# PCB_ICBExt-R1_0-J23.net
KiCad netlist of a schematic drawn in EAGLE
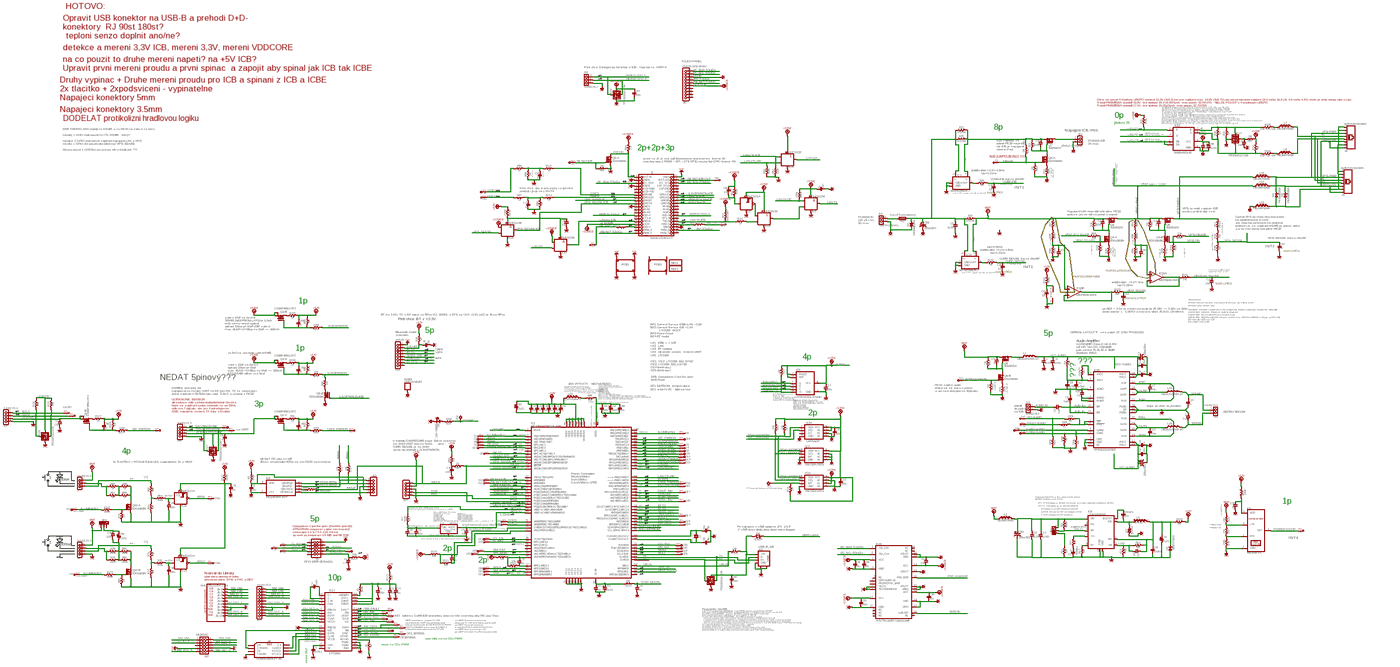
[diagram p0: schematic, sheet 1, overview]
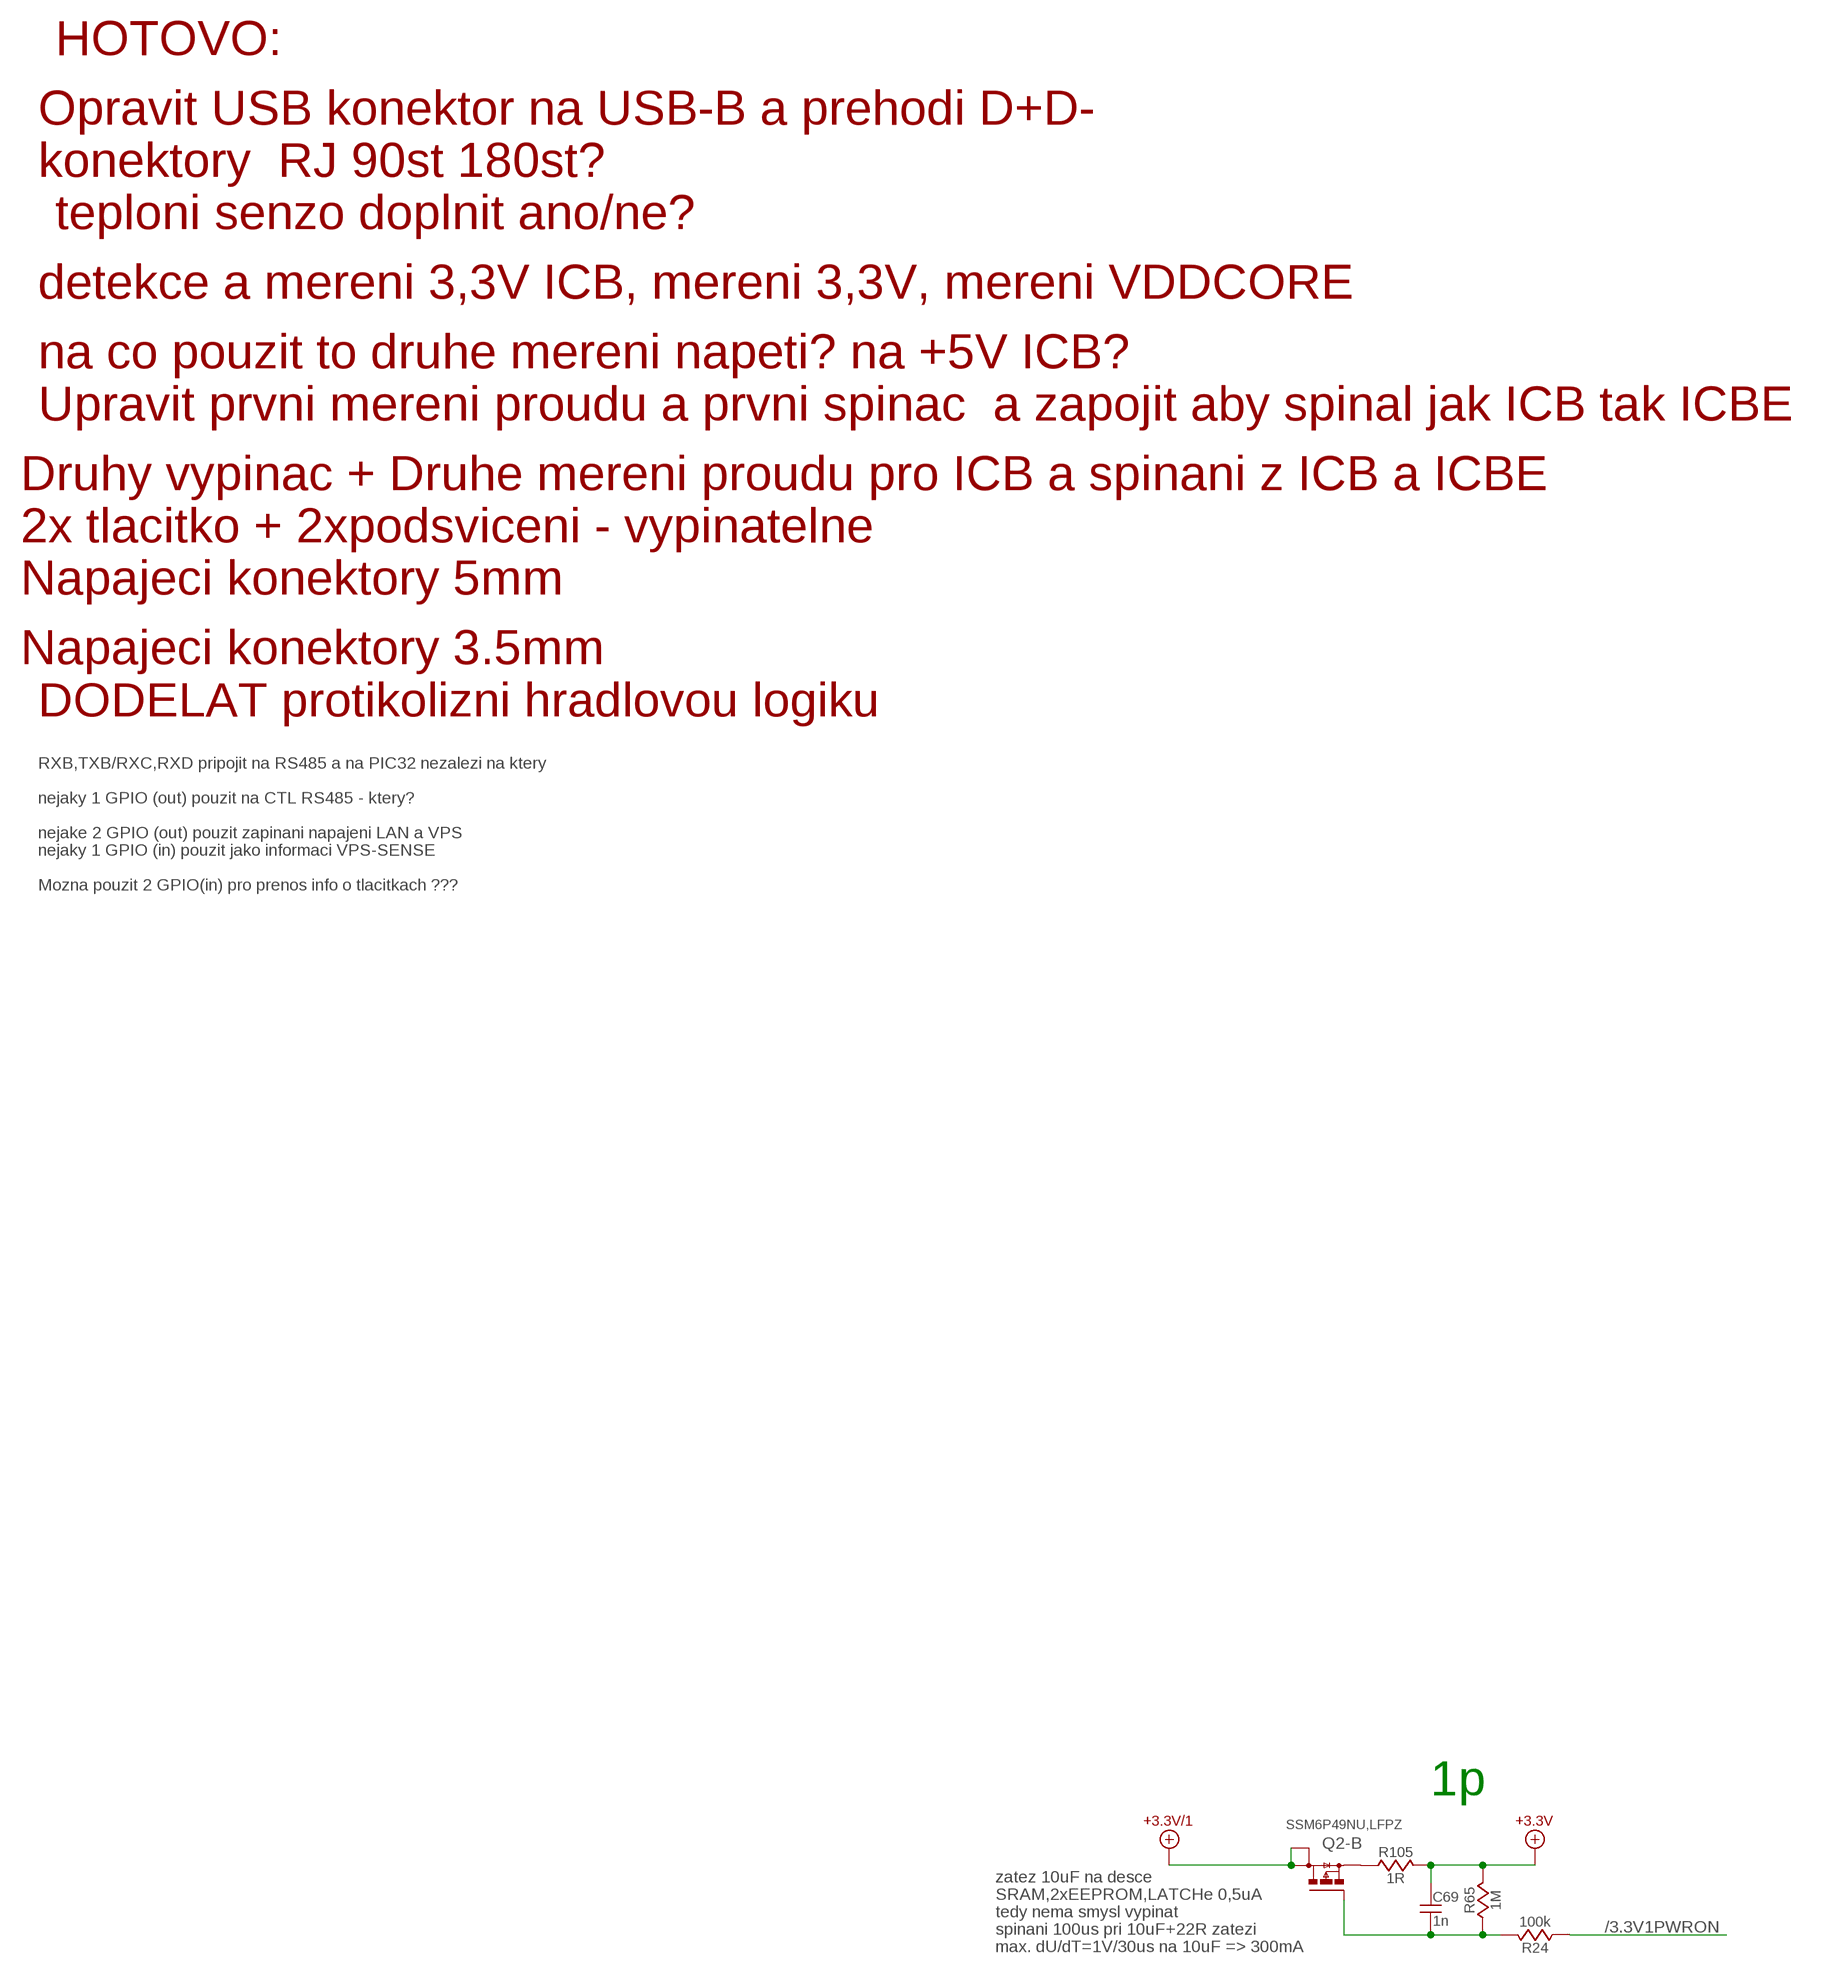
[diagram p1: schematic, sheet 1, part 1 of 6]
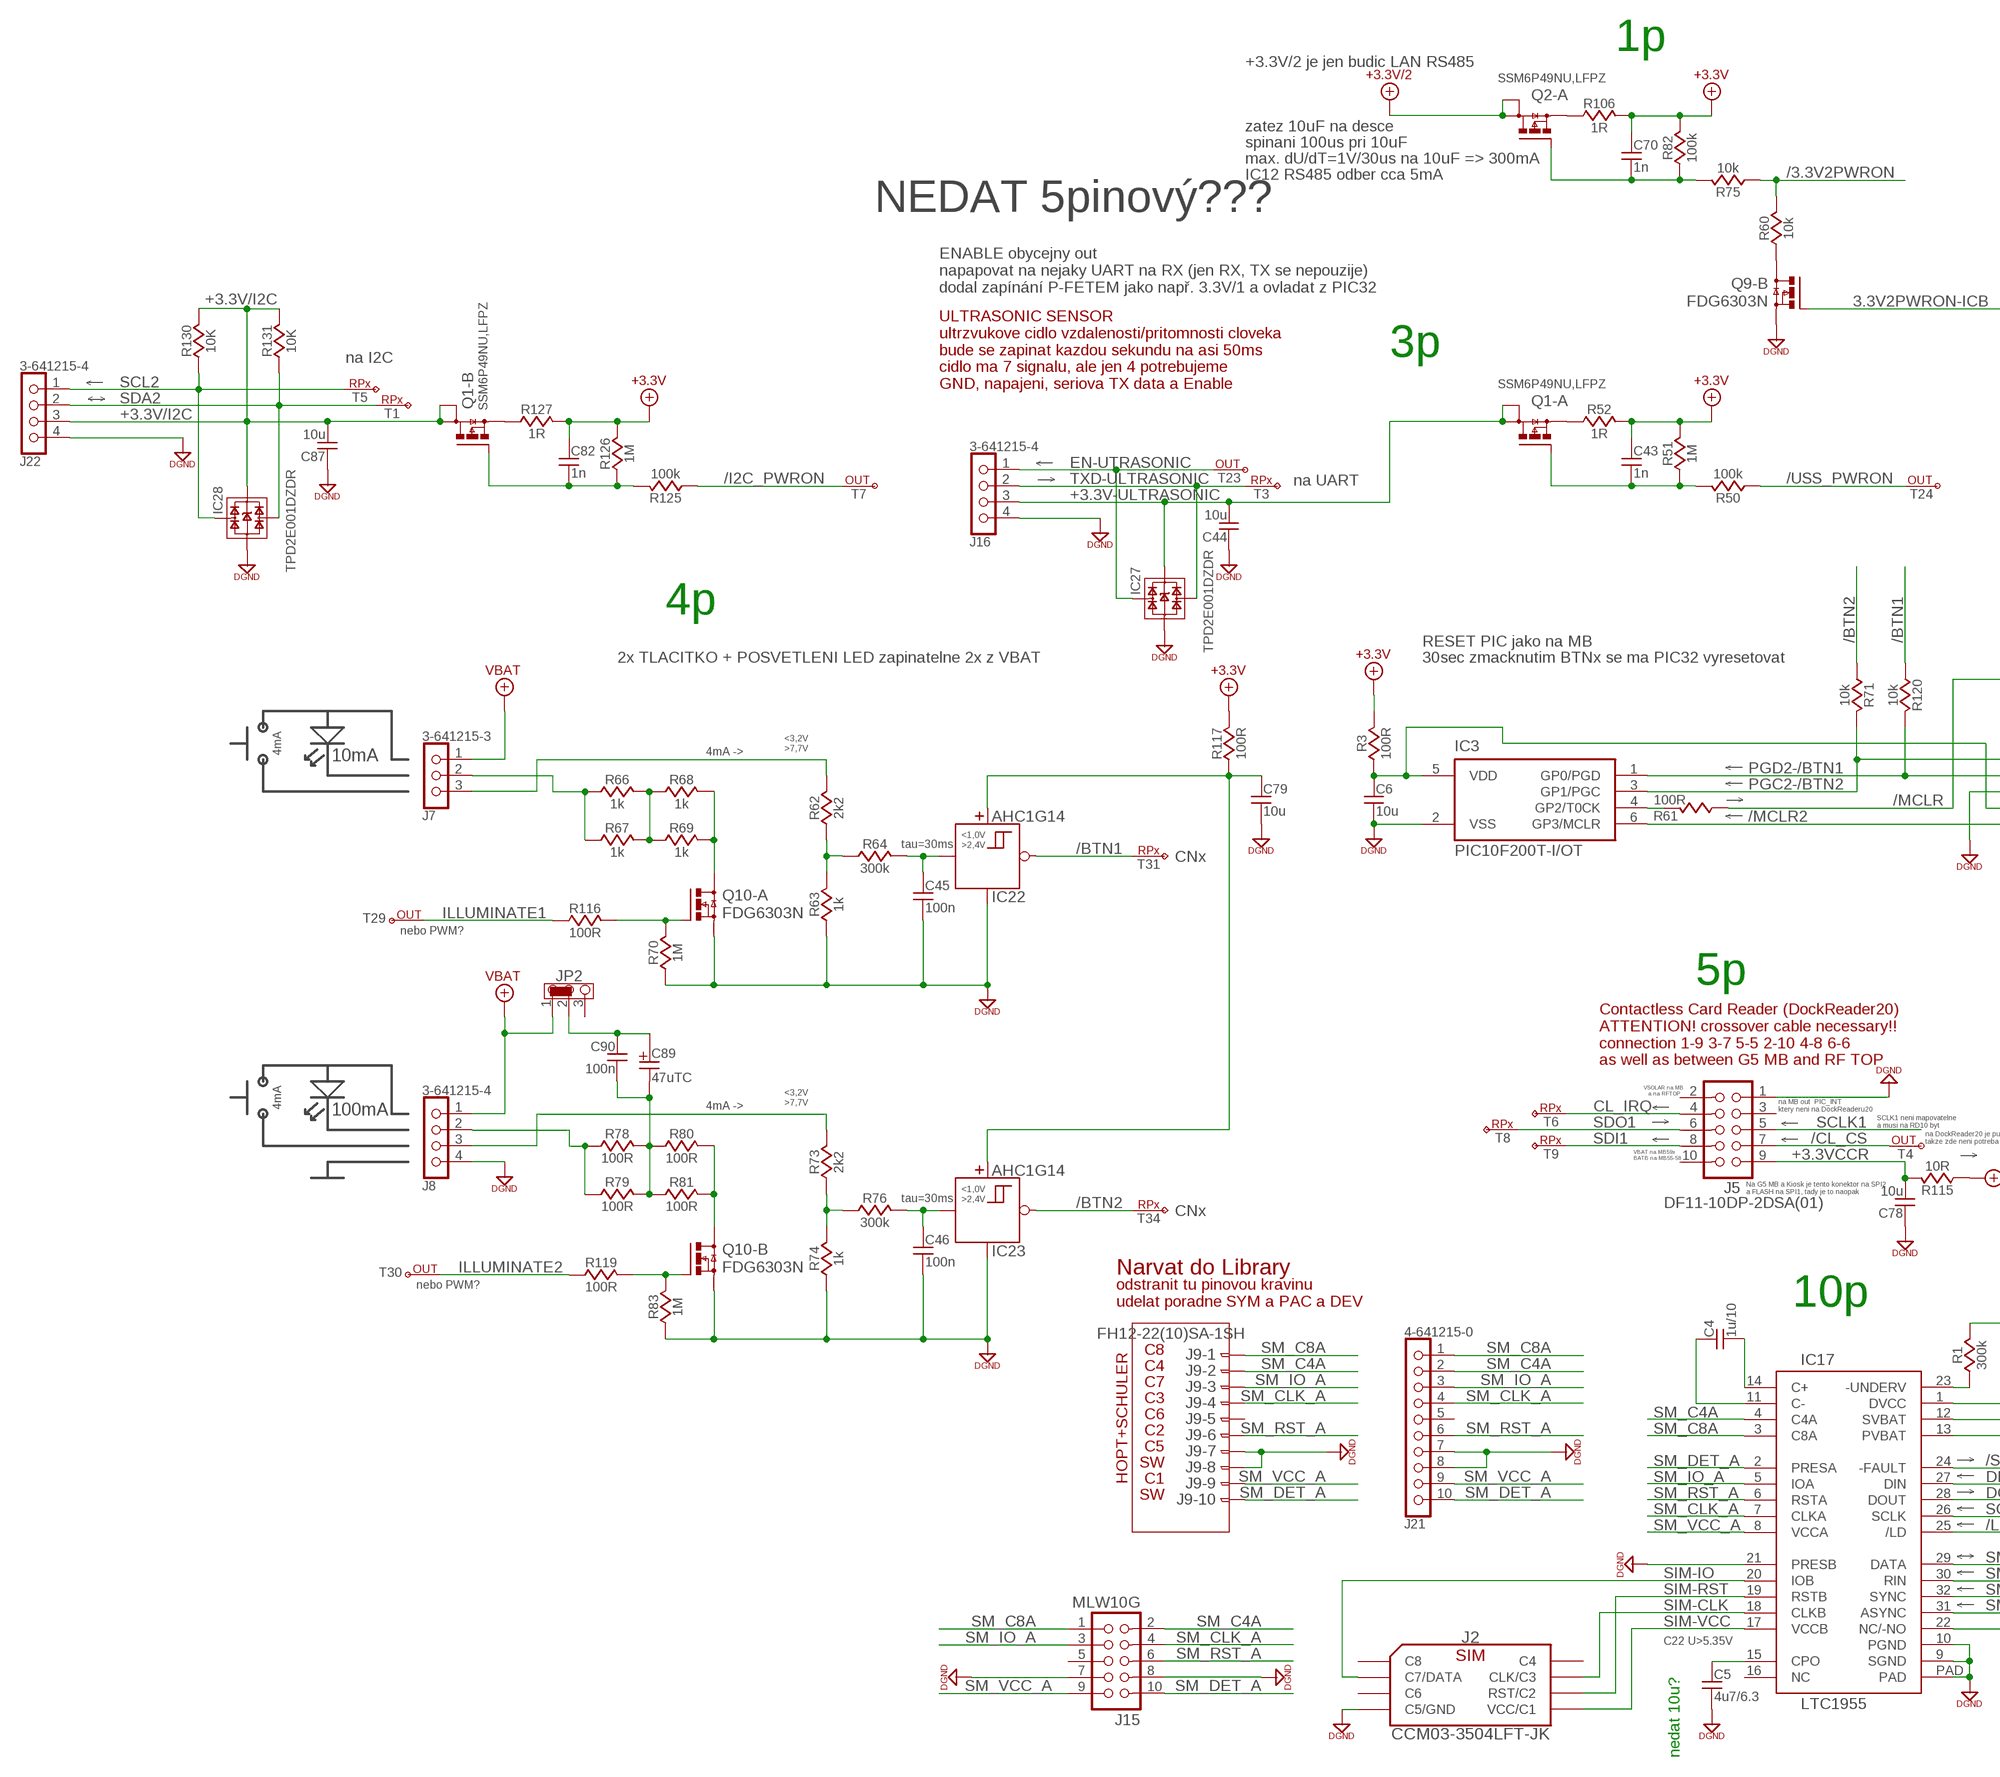
[diagram p2: schematic, sheet 1, part 2 of 6]
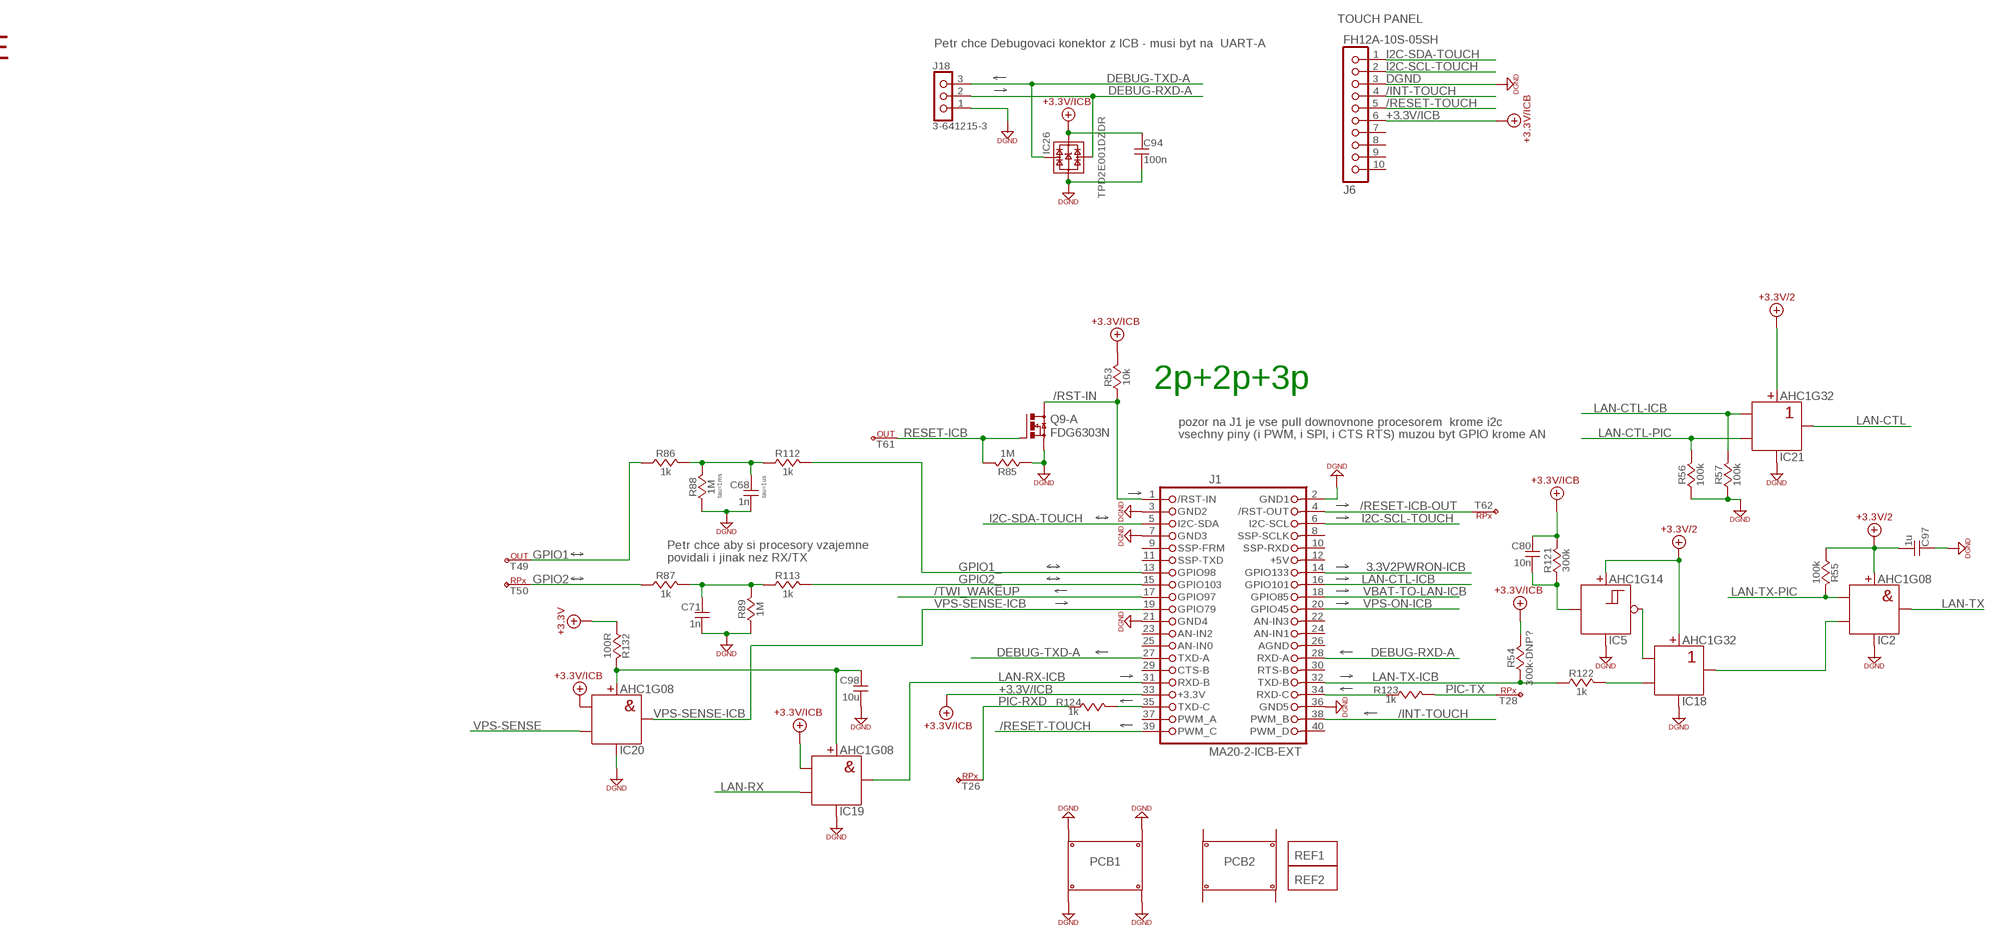
[diagram p3: schematic, sheet 1, part 3 of 6]
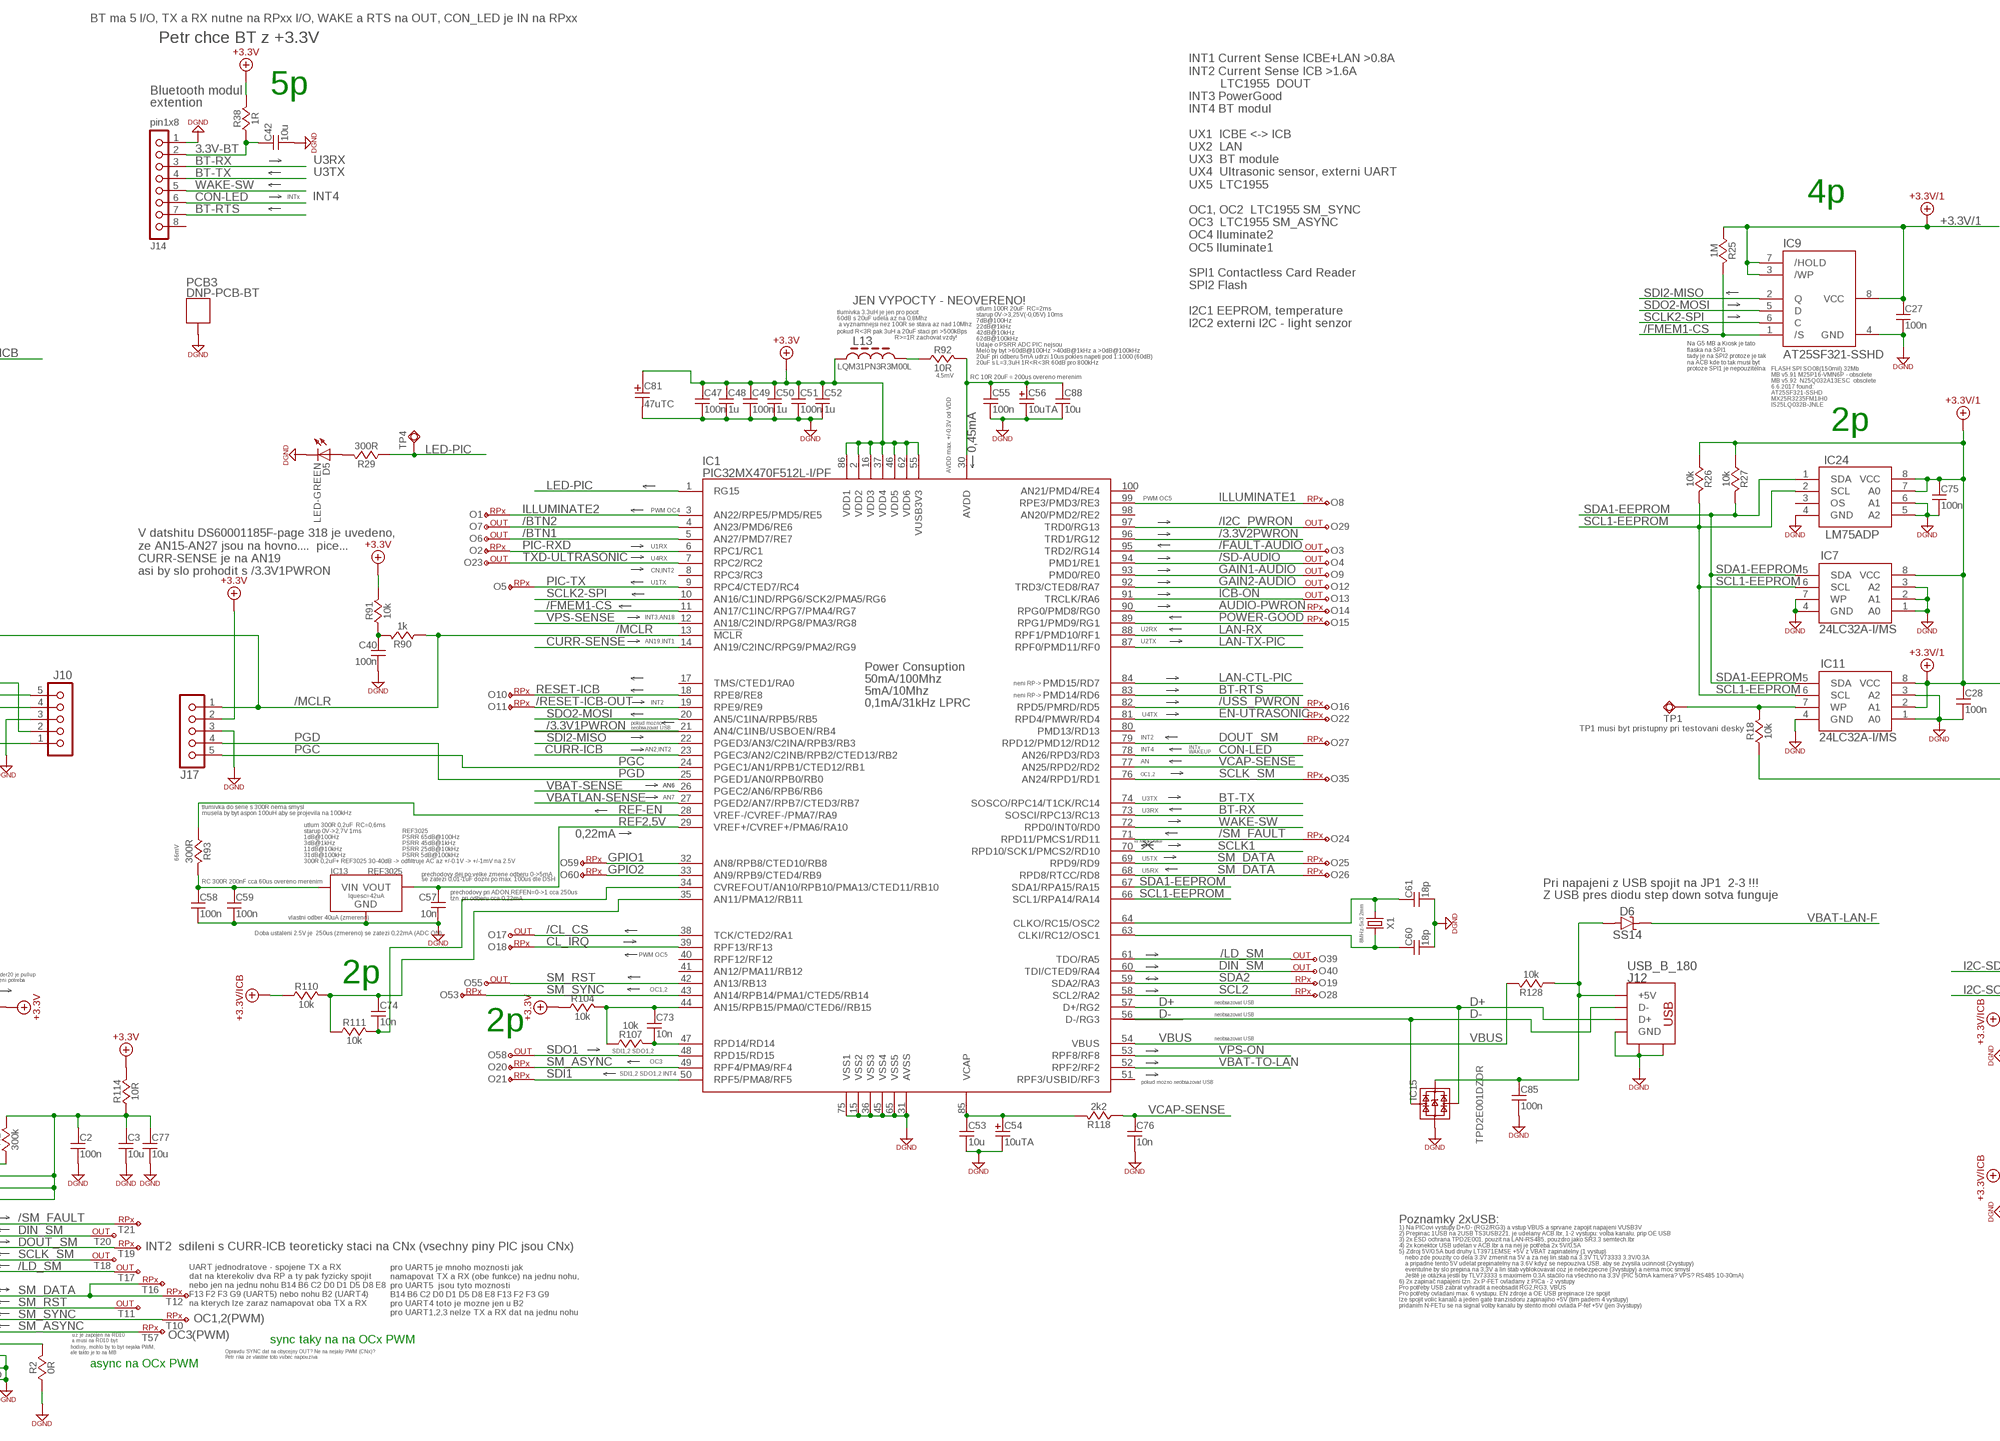
[diagram p4: schematic, sheet 1, part 4 of 6]
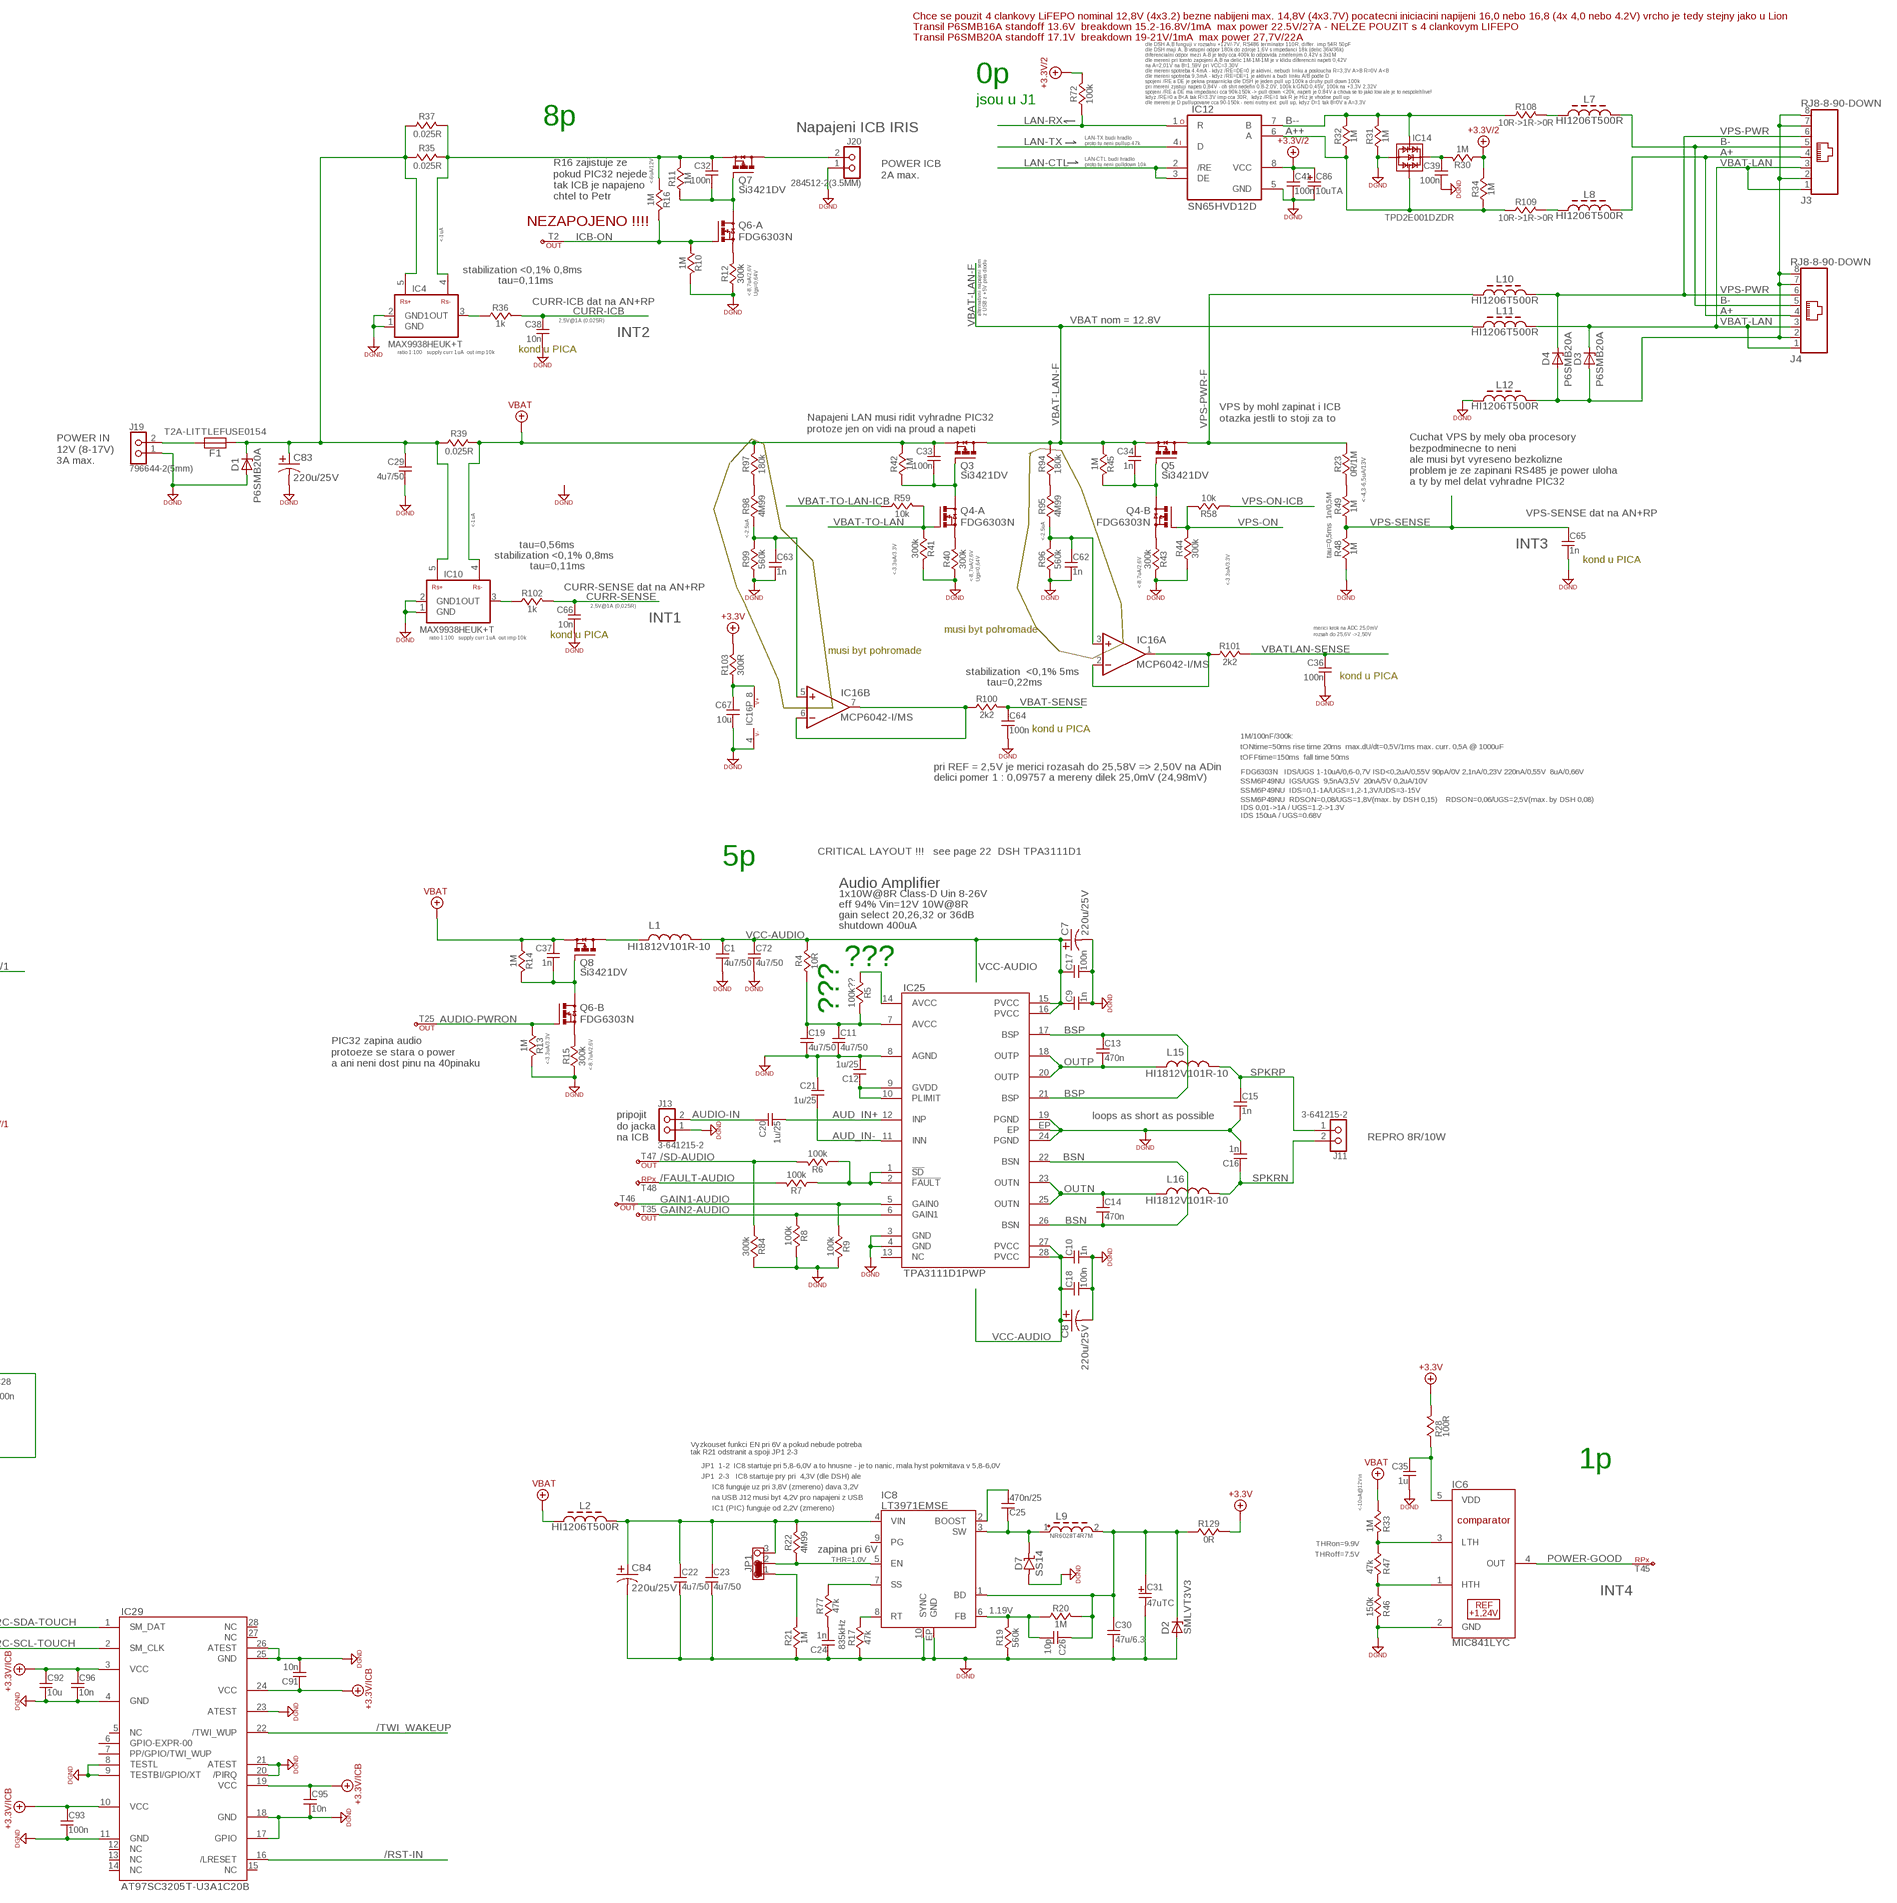
[diagram p5: schematic, sheet 1, part 5 of 6]

(export (version "E")
  (design (tool "Eeschema 10.0.6"))
  (components
    (comp (ref "C1")
      (value "4u7/50")
      (footprint "eagle-import:1206")
      (libsource (lib "eagle-import") (part "C-1206"))
    )
    (comp (ref "C2")
      (value "100n")
      (footprint "eagle-import:0603")
      (libsource (lib "eagle-import") (part "C-0603"))
    )
    (comp (ref "C3")
      (value "10u")
      (footprint "eagle-import:0603")
      (libsource (lib "eagle-import") (part "C-0603"))
    )
    (comp (ref "C4")
      (value "1u/10")
      (footprint "eagle-import:0603")
      (libsource (lib "eagle-import") (part "C-0603"))
    )
    (comp (ref "C5")
      (value "4u7/6.3")
      (footprint "eagle-import:0603")
      (libsource (lib "eagle-import") (part "C-0603"))
    )
    (comp (ref "C6")
      (value "10u")
      (footprint "eagle-import:0603")
      (libsource (lib "eagle-import") (part "C-0603"))
    )
    (comp (ref "C7")
      (value "220u/25V")
      (footprint "eagle-import:CAP_8MM_DIA_SMT")
      (libsource (lib "eagle-import") (part "CAP-ELEC-SMD-8MM"))
    )
    (comp (ref "C8")
      (value "220u/25V")
      (footprint "eagle-import:CAP_8MM_DIA_SMT")
      (libsource (lib "eagle-import") (part "CAP-ELEC-SMD-8MM"))
    )
    (comp (ref "C9")
      (value "1n")
      (footprint "eagle-import:0603")
      (libsource (lib "eagle-import") (part "C-0603"))
    )
    (comp (ref "C10")
      (value "1n")
      (footprint "eagle-import:0603")
      (libsource (lib "eagle-import") (part "C-0603"))
    )
    (comp (ref "C11")
      (value "4u7/50")
      (footprint "eagle-import:1206")
      (libsource (lib "eagle-import") (part "C-1206"))
    )
    (comp (ref "C12")
      (value "1u/25")
      (footprint "eagle-import:0603")
      (libsource (lib "eagle-import") (part "C-0603"))
    )
    (comp (ref "C13")
      (value "470n")
      (footprint "eagle-import:0603")
      (libsource (lib "eagle-import") (part "C-0603"))
    )
    (comp (ref "C14")
      (value "470n")
      (footprint "eagle-import:0603")
      (libsource (lib "eagle-import") (part "C-0603"))
    )
    (comp (ref "C15")
      (value "1n")
      (footprint "eagle-import:0603")
      (libsource (lib "eagle-import") (part "C-0603"))
    )
    (comp (ref "C16")
      (value "1n")
      (footprint "eagle-import:0603")
      (libsource (lib "eagle-import") (part "C-0603"))
    )
    (comp (ref "C17")
      (value "100n")
      (footprint "eagle-import:0603")
      (libsource (lib "eagle-import") (part "C-0603"))
    )
    (comp (ref "C18")
      (value "100n")
      (footprint "eagle-import:0603")
      (libsource (lib "eagle-import") (part "C-0603"))
    )
    (comp (ref "C19")
      (value "4u7/50")
      (footprint "eagle-import:1206")
      (libsource (lib "eagle-import") (part "C-1206"))
    )
    (comp (ref "C20")
      (value "1u/25")
      (footprint "eagle-import:0603")
      (libsource (lib "eagle-import") (part "C-0603"))
    )
    (comp (ref "C21")
      (value "1u/25")
      (footprint "eagle-import:0603")
      (libsource (lib "eagle-import") (part "C-0603"))
    )
    (comp (ref "C22")
      (value "4u7/50")
      (footprint "eagle-import:1206")
      (libsource (lib "eagle-import") (part "C-1206"))
    )
    (comp (ref "C23")
      (value "4u7/50")
      (footprint "eagle-import:1206")
      (libsource (lib "eagle-import") (part "C-1206"))
    )
    (comp (ref "C24")
      (value "1n")
      (footprint "eagle-import:0603")
      (libsource (lib "eagle-import") (part "C-0603"))
    )
    (comp (ref "C25")
      (value "470n/25")
      (footprint "eagle-import:0603")
      (libsource (lib "eagle-import") (part "C-0603"))
    )
    (comp (ref "C26")
      (value "10p")
      (footprint "eagle-import:0603")
      (libsource (lib "eagle-import") (part "C-0603"))
    )
    (comp (ref "C27")
      (value "100n")
      (footprint "eagle-import:0603")
      (libsource (lib "eagle-import") (part "C-0603"))
    )
    (comp (ref "C28")
      (value "100n")
      (footprint "eagle-import:0603")
      (libsource (lib "eagle-import") (part "C-0603"))
    )
    (comp (ref "C29")
      (value "4u7/50")
      (footprint "eagle-import:1206")
      (libsource (lib "eagle-import") (part "C-1206"))
    )
    (comp (ref "C30")
      (value "47u/6.3")
      (footprint "eagle-import:1206")
      (libsource (lib "eagle-import") (part "C-1206"))
    )
    (comp (ref "C31")
      (value "47uTC")
      (footprint "eagle-import:CT-C")
      (libsource (lib "eagle-import") (part "CT-C"))
    )
    (comp (ref "C32")
      (value "100n")
      (footprint "eagle-import:0603")
      (libsource (lib "eagle-import") (part "C-0603"))
    )
    (comp (ref "C33")
      (value "100n")
      (footprint "eagle-import:0603")
      (libsource (lib "eagle-import") (part "C-0603"))
    )
    (comp (ref "C34")
      (value "1n")
      (footprint "eagle-import:0603")
      (libsource (lib "eagle-import") (part "C-0603"))
    )
    (comp (ref "C35")
      (value "1u")
      (footprint "eagle-import:0603")
      (libsource (lib "eagle-import") (part "C-0603"))
    )
    (comp (ref "C36")
      (value "100n")
      (footprint "eagle-import:0603")
      (libsource (lib "eagle-import") (part "C-0603"))
    )
    (comp (ref "C37")
      (value "1n")
      (footprint "eagle-import:0603")
      (libsource (lib "eagle-import") (part "C-0603"))
    )
    (comp (ref "C38")
      (value "10n")
      (footprint "eagle-import:0603")
      (libsource (lib "eagle-import") (part "C-0603"))
    )
    (comp (ref "C39")
      (value "100n")
      (footprint "eagle-import:0603")
      (libsource (lib "eagle-import") (part "C-0603"))
    )
    (comp (ref "C40")
      (value "100n")
      (footprint "eagle-import:0603")
      (libsource (lib "eagle-import") (part "C-0603"))
    )
    (comp (ref "C41")
      (value "100n")
      (footprint "eagle-import:0603")
      (libsource (lib "eagle-import") (part "C-0603"))
    )
    (comp (ref "C42")
      (value "10u")
      (footprint "eagle-import:0603")
      (libsource (lib "eagle-import") (part "C-0603"))
    )
    (comp (ref "C43")
      (value "1n")
      (footprint "eagle-import:0603")
      (libsource (lib "eagle-import") (part "C-0603"))
    )
    (comp (ref "C44")
      (value "10u")
      (footprint "eagle-import:0603")
      (libsource (lib "eagle-import") (part "C-0603"))
    )
    (comp (ref "C45")
      (value "100n")
      (footprint "eagle-import:0603")
      (libsource (lib "eagle-import") (part "C-0603"))
    )
    (comp (ref "C46")
      (value "100n")
      (footprint "eagle-import:0603")
      (libsource (lib "eagle-import") (part "C-0603"))
    )
    (comp (ref "C47")
      (value "100n")
      (footprint "eagle-import:0603")
      (libsource (lib "eagle-import") (part "C-0603"))
    )
    (comp (ref "C48")
      (value "1u")
      (footprint "eagle-import:0603")
      (libsource (lib "eagle-import") (part "C-0603"))
    )
    (comp (ref "C49")
      (value "100n")
      (footprint "eagle-import:0603")
      (libsource (lib "eagle-import") (part "C-0603"))
    )
    (comp (ref "C50")
      (value "1u")
      (footprint "eagle-import:0603")
      (libsource (lib "eagle-import") (part "C-0603"))
    )
    (comp (ref "C51")
      (value "100n")
      (footprint "eagle-import:0603")
      (libsource (lib "eagle-import") (part "C-0603"))
    )
    (comp (ref "C52")
      (value "1u")
      (footprint "eagle-import:0603")
      (libsource (lib "eagle-import") (part "C-0603"))
    )
    (comp (ref "C53")
      (value "10u")
      (footprint "eagle-import:0603")
      (libsource (lib "eagle-import") (part "C-0603"))
    )
    (comp (ref "C54")
      (value "10uTA")
      (footprint "eagle-import:1206-POL-C")
      (libsource (lib "eagle-import") (part "CT-1206"))
    )
    (comp (ref "C55")
      (value "100n")
      (footprint "eagle-import:0603")
      (libsource (lib "eagle-import") (part "C-0603"))
    )
    (comp (ref "C56")
      (value "10uTA")
      (footprint "eagle-import:1206-POL-C")
      (libsource (lib "eagle-import") (part "CT-1206"))
    )
    (comp (ref "C57")
      (value "10n")
      (footprint "eagle-import:0603")
      (libsource (lib "eagle-import") (part "C-0603"))
    )
    (comp (ref "C58")
      (value "100n")
      (footprint "eagle-import:0603")
      (libsource (lib "eagle-import") (part "C-0603"))
    )
    (comp (ref "C59")
      (value "100n")
      (footprint "eagle-import:0603")
      (libsource (lib "eagle-import") (part "C-0603"))
    )
    (comp (ref "C60")
      (value "18p")
      (footprint "eagle-import:0603")
      (libsource (lib "eagle-import") (part "C-0603"))
    )
    (comp (ref "C61")
      (value "18p")
      (footprint "eagle-import:0603")
      (libsource (lib "eagle-import") (part "C-0603"))
    )
    (comp (ref "C62")
      (value "1n")
      (footprint "eagle-import:0603")
      (libsource (lib "eagle-import") (part "C-0603"))
    )
    (comp (ref "C63")
      (value "1n")
      (footprint "eagle-import:0603")
      (libsource (lib "eagle-import") (part "C-0603"))
    )
    (comp (ref "C64")
      (value "100n")
      (footprint "eagle-import:0603")
      (libsource (lib "eagle-import") (part "C-0603"))
    )
    (comp (ref "C65")
      (value "1n")
      (footprint "eagle-import:0603")
      (libsource (lib "eagle-import") (part "C-0603"))
    )
    (comp (ref "C66")
      (value "10n")
      (footprint "eagle-import:0603")
      (libsource (lib "eagle-import") (part "C-0603"))
    )
    (comp (ref "C67")
      (value "10u")
      (footprint "eagle-import:0603")
      (libsource (lib "eagle-import") (part "C-0603"))
    )
    (comp (ref "C68")
      (value "1n")
      (footprint "eagle-import:0603")
      (libsource (lib "eagle-import") (part "C-0603"))
    )
    (comp (ref "C69")
      (value "1n")
      (footprint "eagle-import:0603")
      (libsource (lib "eagle-import") (part "C-0603"))
    )
    (comp (ref "C70")
      (value "1n")
      (footprint "eagle-import:0603")
      (libsource (lib "eagle-import") (part "C-0603"))
    )
    (comp (ref "C71")
      (value "1n")
      (footprint "eagle-import:0603")
      (libsource (lib "eagle-import") (part "C-0603"))
    )
    (comp (ref "C72")
      (value "4u7/50")
      (footprint "eagle-import:1206")
      (libsource (lib "eagle-import") (part "C-1206"))
    )
    (comp (ref "C73")
      (value "10n")
      (footprint "eagle-import:0603")
      (libsource (lib "eagle-import") (part "C-0603"))
    )
    (comp (ref "C74")
      (value "10n")
      (footprint "eagle-import:0603")
      (libsource (lib "eagle-import") (part "C-0603"))
    )
    (comp (ref "C75")
      (value "100n")
      (footprint "eagle-import:0603")
      (libsource (lib "eagle-import") (part "C-0603"))
    )
    (comp (ref "C76")
      (value "10n")
      (footprint "eagle-import:0603")
      (libsource (lib "eagle-import") (part "C-0603"))
    )
    (comp (ref "C77")
      (value "10u")
      (footprint "eagle-import:0603")
      (libsource (lib "eagle-import") (part "C-0603"))
    )
    (comp (ref "C78")
      (value "10u")
      (footprint "eagle-import:0603")
      (libsource (lib "eagle-import") (part "C-0603"))
    )
    (comp (ref "C79")
      (value "10u")
      (footprint "eagle-import:0603")
      (libsource (lib "eagle-import") (part "C-0603"))
    )
    (comp (ref "C80")
      (value "10n")
      (footprint "eagle-import:0603")
      (libsource (lib "eagle-import") (part "C-0603"))
    )
    (comp (ref "C81")
      (value "47uTC")
      (footprint "eagle-import:CT-C")
      (libsource (lib "eagle-import") (part "CT-C"))
    )
    (comp (ref "C82")
      (value "1n")
      (footprint "eagle-import:0603")
      (libsource (lib "eagle-import") (part "C-0603"))
    )
    (comp (ref "C83")
      (value "220u/25V")
      (footprint "eagle-import:CAP_8MM_DIA_SMT")
      (libsource (lib "eagle-import") (part "CAP-ELEC-SMD-8MM"))
    )
    (comp (ref "C84")
      (value "220u/25V")
      (footprint "eagle-import:CAP_8MM_DIA_SMT")
      (libsource (lib "eagle-import") (part "CAP-ELEC-SMD-8MM"))
    )
    (comp (ref "C85")
      (value "100n")
      (footprint "eagle-import:0603")
      (libsource (lib "eagle-import") (part "C-0603"))
    )
    (comp (ref "C86")
      (value "10uTA")
      (footprint "eagle-import:1206-POL-C")
      (libsource (lib "eagle-import") (part "CT-1206"))
    )
    (comp (ref "C87")
      (value "10u")
      (footprint "eagle-import:0603")
      (libsource (lib "eagle-import") (part "C-0603"))
    )
    (comp (ref "C88")
      (value "10u")
      (footprint "eagle-import:0603")
      (libsource (lib "eagle-import") (part "C-0603"))
    )
    (comp (ref "C89")
      (value "47uTC")
      (footprint "eagle-import:CT-C")
      (libsource (lib "eagle-import") (part "CT-C"))
    )
    (comp (ref "C90")
      (value "100n")
      (footprint "eagle-import:0603")
      (libsource (lib "eagle-import") (part "C-0603"))
    )
    (comp (ref "C91")
      (value "10n")
      (footprint "eagle-import:0603")
      (libsource (lib "eagle-import") (part "C-0603"))
    )
    (comp (ref "C92")
      (value "10u")
      (footprint "eagle-import:0603")
      (libsource (lib "eagle-import") (part "C-0603"))
    )
    (comp (ref "C93")
      (value "100n")
      (footprint "eagle-import:0603")
      (libsource (lib "eagle-import") (part "C-0603"))
    )
    (comp (ref "C94")
      (value "100n")
      (footprint "eagle-import:0603")
      (libsource (lib "eagle-import") (part "C-0603"))
    )
    (comp (ref "C95")
      (value "10n")
      (footprint "eagle-import:0603")
      (libsource (lib "eagle-import") (part "C-0603"))
    )
    (comp (ref "C96")
      (value "10n")
      (footprint "eagle-import:0603")
      (libsource (lib "eagle-import") (part "C-0603"))
    )
    (comp (ref "C97")
      (value "1u")
      (footprint "eagle-import:0603")
      (libsource (lib "eagle-import") (part "C-0603"))
    )
    (comp (ref "C98")
      (value "10u")
      (footprint "eagle-import:0603")
      (libsource (lib "eagle-import") (part "C-0603"))
    )
    (comp (ref "D1")
      (value "P6SMB20A")
      (footprint "eagle-import:SMB")
      (libsource (lib "eagle-import") (part "P6SMB"))
    )
    (comp (ref "D2")
      (value "SMLVT3V3")
      (footprint "eagle-import:SMA")
      (libsource (lib "eagle-import") (part "SMLVT3V3"))
    )
    (comp (ref "D3")
      (value "P6SMB20A")
      (footprint "eagle-import:SMB")
      (libsource (lib "eagle-import") (part "P6SMB"))
    )
    (comp (ref "D4")
      (value "P6SMB20A")
      (footprint "eagle-import:SMB")
      (libsource (lib "eagle-import") (part "P6SMB"))
    )
    (comp (ref "D5")
      (value "LED-GREEN")
      (footprint "eagle-import:0805-POL-D")
      (libsource (lib "eagle-import") (part "LED-0805"))
    )
    (comp (ref "D6")
      (value "SS14")
      (footprint "eagle-import:SMA")
      (libsource (lib "eagle-import") (part "DS-SMA"))
    )
    (comp (ref "D7")
      (value "SS14")
      (footprint "eagle-import:SMA")
      (libsource (lib "eagle-import") (part "DS-SMA"))
    )
    (comp (ref "F1")
      (value "T2A-LITTLEFUSE0154")
      (footprint "eagle-import:LITTLEFUSE0154")
      (libsource (lib "eagle-import") (part "POJISTKA-LITTLEFUSE0154"))
    )
    (comp (ref "IC1")
      (value "PIC32MX470F512L-I/PF")
      (footprint "eagle-import:TQFP100_14X14_0,5MM")
      (libsource (lib "eagle-import") (part "PIC32MX470F512L-I/PF"))
    )
    (comp (ref "IC2")
      (value "AHC1G08")
      (footprint "eagle-import:SC70-5,SOT353,TSSOP5")
      (libsource (lib "eagle-import") (part "AHC1G08"))
    )
    (comp (ref "IC3")
      (value "PIC10F200T-I/OT")
      (footprint "eagle-import:SOT23-6")
      (libsource (lib "eagle-import") (part "PIC10F200T-I/OT"))
    )
    (comp (ref "IC4")
      (value "MAX9938HEUK+T")
      (footprint "eagle-import:SOT23-5")
      (libsource (lib "eagle-import") (part "TSM9938HEUK+T"))
    )
    (comp (ref "IC5")
      (value "AHC1G14")
      (footprint "eagle-import:SC70-5,SOT353,TSSOP5")
      (libsource (lib "eagle-import") (part "AHC1G14"))
    )
    (comp (ref "IC6")
      (value "MIC841LYC")
      (footprint "eagle-import:SC-70-5")
      (libsource (lib "eagle-import") (part "MIC841LYC"))
    )
    (comp (ref "IC7")
      (value "24LC32A-I/MS")
      (footprint "eagle-import:MSOP-08")
      (libsource (lib "eagle-import") (part "24-I/MS"))
    )
    (comp (ref "IC8")
      (value "LT3971EMSE")
      (footprint "eagle-import:MSOP10EXP")
      (libsource (lib "eagle-import") (part "LT3971EMSE"))
    )
    (comp (ref "IC9")
      (value "AT25SF321-SSHD")
      (footprint "eagle-import:SO-08")
      (libsource (lib "eagle-import") (part "M25P16-VMN6P"))
    )
    (comp (ref "IC10")
      (value "MAX9938HEUK+T")
      (footprint "eagle-import:SOT23-5")
      (libsource (lib "eagle-import") (part "TSM9938HEUK+T"))
    )
    (comp (ref "IC11")
      (value "24LC32A-I/MS")
      (footprint "eagle-import:MSOP-08")
      (libsource (lib "eagle-import") (part "24-I/MS"))
    )
    (comp (ref "IC12")
      (value "SN65HVD12D")
      (footprint "eagle-import:SO08")
      (libsource (lib "eagle-import") (part "SN65HVD3082ED"))
    )
    (comp (ref "IC13")
      (value "REF3025")
      (footprint "eagle-import:SOT23")
      (libsource (lib "eagle-import") (part "REF3025"))
    )
    (comp (ref "IC14")
      (value "TPD2E001DZDR")
      (footprint "eagle-import:SOT-143")
      (libsource (lib "eagle-import") (part "SR05.TCT"))
    )
    (comp (ref "IC15")
      (value "TPD2E001DZDR")
      (footprint "eagle-import:SOT-143")
      (libsource (lib "eagle-import") (part "SR05.TCT"))
    )
    (comp (ref "IC16")
      (value "MCP6042-I/MS")
      (footprint "eagle-import:MSOP-08")
      (libsource (lib "eagle-import") (part "MCP6042-I/MS"))
    )
    (comp (ref "IC17")
      (value "LTC1955")
      (footprint "eagle-import:QFN32")
      (libsource (lib "eagle-import") (part "LTC1955"))
    )
    (comp (ref "IC18")
      (value "AHC1G32")
      (footprint "eagle-import:SC70-5,SOT353,TSSOP5")
      (libsource (lib "eagle-import") (part "AHC1G32"))
    )
    (comp (ref "IC19")
      (value "AHC1G08")
      (footprint "eagle-import:SC70-5,SOT353,TSSOP5")
      (libsource (lib "eagle-import") (part "AHC1G08"))
    )
    (comp (ref "IC20")
      (value "AHC1G08")
      (footprint "eagle-import:SC70-5,SOT353,TSSOP5")
      (libsource (lib "eagle-import") (part "AHC1G08"))
    )
    (comp (ref "IC21")
      (value "AHC1G32")
      (footprint "eagle-import:SC70-5,SOT353,TSSOP5")
      (libsource (lib "eagle-import") (part "AHC1G32"))
    )
    (comp (ref "IC22")
      (value "AHC1G14")
      (footprint "eagle-import:SC70-5,SOT353,TSSOP5")
      (libsource (lib "eagle-import") (part "AHC1G14"))
    )
    (comp (ref "IC23")
      (value "AHC1G14")
      (footprint "eagle-import:SC70-5,SOT353,TSSOP5")
      (libsource (lib "eagle-import") (part "AHC1G14"))
    )
    (comp (ref "IC24")
      (value "LM75ADP")
      (footprint "eagle-import:TSSOP08-3")
      (libsource (lib "eagle-import") (part "LM75ADP"))
    )
    (comp (ref "IC25")
      (value "TPA3111D1PWP")
      (footprint "eagle-import:TSSOP28_EP")
      (fields (field (name "MANUFACTURER") "TI"))
      (libsource (lib "eagle-import") (part "IC_TI_TPA3111D1PWP"))
    )
    (comp (ref "IC26")
      (value "TPD2E001DZDR")
      (footprint "eagle-import:SOT-143")
      (libsource (lib "eagle-import") (part "SR05.TCT"))
    )
    (comp (ref "IC27")
      (value "TPD2E001DZDR")
      (footprint "eagle-import:SOT-143")
      (libsource (lib "eagle-import") (part "SR05.TCT"))
    )
    (comp (ref "IC28")
      (value "TPD2E001DZDR")
      (footprint "eagle-import:SOT-143")
      (libsource (lib "eagle-import") (part "SR05.TCT"))
    )
    (comp (ref "IC29")
      (value "AT97SC3205T-U3A1C20B")
      (footprint "eagle-import:TSSOP28")
      (fields (field (name "MANUFACTURER") "Microchip"))
      (libsource (lib "eagle-import") (part "AT97SC3205T-U3A1C20B"))
    )
    (comp (ref "J1")
      (value "MA20-2-ICB-EXT")
      (footprint "eagle-import:MA20-2")
      (libsource (lib "eagle-import") (part "MA20-2-ICB-EXT"))
    )
    (comp (ref "J2")
      (value "CCM03-3504LFT-JK")
      (footprint "eagle-import:CCM03-3504LFT-JK")
      (libsource (lib "eagle-import") (part "CCM03-3504LFT-JK"))
    )
    (comp (ref "J3")
      (value "RJ8-8-90-DOWN")
      (footprint "eagle-import:RJ8-8-90-DOWN")
      (libsource (lib "eagle-import") (part "RJ8-8-90-DOWN"))
    )
    (comp (ref "J4")
      (value "RJ8-8-90-DOWN")
      (footprint "eagle-import:RJ8-8-90-DOWN")
      (libsource (lib "eagle-import") (part "RJ8-8-90-DOWN"))
    )
    (comp (ref "J5")
      (value "DF11-10DP-2DSA(01)")
      (footprint "eagle-import:DF11-10DP-2DSA")
      (libsource (lib "eagle-import") (part "DF11-10DP-2DSA(01)"))
    )
    (comp (ref "J6")
      (value "FH12A-10S-05SH")
      (footprint "eagle-import:FH12A-10S-05SH")
      (libsource (lib "eagle-import") (part "FH12A-10S-05SH"))
    )
    (comp (ref "J7")
      (value "3-641215-3")
      (footprint "eagle-import:3-641215-3")
      (libsource (lib "eagle-import") (part "3-641215-3"))
    )
    (comp (ref "J8")
      (value "3-641215-4")
      (footprint "eagle-import:3-641215-4")
      (libsource (lib "eagle-import") (part "3-641215-4"))
    )
    (comp (ref "J9")
      (value "FH12-22(10)SA-1SH")
      (footprint "eagle-import:CON-FPC-1.0MM-10POS")
      (libsource (lib "eagle-import") (part "FH12-10S-0.5S1.00MM"))
    )
    (comp (ref "J10")
      (value "DNP-open-hole")
      (footprint "eagle-import:MA05-1")
      (libsource (lib "eagle-import") (part "MA05-1"))
    )
    (comp (ref "J11")
      (value "3-641215-2")
      (footprint "eagle-import:3-641215-2")
      (libsource (lib "eagle-import") (part "3-641215-2"))
    )
    (comp (ref "J12")
      (value "USB_B_180")
      (footprint "eagle-import:USB_B_90")
      (libsource (lib "eagle-import") (part "USB_B_90"))
    )
    (comp (ref "J13")
      (value "3-641215-2")
      (footprint "eagle-import:3-641215-2")
      (libsource (lib "eagle-import") (part "3-641215-2"))
    )
    (comp (ref "J14")
      (value "pin1x8")
      (footprint "eagle-import:MA08-1-MALE")
      (libsource (lib "eagle-import") (part "MA08-1-M"))
    )
    (comp (ref "J15")
      (value "MLW10G")
      (footprint "eagle-import:MLW10G-5X2")
      (libsource (lib "eagle-import") (part "MLW10G"))
    )
    (comp (ref "J16")
      (value "3-641215-4")
      (footprint "eagle-import:3-641215-4")
      (libsource (lib "eagle-import") (part "3-641215-4"))
    )
    (comp (ref "J17")
      (value "DNP-open-hole")
      (footprint "eagle-import:MA05-1")
      (libsource (lib "eagle-import") (part "MA05-1"))
    )
    (comp (ref "J18")
      (value "3-641215-3")
      (footprint "eagle-import:3-641215-3")
      (libsource (lib "eagle-import") (part "3-641215-3"))
    )
    (comp (ref "J19")
      (value "796644-2(5mm)")
      (footprint "eagle-import:796644-2-5MM")
      (libsource (lib "eagle-import") (part "796644-2"))
    )
    (comp (ref "J20")
      (value "284512-2(3.5MM)")
      (footprint "eagle-import:284512-2-3,5MM")
      (libsource (lib "eagle-import") (part "284512-2"))
    )
    (comp (ref "J21")
      (value "4-641215-0")
      (footprint "eagle-import:4-641215-0")
      (libsource (lib "eagle-import") (part "4-641215-0"))
    )
    (comp (ref "J22")
      (value "3-641215-4")
      (footprint "eagle-import:3-641215-4")
      (libsource (lib "eagle-import") (part "3-641215-4"))
    )
    (comp (ref "JP1")
      (value "JP3CLOSE12")
      (footprint "eagle-import:JP3CLOSE12")
      (libsource (lib "eagle-import") (part "JP3CLOSE12"))
    )
    (comp (ref "JP2")
      (value "JP3CLOSE12")
      (footprint "eagle-import:JP3CLOSE12")
      (libsource (lib "eagle-import") (part "JP3CLOSE12"))
    )
    (comp (ref "L1")
      (value "HI1812V101R-10")
      (footprint "eagle-import:L1812")
      (fields (field (name "MANUFACTURER") "Laird") (field (name "MFR_PN") "HI1812V101R-10"))
      (libsource (lib "eagle-import") (part "L1812"))
    )
    (comp (ref "L2")
      (value "HI1206T500R")
      (footprint "eagle-import:1206")
      (libsource (lib "eagle-import") (part "L-1206"))
    )
    (comp (ref "L7")
      (value "HI1206T500R")
      (footprint "eagle-import:1206")
      (libsource (lib "eagle-import") (part "L-1206"))
    )
    (comp (ref "L8")
      (value "HI1206T500R")
      (footprint "eagle-import:1206")
      (libsource (lib "eagle-import") (part "L-1206"))
    )
    (comp (ref "L9")
      (value "NR6028T4R7M")
      (footprint "eagle-import:NR6028")
      (libsource (lib "eagle-import") (part "NR6028"))
    )
    (comp (ref "L10")
      (value "HI1206T500R")
      (footprint "eagle-import:1206")
      (libsource (lib "eagle-import") (part "L-1206"))
    )
    (comp (ref "L11")
      (value "HI1206T500R")
      (footprint "eagle-import:1206")
      (libsource (lib "eagle-import") (part "L-1206"))
    )
    (comp (ref "L12")
      (value "HI1206T500R")
      (footprint "eagle-import:1206")
      (libsource (lib "eagle-import") (part "L-1206"))
    )
    (comp (ref "L13")
      (value "LQM31PN3R3M00L")
      (footprint "eagle-import:1206")
      (libsource (lib "eagle-import") (part "L-1206"))
    )
    (comp (ref "L15")
      (value "HI1812V101R-10")
      (footprint "eagle-import:L1812")
      (fields (field (name "MANUFACTURER") "Laird") (field (name "MFR_PN") "HI1812V101R-10"))
      (libsource (lib "eagle-import") (part "L1812"))
    )
    (comp (ref "L16")
      (value "HI1812V101R-10")
      (footprint "eagle-import:L1812")
      (fields (field (name "MANUFACTURER") "Laird") (field (name "MFR_PN") "HI1812V101R-10"))
      (libsource (lib "eagle-import") (part "L1812"))
    )
    (comp (ref "O1")
      (value "PIC-RPX")
      (footprint "eagle-import:TEMP-PAD")
      (libsource (lib "eagle-import") (part "PIC-RPX"))
    )
    (comp (ref "O2")
      (value "PIC-RPX")
      (footprint "eagle-import:TEMP-PAD")
      (libsource (lib "eagle-import") (part "PIC-RPX"))
    )
    (comp (ref "O3")
      (value "PIC-OUT")
      (footprint "eagle-import:TEMP-PAD")
      (libsource (lib "eagle-import") (part "PIC-OUT"))
    )
    (comp (ref "O4")
      (value "PIC-OUT")
      (footprint "eagle-import:TEMP-PAD")
      (libsource (lib "eagle-import") (part "PIC-OUT"))
    )
    (comp (ref "O5")
      (value "PIC-RPX")
      (footprint "eagle-import:TEMP-PAD")
      (libsource (lib "eagle-import") (part "PIC-RPX"))
    )
    (comp (ref "O6")
      (value "PIC-OUT")
      (footprint "eagle-import:TEMP-PAD")
      (libsource (lib "eagle-import") (part "PIC-OUT"))
    )
    (comp (ref "O7")
      (value "PIC-OUT")
      (footprint "eagle-import:TEMP-PAD")
      (libsource (lib "eagle-import") (part "PIC-OUT"))
    )
    (comp (ref "O8")
      (value "PIC-RPX")
      (footprint "eagle-import:TEMP-PAD")
      (libsource (lib "eagle-import") (part "PIC-RPX"))
    )
    (comp (ref "O9")
      (value "PIC-OUT")
      (footprint "eagle-import:TEMP-PAD")
      (libsource (lib "eagle-import") (part "PIC-OUT"))
    )
    (comp (ref "O10")
      (value "PIC-RPX")
      (footprint "eagle-import:TEMP-PAD")
      (libsource (lib "eagle-import") (part "PIC-RPX"))
    )
    (comp (ref "O11")
      (value "PIC-RPX")
      (footprint "eagle-import:TEMP-PAD")
      (libsource (lib "eagle-import") (part "PIC-RPX"))
    )
    (comp (ref "O12")
      (value "PIC-OUT")
      (footprint "eagle-import:TEMP-PAD")
      (libsource (lib "eagle-import") (part "PIC-OUT"))
    )
    (comp (ref "O13")
      (value "PIC-OUT")
      (footprint "eagle-import:TEMP-PAD")
      (libsource (lib "eagle-import") (part "PIC-OUT"))
    )
    (comp (ref "O14")
      (value "PIC-RPX")
      (footprint "eagle-import:TEMP-PAD")
      (libsource (lib "eagle-import") (part "PIC-RPX"))
    )
    (comp (ref "O15")
      (value "PIC-RPX")
      (footprint "eagle-import:TEMP-PAD")
      (libsource (lib "eagle-import") (part "PIC-RPX"))
    )
    (comp (ref "O16")
      (value "PIC-RPX")
      (footprint "eagle-import:TEMP-PAD")
      (libsource (lib "eagle-import") (part "PIC-RPX"))
    )
    (comp (ref "O17")
      (value "PIC-OUT")
      (footprint "eagle-import:TEMP-PAD")
      (libsource (lib "eagle-import") (part "PIC-OUT"))
    )
    (comp (ref "O18")
      (value "PIC-RPX")
      (footprint "eagle-import:TEMP-PAD")
      (libsource (lib "eagle-import") (part "PIC-RPX"))
    )
    (comp (ref "O19")
      (value "PIC-RPX")
      (footprint "eagle-import:TEMP-PAD")
      (libsource (lib "eagle-import") (part "PIC-RPX"))
    )
    (comp (ref "O20")
      (value "PIC-RPX")
      (footprint "eagle-import:TEMP-PAD")
      (libsource (lib "eagle-import") (part "PIC-RPX"))
    )
    (comp (ref "O21")
      (value "PIC-RPX")
      (footprint "eagle-import:TEMP-PAD")
      (libsource (lib "eagle-import") (part "PIC-RPX"))
    )
    (comp (ref "O22")
      (value "PIC-RPX")
      (footprint "eagle-import:TEMP-PAD")
      (libsource (lib "eagle-import") (part "PIC-RPX"))
    )
    (comp (ref "O23")
      (value "PIC-OUT")
      (footprint "eagle-import:TEMP-PAD")
      (libsource (lib "eagle-import") (part "PIC-OUT"))
    )
    (comp (ref "O24")
      (value "PIC-RPX")
      (footprint "eagle-import:TEMP-PAD")
      (libsource (lib "eagle-import") (part "PIC-RPX"))
    )
    (comp (ref "O25")
      (value "PIC-RPX")
      (footprint "eagle-import:TEMP-PAD")
      (libsource (lib "eagle-import") (part "PIC-RPX"))
    )
    (comp (ref "O26")
      (value "PIC-RPX")
      (footprint "eagle-import:TEMP-PAD")
      (libsource (lib "eagle-import") (part "PIC-RPX"))
    )
    (comp (ref "O27")
      (value "PIC-RPX")
      (footprint "eagle-import:TEMP-PAD")
      (libsource (lib "eagle-import") (part "PIC-RPX"))
    )
    (comp (ref "O28")
      (value "PIC-RPX")
      (footprint "eagle-import:TEMP-PAD")
      (libsource (lib "eagle-import") (part "PIC-RPX"))
    )
    (comp (ref "O29")
      (value "PIC-OUT")
      (footprint "eagle-import:TEMP-PAD")
      (libsource (lib "eagle-import") (part "PIC-OUT"))
    )
    (comp (ref "O35")
      (value "PIC-RPX")
      (footprint "eagle-import:TEMP-PAD")
      (libsource (lib "eagle-import") (part "PIC-RPX"))
    )
    (comp (ref "O39")
      (value "PIC-OUT")
      (footprint "eagle-import:TEMP-PAD")
      (libsource (lib "eagle-import") (part "PIC-OUT"))
    )
    (comp (ref "O40")
      (value "PIC-OUT")
      (footprint "eagle-import:TEMP-PAD")
      (libsource (lib "eagle-import") (part "PIC-OUT"))
    )
    (comp (ref "O53")
      (value "PIC-RPX")
      (footprint "eagle-import:TEMP-PAD")
      (libsource (lib "eagle-import") (part "PIC-RPX"))
    )
    (comp (ref "O55")
      (value "PIC-OUT")
      (footprint "eagle-import:TEMP-PAD")
      (libsource (lib "eagle-import") (part "PIC-OUT"))
    )
    (comp (ref "O58")
      (value "PIC-OUT")
      (footprint "eagle-import:TEMP-PAD")
      (libsource (lib "eagle-import") (part "PIC-OUT"))
    )
    (comp (ref "O59")
      (value "PIC-RPX")
      (footprint "eagle-import:TEMP-PAD")
      (libsource (lib "eagle-import") (part "PIC-RPX"))
    )
    (comp (ref "O60")
      (value "PIC-RPX")
      (footprint "eagle-import:TEMP-PAD")
      (libsource (lib "eagle-import") (part "PIC-RPX"))
    )
    (comp (ref "PCB1")
      (value "PCB-ICBE")
      (footprint "eagle-import:PCB-ICBE")
      (libsource (lib "eagle-import") (part "PCB-ICBE"))
    )
    (comp (ref "PCB2")
      (value "NDP-PCB-ICB")
      (footprint "eagle-import:PCB-ICB")
      (libsource (lib "eagle-import") (part "PCB-ICB"))
    )
    (comp (ref "PCB3")
      (value "DNP-PCB-BT")
      (footprint "eagle-import:BT_MODULE_BRD")
      (libsource (lib "eagle-import") (part "BT_PCBBRD"))
    )
    (comp (ref "Q1")
      (value "SSM6P49NU,LFPZ")
      (footprint "eagle-import:MICRO_FET")
      (libsource (lib "eagle-import") (part "SSM6P49PZNU,LF"))
    )
    (comp (ref "Q2")
      (value "SSM6P49NU,LFPZ")
      (footprint "eagle-import:MICRO_FET")
      (libsource (lib "eagle-import") (part "SSM6P49PZNU,LF"))
    )
    (comp (ref "Q3")
      (value "Si3421DV")
      (footprint "eagle-import:SSOT-6")
      (libsource (lib "eagle-import") (part "FDC658AP"))
    )
    (comp (ref "Q4")
      (value "FDG6303N")
      (footprint "eagle-import:SC70-6")
      (libsource (lib "eagle-import") (part "FDG6303N"))
    )
    (comp (ref "Q5")
      (value "Si3421DV")
      (footprint "eagle-import:SSOT-6")
      (libsource (lib "eagle-import") (part "FDC658AP"))
    )
    (comp (ref "Q6")
      (value "FDG6303N")
      (footprint "eagle-import:SC70-6")
      (libsource (lib "eagle-import") (part "FDG6303N"))
    )
    (comp (ref "Q7")
      (value "Si3421DV")
      (footprint "eagle-import:SSOT-6")
      (libsource (lib "eagle-import") (part "FDC658AP"))
    )
    (comp (ref "Q8")
      (value "Si3421DV")
      (footprint "eagle-import:SSOT-6")
      (libsource (lib "eagle-import") (part "FDC658AP"))
    )
    (comp (ref "Q9")
      (value "FDG6303N")
      (footprint "eagle-import:SC70-6")
      (libsource (lib "eagle-import") (part "FDG6303N"))
    )
    (comp (ref "Q10")
      (value "FDG6303N")
      (footprint "eagle-import:SC70-6")
      (libsource (lib "eagle-import") (part "FDG6303N"))
    )
    (comp (ref "R1")
      (value "300k")
      (footprint "eagle-import:0603")
      (libsource (lib "eagle-import") (part "R-0603"))
    )
    (comp (ref "R2")
      (value "0R")
      (footprint "eagle-import:0603")
      (libsource (lib "eagle-import") (part "R-0603"))
    )
    (comp (ref "R3")
      (value "100R")
      (footprint "eagle-import:0603")
      (libsource (lib "eagle-import") (part "R-0603"))
    )
    (comp (ref "R4")
      (value "10R")
      (footprint "eagle-import:0603")
      (libsource (lib "eagle-import") (part "R-0603"))
    )
    (comp (ref "R5")
      (value "100k??")
      (footprint "eagle-import:0603")
      (libsource (lib "eagle-import") (part "R-0603"))
    )
    (comp (ref "R6")
      (value "100k")
      (footprint "eagle-import:0603")
      (libsource (lib "eagle-import") (part "R-0603"))
    )
    (comp (ref "R7")
      (value "100k")
      (footprint "eagle-import:0603")
      (libsource (lib "eagle-import") (part "R-0603"))
    )
    (comp (ref "R8")
      (value "100k")
      (footprint "eagle-import:0603")
      (libsource (lib "eagle-import") (part "R-0603"))
    )
    (comp (ref "R9")
      (value "100k")
      (footprint "eagle-import:0603")
      (libsource (lib "eagle-import") (part "R-0603"))
    )
    (comp (ref "R10")
      (value "1M")
      (footprint "eagle-import:0603")
      (libsource (lib "eagle-import") (part "R-0603"))
    )
    (comp (ref "R11")
      (value "1M")
      (footprint "eagle-import:0603")
      (libsource (lib "eagle-import") (part "R-0603"))
    )
    (comp (ref "R12")
      (value "300k")
      (footprint "eagle-import:0603")
      (libsource (lib "eagle-import") (part "R-0603"))
    )
    (comp (ref "R13")
      (value "1M")
      (footprint "eagle-import:0603")
      (libsource (lib "eagle-import") (part "R-0603"))
    )
    (comp (ref "R14")
      (value "1M")
      (footprint "eagle-import:0603")
      (libsource (lib "eagle-import") (part "R-0603"))
    )
    (comp (ref "R15")
      (value "300k")
      (footprint "eagle-import:0603")
      (libsource (lib "eagle-import") (part "R-0603"))
    )
    (comp (ref "R16")
      (value "1M")
      (footprint "eagle-import:0603")
      (libsource (lib "eagle-import") (part "R-0603"))
    )
    (comp (ref "R17")
      (value "47k")
      (footprint "eagle-import:0603")
      (libsource (lib "eagle-import") (part "R-0603"))
    )
    (comp (ref "R18")
      (value "10k")
      (footprint "eagle-import:0603")
      (libsource (lib "eagle-import") (part "R-0603"))
    )
    (comp (ref "R19")
      (value "560k")
      (footprint "eagle-import:0603")
      (libsource (lib "eagle-import") (part "R-0603"))
    )
    (comp (ref "R20")
      (value "1M")
      (footprint "eagle-import:0603")
      (libsource (lib "eagle-import") (part "R-0603"))
    )
    (comp (ref "R21")
      (value "1M")
      (footprint "eagle-import:0603")
      (libsource (lib "eagle-import") (part "R-0603"))
    )
    (comp (ref "R22")
      (value "4M99")
      (footprint "eagle-import:0603")
      (libsource (lib "eagle-import") (part "R-0603"))
    )
    (comp (ref "R23")
      (value "0R/1M")
      (footprint "eagle-import:0603")
      (libsource (lib "eagle-import") (part "R-0603"))
    )
    (comp (ref "R24")
      (value "100k")
      (footprint "eagle-import:0603")
      (libsource (lib "eagle-import") (part "R-0603"))
    )
    (comp (ref "R25")
      (value "1M")
      (footprint "eagle-import:0603")
      (libsource (lib "eagle-import") (part "R-0603"))
    )
    (comp (ref "R26")
      (value "10k")
      (footprint "eagle-import:0603")
      (libsource (lib "eagle-import") (part "R-0603"))
    )
    (comp (ref "R27")
      (value "10k")
      (footprint "eagle-import:0603")
      (libsource (lib "eagle-import") (part "R-0603"))
    )
    (comp (ref "R28")
      (value "100R")
      (footprint "eagle-import:0603")
      (libsource (lib "eagle-import") (part "R-0603"))
    )
    (comp (ref "R29")
      (value "300R")
      (footprint "eagle-import:0603")
      (libsource (lib "eagle-import") (part "R-0603"))
    )
    (comp (ref "R30")
      (value "1M")
      (footprint "eagle-import:0603")
      (libsource (lib "eagle-import") (part "R-0603"))
    )
    (comp (ref "R31")
      (value "1M")
      (footprint "eagle-import:0603")
      (libsource (lib "eagle-import") (part "R-0603"))
    )
    (comp (ref "R32")
      (value "1M")
      (footprint "eagle-import:0603")
      (libsource (lib "eagle-import") (part "R-0603"))
    )
    (comp (ref "R33")
      (value "1M")
      (footprint "eagle-import:0603")
      (libsource (lib "eagle-import") (part "R-0603"))
    )
    (comp (ref "R34")
      (value "1M")
      (footprint "eagle-import:0603")
      (libsource (lib "eagle-import") (part "R-0603"))
    )
    (comp (ref "R35")
      (value "0.025R")
      (footprint "eagle-import:0805")
      (libsource (lib "eagle-import") (part "R-0805"))
    )
    (comp (ref "R36")
      (value "1k")
      (footprint "eagle-import:0603")
      (libsource (lib "eagle-import") (part "R-0603"))
    )
    (comp (ref "R37")
      (value "0.025R")
      (footprint "eagle-import:0805")
      (libsource (lib "eagle-import") (part "R-0805"))
    )
    (comp (ref "R38")
      (value "1R")
      (footprint "eagle-import:0805")
      (libsource (lib "eagle-import") (part "R-0805"))
    )
    (comp (ref "R39")
      (value "0.025R")
      (footprint "eagle-import:0805")
      (libsource (lib "eagle-import") (part "R-0805"))
    )
    (comp (ref "R40")
      (value "300k")
      (footprint "eagle-import:0603")
      (libsource (lib "eagle-import") (part "R-0603"))
    )
    (comp (ref "R41")
      (value "300k")
      (footprint "eagle-import:0603")
      (libsource (lib "eagle-import") (part "R-0603"))
    )
    (comp (ref "R42")
      (value "1M")
      (footprint "eagle-import:0603")
      (libsource (lib "eagle-import") (part "R-0603"))
    )
    (comp (ref "R43")
      (value "300k")
      (footprint "eagle-import:0603")
      (libsource (lib "eagle-import") (part "R-0603"))
    )
    (comp (ref "R44")
      (value "300k")
      (footprint "eagle-import:0603")
      (libsource (lib "eagle-import") (part "R-0603"))
    )
    (comp (ref "R45")
      (value "1M")
      (footprint "eagle-import:0603")
      (libsource (lib "eagle-import") (part "R-0603"))
    )
    (comp (ref "R46")
      (value "150k")
      (footprint "eagle-import:0603")
      (libsource (lib "eagle-import") (part "R-0603"))
    )
    (comp (ref "R47")
      (value "47k")
      (footprint "eagle-import:0603")
      (libsource (lib "eagle-import") (part "R-0603"))
    )
    (comp (ref "R48")
      (value "1M")
      (footprint "eagle-import:0603")
      (libsource (lib "eagle-import") (part "R-0603"))
    )
    (comp (ref "R49")
      (value "1M")
      (footprint "eagle-import:0603")
      (libsource (lib "eagle-import") (part "R-0603"))
    )
    (comp (ref "R50")
      (value "100k")
      (footprint "eagle-import:0603")
      (libsource (lib "eagle-import") (part "R-0603"))
    )
    (comp (ref "R51")
      (value "1M")
      (footprint "eagle-import:0603")
      (libsource (lib "eagle-import") (part "R-0603"))
    )
    (comp (ref "R52")
      (value "1R")
      (footprint "eagle-import:0805")
      (libsource (lib "eagle-import") (part "R-0805"))
    )
    (comp (ref "R53")
      (value "10k")
      (footprint "eagle-import:0603")
      (libsource (lib "eagle-import") (part "R-0603"))
    )
    (comp (ref "R54")
      (value "300k-DNP?")
      (footprint "eagle-import:0603")
      (libsource (lib "eagle-import") (part "R-0603"))
    )
    (comp (ref "R55")
      (value "100k")
      (footprint "eagle-import:0603")
      (libsource (lib "eagle-import") (part "R-0603"))
    )
    (comp (ref "R56")
      (value "100k")
      (footprint "eagle-import:0603")
      (libsource (lib "eagle-import") (part "R-0603"))
    )
    (comp (ref "R57")
      (value "100k")
      (footprint "eagle-import:0603")
      (libsource (lib "eagle-import") (part "R-0603"))
    )
    (comp (ref "R58")
      (value "10k")
      (footprint "eagle-import:0603")
      (libsource (lib "eagle-import") (part "R-0603"))
    )
    (comp (ref "R59")
      (value "10k")
      (footprint "eagle-import:0603")
      (libsource (lib "eagle-import") (part "R-0603"))
    )
    (comp (ref "R60")
      (value "10k")
      (footprint "eagle-import:0603")
      (libsource (lib "eagle-import") (part "R-0603"))
    )
    (comp (ref "R61")
      (value "100R")
      (footprint "eagle-import:0603")
      (libsource (lib "eagle-import") (part "R-0603"))
    )
    (comp (ref "R62")
      (value "2k2")
      (footprint "eagle-import:0603")
      (libsource (lib "eagle-import") (part "R-0603"))
    )
    (comp (ref "R63")
      (value "1k")
      (footprint "eagle-import:0603")
      (libsource (lib "eagle-import") (part "R-0603"))
    )
    (comp (ref "R64")
      (value "300k")
      (footprint "eagle-import:0603")
      (libsource (lib "eagle-import") (part "R-0603"))
    )
    (comp (ref "R65")
      (value "1M")
      (footprint "eagle-import:0603")
      (libsource (lib "eagle-import") (part "R-0603"))
    )
    (comp (ref "R66")
      (value "1k")
      (footprint "eagle-import:0603")
      (libsource (lib "eagle-import") (part "R-0603"))
    )
    (comp (ref "R67")
      (value "1k")
      (footprint "eagle-import:0603")
      (libsource (lib "eagle-import") (part "R-0603"))
    )
    (comp (ref "R68")
      (value "1k")
      (footprint "eagle-import:0603")
      (libsource (lib "eagle-import") (part "R-0603"))
    )
    (comp (ref "R69")
      (value "1k")
      (footprint "eagle-import:0603")
      (libsource (lib "eagle-import") (part "R-0603"))
    )
    (comp (ref "R70")
      (value "1M")
      (footprint "eagle-import:0603")
      (libsource (lib "eagle-import") (part "R-0603"))
    )
    (comp (ref "R71")
      (value "10k")
      (footprint "eagle-import:0603")
      (libsource (lib "eagle-import") (part "R-0603"))
    )
    (comp (ref "R72")
      (value "100k")
      (footprint "eagle-import:0603")
      (libsource (lib "eagle-import") (part "R-0603"))
    )
    (comp (ref "R73")
      (value "2k2")
      (footprint "eagle-import:0603")
      (libsource (lib "eagle-import") (part "R-0603"))
    )
    (comp (ref "R74")
      (value "1k")
      (footprint "eagle-import:0603")
      (libsource (lib "eagle-import") (part "R-0603"))
    )
    (comp (ref "R75")
      (value "10k")
      (footprint "eagle-import:0603")
      (libsource (lib "eagle-import") (part "R-0603"))
    )
    (comp (ref "R76")
      (value "300k")
      (footprint "eagle-import:0603")
      (libsource (lib "eagle-import") (part "R-0603"))
    )
    (comp (ref "R77")
      (value "47k")
      (footprint "eagle-import:0603")
      (libsource (lib "eagle-import") (part "R-0603"))
    )
    (comp (ref "R78")
      (value "100R")
      (footprint "eagle-import:0603")
      (libsource (lib "eagle-import") (part "R-0603"))
    )
    (comp (ref "R79")
      (value "100R")
      (footprint "eagle-import:0603")
      (libsource (lib "eagle-import") (part "R-0603"))
    )
    (comp (ref "R80")
      (value "100R")
      (footprint "eagle-import:0603")
      (libsource (lib "eagle-import") (part "R-0603"))
    )
    (comp (ref "R81")
      (value "100R")
      (footprint "eagle-import:0603")
      (libsource (lib "eagle-import") (part "R-0603"))
    )
    (comp (ref "R82")
      (value "100k")
      (footprint "eagle-import:0603")
      (libsource (lib "eagle-import") (part "R-0603"))
    )
    (comp (ref "R83")
      (value "1M")
      (footprint "eagle-import:0603")
      (libsource (lib "eagle-import") (part "R-0603"))
    )
    (comp (ref "R84")
      (value "300k")
      (footprint "eagle-import:0603")
      (libsource (lib "eagle-import") (part "R-0603"))
    )
    (comp (ref "R85")
      (value "1M")
      (footprint "eagle-import:0603")
      (libsource (lib "eagle-import") (part "R-0603"))
    )
    (comp (ref "R86")
      (value "1k")
      (footprint "eagle-import:0603")
      (libsource (lib "eagle-import") (part "R-0603"))
    )
    (comp (ref "R87")
      (value "1k")
      (footprint "eagle-import:0603")
      (libsource (lib "eagle-import") (part "R-0603"))
    )
    (comp (ref "R88")
      (value "1M")
      (footprint "eagle-import:0603")
      (libsource (lib "eagle-import") (part "R-0603"))
    )
    (comp (ref "R89")
      (value "1M")
      (footprint "eagle-import:0603")
      (libsource (lib "eagle-import") (part "R-0603"))
    )
    (comp (ref "R90")
      (value "1k")
      (footprint "eagle-import:0603")
      (libsource (lib "eagle-import") (part "R-0603"))
    )
    (comp (ref "R91")
      (value "10k")
      (footprint "eagle-import:0603")
      (libsource (lib "eagle-import") (part "R-0603"))
    )
    (comp (ref "R92")
      (value "10R")
      (footprint "eagle-import:0603")
      (libsource (lib "eagle-import") (part "R-0603"))
    )
    (comp (ref "R93")
      (value "300R")
      (footprint "eagle-import:0603")
      (libsource (lib "eagle-import") (part "R-0603"))
    )
    (comp (ref "R94")
      (value "180k")
      (footprint "eagle-import:0603")
      (libsource (lib "eagle-import") (part "R-0603"))
    )
    (comp (ref "R95")
      (value "4M99")
      (footprint "eagle-import:0603")
      (libsource (lib "eagle-import") (part "R-0603"))
    )
    (comp (ref "R96")
      (value "560k")
      (footprint "eagle-import:0603")
      (libsource (lib "eagle-import") (part "R-0603"))
    )
    (comp (ref "R97")
      (value "180k")
      (footprint "eagle-import:0603")
      (libsource (lib "eagle-import") (part "R-0603"))
    )
    (comp (ref "R98")
      (value "4M99")
      (footprint "eagle-import:0603")
      (libsource (lib "eagle-import") (part "R-0603"))
    )
    (comp (ref "R99")
      (value "560k")
      (footprint "eagle-import:0603")
      (libsource (lib "eagle-import") (part "R-0603"))
    )
    (comp (ref "R100")
      (value "2k2")
      (footprint "eagle-import:0603")
      (libsource (lib "eagle-import") (part "R-0603"))
    )
    (comp (ref "R101")
      (value "2k2")
      (footprint "eagle-import:0603")
      (libsource (lib "eagle-import") (part "R-0603"))
    )
    (comp (ref "R102")
      (value "1k")
      (footprint "eagle-import:0603")
      (libsource (lib "eagle-import") (part "R-0603"))
    )
    (comp (ref "R103")
      (value "300R")
      (footprint "eagle-import:0603")
      (libsource (lib "eagle-import") (part "R-0603"))
    )
    (comp (ref "R104")
      (value "10k")
      (footprint "eagle-import:0603")
      (libsource (lib "eagle-import") (part "R-0603"))
    )
    (comp (ref "R105")
      (value "1R")
      (footprint "eagle-import:0805")
      (libsource (lib "eagle-import") (part "R-0805"))
    )
    (comp (ref "R106")
      (value "1R")
      (footprint "eagle-import:0805")
      (libsource (lib "eagle-import") (part "R-0805"))
    )
    (comp (ref "R107")
      (value "10k")
      (footprint "eagle-import:0603")
      (libsource (lib "eagle-import") (part "R-0603"))
    )
    (comp (ref "R108")
      (value "10R->1R->0R")
      (footprint "eagle-import:0603")
      (libsource (lib "eagle-import") (part "R-0603"))
    )
    (comp (ref "R109")
      (value "10R->1R->0R")
      (footprint "eagle-import:0603")
      (libsource (lib "eagle-import") (part "R-0603"))
    )
    (comp (ref "R110")
      (value "10k")
      (footprint "eagle-import:0603")
      (libsource (lib "eagle-import") (part "R-0603"))
    )
    (comp (ref "R111")
      (value "10k")
      (footprint "eagle-import:0603")
      (libsource (lib "eagle-import") (part "R-0603"))
    )
    (comp (ref "R112")
      (value "1k")
      (footprint "eagle-import:0603")
      (libsource (lib "eagle-import") (part "R-0603"))
    )
    (comp (ref "R113")
      (value "1k")
      (footprint "eagle-import:0603")
      (libsource (lib "eagle-import") (part "R-0603"))
    )
    (comp (ref "R114")
      (value "10R")
      (footprint "eagle-import:0603")
      (libsource (lib "eagle-import") (part "R-0603"))
    )
    (comp (ref "R115")
      (value "10R")
      (footprint "eagle-import:0603")
      (libsource (lib "eagle-import") (part "R-0603"))
    )
    (comp (ref "R116")
      (value "100R")
      (footprint "eagle-import:0603")
      (libsource (lib "eagle-import") (part "R-0603"))
    )
    (comp (ref "R117")
      (value "100R")
      (footprint "eagle-import:0603")
      (libsource (lib "eagle-import") (part "R-0603"))
    )
    (comp (ref "R118")
      (value "2k2")
      (footprint "eagle-import:0603")
      (libsource (lib "eagle-import") (part "R-0603"))
    )
    (comp (ref "R119")
      (value "100R")
      (footprint "eagle-import:0603")
      (libsource (lib "eagle-import") (part "R-0603"))
    )
    (comp (ref "R120")
      (value "10k")
      (footprint "eagle-import:0603")
      (libsource (lib "eagle-import") (part "R-0603"))
    )
    (comp (ref "R121")
      (value "300k")
      (footprint "eagle-import:0603")
      (libsource (lib "eagle-import") (part "R-0603"))
    )
    (comp (ref "R122")
      (value "1k")
      (footprint "eagle-import:0603")
      (libsource (lib "eagle-import") (part "R-0603"))
    )
    (comp (ref "R123")
      (value "1k")
      (footprint "eagle-import:0603")
      (libsource (lib "eagle-import") (part "R-0603"))
    )
    (comp (ref "R124")
      (value "1k")
      (footprint "eagle-import:0603")
      (libsource (lib "eagle-import") (part "R-0603"))
    )
    (comp (ref "R125")
      (value "100k")
      (footprint "eagle-import:0603")
      (libsource (lib "eagle-import") (part "R-0603"))
    )
    (comp (ref "R126")
      (value "1M")
      (footprint "eagle-import:0603")
      (libsource (lib "eagle-import") (part "R-0603"))
    )
    (comp (ref "R127")
      (value "1R")
      (footprint "eagle-import:0805")
      (libsource (lib "eagle-import") (part "R-0805"))
    )
    (comp (ref "R128")
      (value "10k")
      (footprint "eagle-import:0603")
      (libsource (lib "eagle-import") (part "R-0603"))
    )
    (comp (ref "R129")
      (value "0R")
      (footprint "eagle-import:0603")
      (libsource (lib "eagle-import") (part "R-0603"))
    )
    (comp (ref "R130")
      (value "10K")
      (footprint "eagle-import:0603")
      (libsource (lib "eagle-import") (part "R-0603"))
    )
    (comp (ref "R131")
      (value "10K")
      (footprint "eagle-import:0603")
      (libsource (lib "eagle-import") (part "R-0603"))
    )
    (comp (ref "R132")
      (value "100R")
      (footprint "eagle-import:0603")
      (libsource (lib "eagle-import") (part "R-0603"))
    )
    (comp (ref "REF1")
      (value "REF")
      (footprint "eagle-import:REF")
      (libsource (lib "eagle-import") (part "REF"))
    )
    (comp (ref "REF2")
      (value "REF")
      (footprint "eagle-import:REF")
      (libsource (lib "eagle-import") (part "REF"))
    )
    (comp (ref "T1")
      (value "PIC-RPX")
      (footprint "eagle-import:TEMP-PAD")
      (libsource (lib "eagle-import") (part "PIC-RPX"))
    )
    (comp (ref "T2")
      (value "PIC-OUT")
      (footprint "eagle-import:TEMP-PAD")
      (libsource (lib "eagle-import") (part "PIC-OUT"))
    )
    (comp (ref "T3")
      (value "PIC-RPX")
      (footprint "eagle-import:TEMP-PAD")
      (libsource (lib "eagle-import") (part "PIC-RPX"))
    )
    (comp (ref "T4")
      (value "PIC-OUT")
      (footprint "eagle-import:TEMP-PAD")
      (libsource (lib "eagle-import") (part "PIC-OUT"))
    )
    (comp (ref "T5")
      (value "PIC-RPX")
      (footprint "eagle-import:TEMP-PAD")
      (libsource (lib "eagle-import") (part "PIC-RPX"))
    )
    (comp (ref "T6")
      (value "PIC-RPX")
      (footprint "eagle-import:TEMP-PAD")
      (libsource (lib "eagle-import") (part "PIC-RPX"))
    )
    (comp (ref "T7")
      (value "PIC-OUT")
      (footprint "eagle-import:TEMP-PAD")
      (libsource (lib "eagle-import") (part "PIC-OUT"))
    )
    (comp (ref "T8")
      (value "PIC-RPX")
      (footprint "eagle-import:TEMP-PAD")
      (libsource (lib "eagle-import") (part "PIC-RPX"))
    )
    (comp (ref "T9")
      (value "PIC-RPX")
      (footprint "eagle-import:TEMP-PAD")
      (libsource (lib "eagle-import") (part "PIC-RPX"))
    )
    (comp (ref "T10")
      (value "PIC-RPX")
      (footprint "eagle-import:TEMP-PAD")
      (libsource (lib "eagle-import") (part "PIC-RPX"))
    )
    (comp (ref "T11")
      (value "PIC-OUT")
      (footprint "eagle-import:TEMP-PAD")
      (libsource (lib "eagle-import") (part "PIC-OUT"))
    )
    (comp (ref "T12")
      (value "PIC-RPX")
      (footprint "eagle-import:TEMP-PAD")
      (libsource (lib "eagle-import") (part "PIC-RPX"))
    )
    (comp (ref "T16")
      (value "PIC-RPX")
      (footprint "eagle-import:TEMP-PAD")
      (libsource (lib "eagle-import") (part "PIC-RPX"))
    )
    (comp (ref "T17")
      (value "PIC-OUT")
      (footprint "eagle-import:TEMP-PAD")
      (libsource (lib "eagle-import") (part "PIC-OUT"))
    )
    (comp (ref "T18")
      (value "PIC-OUT")
      (footprint "eagle-import:TEMP-PAD")
      (libsource (lib "eagle-import") (part "PIC-OUT"))
    )
    (comp (ref "T19")
      (value "PIC-RPX")
      (footprint "eagle-import:TEMP-PAD")
      (libsource (lib "eagle-import") (part "PIC-RPX"))
    )
    (comp (ref "T20")
      (value "PIC-OUT")
      (footprint "eagle-import:TEMP-PAD")
      (libsource (lib "eagle-import") (part "PIC-OUT"))
    )
    (comp (ref "T21")
      (value "PIC-RPX")
      (footprint "eagle-import:TEMP-PAD")
      (libsource (lib "eagle-import") (part "PIC-RPX"))
    )
    (comp (ref "T23")
      (value "PIC-OUT")
      (footprint "eagle-import:TEMP-PAD")
      (libsource (lib "eagle-import") (part "PIC-OUT"))
    )
    (comp (ref "T24")
      (value "PIC-OUT")
      (footprint "eagle-import:TEMP-PAD")
      (libsource (lib "eagle-import") (part "PIC-OUT"))
    )
    (comp (ref "T25")
      (value "PIC-OUT")
      (footprint "eagle-import:TEMP-PAD")
      (libsource (lib "eagle-import") (part "PIC-OUT"))
    )
    (comp (ref "T26")
      (value "PIC-RPX")
      (footprint "eagle-import:TEMP-PAD")
      (libsource (lib "eagle-import") (part "PIC-RPX"))
    )
    (comp (ref "T28")
      (value "PIC-RPX")
      (footprint "eagle-import:TEMP-PAD")
      (libsource (lib "eagle-import") (part "PIC-RPX"))
    )
    (comp (ref "T29")
      (value "PIC-OUT")
      (footprint "eagle-import:TEMP-PAD")
      (libsource (lib "eagle-import") (part "PIC-OUT"))
    )
    (comp (ref "T30")
      (value "PIC-OUT")
      (footprint "eagle-import:TEMP-PAD")
      (libsource (lib "eagle-import") (part "PIC-OUT"))
    )
    (comp (ref "T31")
      (value "PIC-RPX")
      (footprint "eagle-import:TEMP-PAD")
      (libsource (lib "eagle-import") (part "PIC-RPX"))
    )
    (comp (ref "T34")
      (value "PIC-RPX")
      (footprint "eagle-import:TEMP-PAD")
      (libsource (lib "eagle-import") (part "PIC-RPX"))
    )
    (comp (ref "T35")
      (value "PIC-OUT")
      (footprint "eagle-import:TEMP-PAD")
      (libsource (lib "eagle-import") (part "PIC-OUT"))
    )
    (comp (ref "T45")
      (value "PIC-RPX")
      (footprint "eagle-import:TEMP-PAD")
      (libsource (lib "eagle-import") (part "PIC-RPX"))
    )
    (comp (ref "T46")
      (value "PIC-OUT")
      (footprint "eagle-import:TEMP-PAD")
      (libsource (lib "eagle-import") (part "PIC-OUT"))
    )
    (comp (ref "T47")
      (value "PIC-OUT")
      (footprint "eagle-import:TEMP-PAD")
      (libsource (lib "eagle-import") (part "PIC-OUT"))
    )
    (comp (ref "T48")
      (value "PIC-RPX")
      (footprint "eagle-import:TEMP-PAD")
      (libsource (lib "eagle-import") (part "PIC-RPX"))
    )
    (comp (ref "T49")
      (value "PIC-OUT")
      (footprint "eagle-import:TEMP-PAD")
      (libsource (lib "eagle-import") (part "PIC-OUT"))
    )
    (comp (ref "T50")
      (value "PIC-RPX")
      (footprint "eagle-import:TEMP-PAD")
      (libsource (lib "eagle-import") (part "PIC-RPX"))
    )
    (comp (ref "T57")
      (value "PIC-RPX")
      (footprint "eagle-import:TEMP-PAD")
      (libsource (lib "eagle-import") (part "PIC-RPX"))
    )
    (comp (ref "T61")
      (value "PIC-OUT")
      (footprint "eagle-import:TEMP-PAD")
      (libsource (lib "eagle-import") (part "PIC-OUT"))
    )
    (comp (ref "T62")
      (value "PIC-RPX")
      (footprint "eagle-import:TEMP-PAD")
      (libsource (lib "eagle-import") (part "PIC-RPX"))
    )
    (comp (ref "TP1")
      (value "DNP-TestPoint")
      (footprint "eagle-import:SMD_ROUND_1MM")
      (libsource (lib "eagle-import") (part "ROUND_SMD1MM"))
    )
    (comp (ref "TP4")
      (value "DNP-TestPoint")
      (footprint "eagle-import:TH_ROUND_14MM08MM")
      (libsource (lib "eagle-import") (part "ROUND_SMDTH1.4MM"))
    )
    (comp (ref "X1")
      (value "8MHz-5x3.2mm")
      (footprint "eagle-import:7B")
      (libsource (lib "eagle-import") (part "XTAL-7B"))
    )
  )
  (nets
    (net (code "1") (name "+3.3V") (class "Default")
      (node (ref "C43") (pin "1") (pinfunction "1_1") (pintype "passive"))
      (node (ref "C47") (pin "1") (pinfunction "1_1") (pintype "passive"))
      (node (ref "C48") (pin "1") (pinfunction "1_1") (pintype "passive"))
      (node (ref "C49") (pin "1") (pinfunction "1_1") (pintype "passive"))
      (node (ref "C50") (pin "1") (pinfunction "1_1") (pintype "passive"))
      (node (ref "C51") (pin "1") (pinfunction "1_1") (pintype "passive"))
      (node (ref "C52") (pin "1") (pinfunction "1_1") (pintype "passive"))
      (node (ref "C69") (pin "1") (pinfunction "1_1") (pintype "passive"))
      (node (ref "C70") (pin "1") (pinfunction "1_1") (pintype "passive"))
      (node (ref "C81") (pin "+") (pinfunction "+_+") (pintype "passive"))
      (node (ref "C82") (pin "1") (pinfunction "1_1") (pintype "passive"))
      (node (ref "IC1") (pin "16") (pinfunction "VDD3_16") (pintype "input"))
      (node (ref "IC1") (pin "2") (pinfunction "VDD2_2") (pintype "input"))
      (node (ref "IC1") (pin "37") (pinfunction "VDD4_37") (pintype "input"))
      (node (ref "IC1") (pin "46") (pinfunction "VDD5_46") (pintype "input"))
      (node (ref "IC1") (pin "55") (pinfunction "VUSB3V3_55") (pintype "input"))
      (node (ref "IC1") (pin "62") (pinfunction "VDD6_62") (pintype "input"))
      (node (ref "IC1") (pin "86") (pinfunction "VDD1_86") (pintype "input"))
      (node (ref "J17") (pin "2") (pinfunction "2_2") (pintype "passive"))
      (node (ref "L13") (pin "1") (pinfunction "1_1") (pintype "passive"))
      (node (ref "R103") (pin "2") (pinfunction "2_2") (pintype "passive"))
      (node (ref "R104") (pin "1") (pinfunction "1_1") (pintype "passive"))
      (node (ref "R105") (pin "2") (pinfunction "2_2") (pintype "passive"))
      (node (ref "R106") (pin "2") (pinfunction "2_2") (pintype "passive"))
      (node (ref "R114") (pin "1") (pinfunction "1_1") (pintype "passive"))
      (node (ref "R115") (pin "2") (pinfunction "2_2") (pintype "passive"))
      (node (ref "R117") (pin "2") (pinfunction "2_2") (pintype "passive"))
      (node (ref "R126") (pin "1") (pinfunction "1_1") (pintype "passive"))
      (node (ref "R127") (pin "2") (pinfunction "2_2") (pintype "passive"))
      (node (ref "R129") (pin "1") (pinfunction "1_1") (pintype "passive"))
      (node (ref "R132") (pin "1") (pinfunction "1_1") (pintype "passive"))
      (node (ref "R28") (pin "2") (pinfunction "2_2") (pintype "passive"))
      (node (ref "R3") (pin "1") (pinfunction "1_1") (pintype "passive"))
      (node (ref "R38") (pin "2") (pinfunction "2_2") (pintype "passive"))
      (node (ref "R51") (pin "1") (pinfunction "1_1") (pintype "passive"))
      (node (ref "R52") (pin "2") (pinfunction "2_2") (pintype "passive"))
      (node (ref "R65") (pin "1") (pinfunction "1_1") (pintype "passive"))
      (node (ref "R82") (pin "1") (pinfunction "1_1") (pintype "passive"))
      (node (ref "R91") (pin "2") (pinfunction "2_2") (pintype "passive"))
    )
    (net (code "2") (name "+3.3V{slash}1") (class "Default")
      (node (ref "C27") (pin "1") (pinfunction "1_1") (pintype "passive"))
      (node (ref "C28") (pin "1") (pinfunction "1_1") (pintype "passive"))
      (node (ref "C75") (pin "1") (pinfunction "1_1") (pintype "passive"))
      (node (ref "IC11") (pin "2") (pinfunction "A1_2") (pintype "input"))
      (node (ref "IC11") (pin "8") (pinfunction "VCC_8") (pintype "input"))
      (node (ref "IC24") (pin "7") (pinfunction "A0_7") (pintype "input"))
      (node (ref "IC24") (pin "8") (pinfunction "VCC_8") (pintype "input"))
      (node (ref "IC7") (pin "8") (pinfunction "VCC_8") (pintype "input"))
      (node (ref "IC9") (pin "3") (pinfunction "/WP_3") (pintype "input"))
      (node (ref "IC9") (pin "7") (pinfunction "/HOLD_7") (pintype "input"))
      (node (ref "IC9") (pin "8") (pinfunction "VCC_8") (pintype "input"))
      (node (ref "Q2") (pin "3") (pinfunction "D_3") (pintype "passive"))
      (node (ref "Q2") (pin "P2") (pinfunction "D1_P2") (pintype "passive"))
      (node (ref "R18") (pin "1") (pinfunction "1_1") (pintype "passive"))
      (node (ref "R25") (pin "2") (pinfunction "2_2") (pintype "passive"))
      (node (ref "R26") (pin "1") (pinfunction "1_1") (pintype "passive"))
      (node (ref "R27") (pin "1") (pinfunction "1_1") (pintype "passive"))
    )
    (net (code "3") (name "+3.3V{slash}2") (class "Default")
      (node (ref "C41") (pin "1") (pinfunction "1_1") (pintype "passive"))
      (node (ref "C86") (pin "+") (pinfunction "+_+") (pintype "passive"))
      (node (ref "C97") (pin "2") (pinfunction "2_2") (pintype "passive"))
      (node (ref "IC12") (pin "8") (pinfunction "VCC_8") (pintype "input"))
      (node (ref "IC18") (pin "5") (pinfunction "VCC_5") (pintype "input"))
      (node (ref "IC2") (pin "5") (pinfunction "VCC_5") (pintype "input"))
      (node (ref "IC21") (pin "5") (pinfunction "VCC_5") (pintype "input"))
      (node (ref "IC5") (pin "5") (pinfunction "VCC_5") (pintype "input"))
      (node (ref "Q2") (pin "6") (pinfunction "D_6") (pintype "passive"))
      (node (ref "Q2") (pin "P1") (pinfunction "D1_P1") (pintype "passive"))
      (node (ref "R30") (pin "2") (pinfunction "2_2") (pintype "passive"))
      (node (ref "R34") (pin "1") (pinfunction "1_1") (pintype "passive"))
      (node (ref "R55") (pin "1") (pinfunction "1_1") (pintype "passive"))
      (node (ref "R72") (pin "1") (pinfunction "1_1") (pintype "passive"))
    )
    (net (code "4") (name "+3.3V{slash}ICB") (class "Default")
      (node (ref "C80") (pin "1") (pinfunction "1_1") (pintype "passive"))
      (node (ref "C91") (pin "1") (pinfunction "1_1") (pintype "passive"))
      (node (ref "C92") (pin "1") (pinfunction "1_1") (pintype "passive"))
      (node (ref "C93") (pin "1") (pinfunction "1_1") (pintype "passive"))
      (node (ref "C94") (pin "1") (pinfunction "1_1") (pintype "passive"))
      (node (ref "C95") (pin "1") (pinfunction "1_1") (pintype "passive"))
      (node (ref "C96") (pin "1") (pinfunction "1_1") (pintype "passive"))
      (node (ref "IC19") (pin "1") (pinfunction "A_1") (pintype "input"))
      (node (ref "IC20") (pin "1") (pinfunction "A_1") (pintype "input"))
      (node (ref "IC26") (pin "4") (pinfunction "4_4") (pintype "input"))
      (node (ref "IC29") (pin "10") (pinfunction "VCC_10") (pintype "input"))
      (node (ref "IC29") (pin "19") (pinfunction "VCC_19") (pintype "input"))
      (node (ref "IC29") (pin "24") (pinfunction "VCC_24") (pintype "input"))
      (node (ref "IC29") (pin "3") (pinfunction "VCC_3") (pintype "input"))
      (node (ref "J1") (pin "33") (pinfunction "+3.3V_33") (pintype "passive"))
      (node (ref "J6") (pin "6") (pinfunction "6_6") (pintype "passive"))
      (node (ref "R110") (pin "1") (pinfunction "1_1") (pintype "passive"))
      (node (ref "R121") (pin "2") (pinfunction "2_2") (pintype "passive"))
      (node (ref "R53") (pin "2") (pinfunction "2_2") (pintype "passive"))
      (node (ref "R54") (pin "2") (pinfunction "2_2") (pintype "passive"))
    )
    (net (code "5") (name "/+3.3V-ULTRASONIC") (class "Default")
      (node (ref "C44") (pin "2") (pinfunction "2_2") (pintype "passive"))
      (node (ref "IC27") (pin "4") (pinfunction "4_4") (pintype "input"))
      (node (ref "J16") (pin "3") (pinfunction "3_3") (pintype "passive"))
      (node (ref "Q1") (pin "6") (pinfunction "D_6") (pintype "passive"))
      (node (ref "Q1") (pin "P1") (pinfunction "D1_P1") (pintype "passive"))
    )
    (net (code "6") (name "/+3.3VCCR") (class "Default")
      (node (ref "C78") (pin "2") (pinfunction "2_2") (pintype "passive"))
      (node (ref "J5") (pin "9") (pinfunction "9_9") (pintype "passive"))
      (node (ref "R115") (pin "1") (pinfunction "1_1") (pintype "passive"))
    )
    (net (code "7") (name "/+3.3V{slash}I2C") (class "Default")
      (node (ref "C87") (pin "2") (pinfunction "2_2") (pintype "passive"))
      (node (ref "IC28") (pin "4") (pinfunction "4_4") (pintype "input"))
      (node (ref "J22") (pin "3") (pinfunction "3_3") (pintype "passive"))
      (node (ref "Q1") (pin "3") (pinfunction "D_3") (pintype "passive"))
      (node (ref "Q1") (pin "P2") (pinfunction "D1_P2") (pintype "passive"))
      (node (ref "R130") (pin "1") (pinfunction "1_1") (pintype "passive"))
      (node (ref "R131") (pin "1") (pinfunction "1_1") (pintype "passive"))
    )
    (net (code "8") (name "/3.3V-BT") (class "Default")
      (node (ref "C42") (pin "1") (pinfunction "1_1") (pintype "passive"))
      (node (ref "J14") (pin "2") (pinfunction "2_2") (pintype "passive"))
      (node (ref "R38") (pin "1") (pinfunction "1_1") (pintype "passive"))
    )
    (net (code "9") (name "/3.3V2PWRON-ICB") (class "Default")
      (node (ref "J1") (pin "14") (pinfunction "GPIO133_14") (pintype "passive"))
      (node (ref "Q9") (pin "5") (pinfunction "G_5") (pintype "passive"))
    )
    (net (code "10") (name "/A+") (class "Default")
      (node (ref "J3") (pin "4") (pinfunction "4_4") (pintype "passive"))
      (node (ref "J4") (pin "4") (pinfunction "4_4") (pintype "passive"))
      (node (ref "L8") (pin "2") (pinfunction "2_2") (pintype "passive"))
    )
    (net (code "11") (name "/A++") (class "Default")
      (node (ref "IC12") (pin "6") (pinfunction "A_6") (pintype "bidirectional"))
      (node (ref "IC14") (pin "3") (pinfunction "3_3") (pintype "passive"))
      (node (ref "R109") (pin "2") (pinfunction "2_2") (pintype "passive"))
      (node (ref "R32") (pin "2") (pinfunction "2_2") (pintype "passive"))
      (node (ref "R34") (pin "2") (pinfunction "2_2") (pintype "passive"))
    )
    (net (code "12") (name "/AUDIO-IN") (class "Default")
      (node (ref "C20") (pin "1") (pinfunction "1_1") (pintype "passive"))
      (node (ref "J13") (pin "2") (pinfunction "2_2") (pintype "passive"))
    )
    (net (code "13") (name "/AUDIO-PWRON") (class "Default")
      (node (ref "IC1") (pin "90") (pinfunction "RPG0/PMD8/RG0_90") (pintype "bidirectional"))
      (node (ref "O14") (pin "P$1") (pinfunction "TP_P$1") (pintype "passive"))
      (node (ref "Q6") (pin "5") (pinfunction "G_5") (pintype "passive"))
      (node (ref "R13") (pin "1") (pinfunction "1_1") (pintype "passive"))
      (node (ref "T25") (pin "P$1") (pinfunction "TP_P$1") (pintype "passive"))
    )
    (net (code "14") (name "/AUD_IN+") (class "Default")
      (node (ref "C20") (pin "2") (pinfunction "2_2") (pintype "passive"))
      (node (ref "IC25") (pin "12") (pinfunction "INP_12") (pintype "input"))
    )
    (net (code "15") (name "/AUD_IN-") (class "Default")
      (node (ref "C21") (pin "2") (pinfunction "2_2") (pintype "passive"))
      (node (ref "IC25") (pin "11") (pinfunction "INN_11") (pintype "input"))
    )
    (net (code "16") (name "/B-") (class "Default")
      (node (ref "J3") (pin "5") (pinfunction "5_5") (pintype "passive"))
      (node (ref "J4") (pin "5") (pinfunction "5_5") (pintype "passive"))
      (node (ref "L7") (pin "2") (pinfunction "2_2") (pintype "passive"))
    )
    (net (code "17") (name "/B--") (class "Default")
      (node (ref "IC12") (pin "7") (pinfunction "B_7") (pintype "bidirectional"))
      (node (ref "IC14") (pin "2") (pinfunction "2_2") (pintype "passive"))
      (node (ref "R108") (pin "2") (pinfunction "2_2") (pintype "passive"))
      (node (ref "R31") (pin "1") (pinfunction "1_1") (pintype "passive"))
      (node (ref "R32") (pin "1") (pinfunction "1_1") (pintype "passive"))
    )
    (net (code "18") (name "/BSN") (class "Default")
      (node (ref "C14") (pin "2") (pinfunction "2_2") (pintype "passive"))
      (node (ref "IC25") (pin "22") (pinfunction "BSN_22") (pintype "input"))
      (node (ref "IC25") (pin "26") (pinfunction "BSN_26") (pintype "input"))
    )
    (net (code "19") (name "/BSP") (class "Default")
      (node (ref "C13") (pin "1") (pinfunction "1_1") (pintype "passive"))
      (node (ref "IC25") (pin "17") (pinfunction "BSP_17") (pintype "input"))
      (node (ref "IC25") (pin "21") (pinfunction "BSP_21") (pintype "input"))
    )
    (net (code "20") (name "/BT-RTS") (class "Default")
      (node (ref "IC1") (pin "83") (pinfunction "PMD14/RD6_83") (pintype "bidirectional"))
      (node (ref "J14") (pin "7") (pinfunction "7_7") (pintype "passive"))
    )
    (net (code "21") (name "/BT-RX") (class "Default")
      (node (ref "IC1") (pin "73") (pinfunction "SOSCI/RPC13/RC13_73") (pintype "bidirectional"))
      (node (ref "J14") (pin "3") (pinfunction "3_3") (pintype "passive"))
    )
    (net (code "22") (name "/BT-TX") (class "Default")
      (node (ref "IC1") (pin "74") (pinfunction "SOSCO/RPC14/T1CK/RC14_74") (pintype "bidirectional"))
      (node (ref "J14") (pin "4") (pinfunction "4_4") (pintype "passive"))
    )
    (net (code "23") (name "/CL_IRQ") (class "Default")
      (node (ref "IC1") (pin "39") (pinfunction "RPF13/RF13_39") (pintype "bidirectional"))
      (node (ref "J5") (pin "4") (pinfunction "4_4") (pintype "passive"))
      (node (ref "O18") (pin "P$1") (pinfunction "TP_P$1") (pintype "passive"))
      (node (ref "T6") (pin "P$1") (pinfunction "TP_P$1") (pintype "passive"))
    )
    (net (code "24") (name "/CON-LED") (class "Default")
      (node (ref "IC1") (pin "78") (pinfunction "AN26/RPD3/RD3_78") (pintype "bidirectional"))
      (node (ref "J14") (pin "6") (pinfunction "6_6") (pintype "passive"))
    )
    (net (code "25") (name "/CURR-ICB") (class "Default")
      (node (ref "C38") (pin "1") (pinfunction "1_1") (pintype "passive"))
      (node (ref "IC1") (pin "23") (pinfunction "PGEC3/AN2/C2INB/RPB2/CTED13/RB2_23") (pintype "bidirectional"))
      (node (ref "R36") (pin "2") (pinfunction "2_2") (pintype "passive"))
    )
    (net (code "26") (name "/CURR-SENSE") (class "Default")
      (node (ref "C66") (pin "1") (pinfunction "1_1") (pintype "passive"))
      (node (ref "IC1") (pin "14") (pinfunction "AN19/C2INC/RPG9/PMA2/RG9_14") (pintype "bidirectional"))
      (node (ref "R102") (pin "2") (pinfunction "2_2") (pintype "passive"))
    )
    (net (code "27") (name "/D+") (class "Default")
      (node (ref "IC1") (pin "57") (pinfunction "D+/RG2_57") (pintype "bidirectional"))
      (node (ref "IC15") (pin "3") (pinfunction "3_3") (pintype "passive"))
      (node (ref "J12") (pin "3_D+") (pinfunction "D+_3_D+") (pintype "bidirectional"))
    )
    (net (code "28") (name "/D-") (class "Default")
      (node (ref "IC1") (pin "56") (pinfunction "D-/RG3_56") (pintype "bidirectional"))
      (node (ref "IC15") (pin "2") (pinfunction "2_2") (pintype "passive"))
      (node (ref "J12") (pin "2_D-") (pinfunction "D-_2_D-") (pintype "bidirectional"))
    )
    (net (code "29") (name "/DEBUG-RXD-A") (class "Default")
      (node (ref "IC26") (pin "3") (pinfunction "3_3") (pintype "passive"))
      (node (ref "J1") (pin "28") (pinfunction "RXD-A_28") (pintype "passive"))
      (node (ref "J18") (pin "2") (pinfunction "2_2") (pintype "passive"))
    )
    (net (code "30") (name "/DEBUG-TXD-A") (class "Default")
      (node (ref "IC26") (pin "2") (pinfunction "2_2") (pintype "passive"))
      (node (ref "J1") (pin "27") (pinfunction "TXD-A_27") (pintype "passive"))
      (node (ref "J18") (pin "3") (pinfunction "3_3") (pintype "passive"))
    )
    (net (code "31") (name "/DIN_SM") (class "Default")
      (node (ref "IC1") (pin "60") (pinfunction "TDI/CTED9/RA4_60") (pintype "bidirectional"))
      (node (ref "IC17") (pin "27") (pinfunction "DIN_27") (pintype "bidirectional"))
      (node (ref "O40") (pin "P$1") (pinfunction "TP_P$1") (pintype "passive"))
      (node (ref "T20") (pin "P$1") (pinfunction "TP_P$1") (pintype "passive"))
    )
    (net (code "32") (name "/DOUT_SM") (class "Default")
      (node (ref "IC1") (pin "79") (pinfunction "RPD12/PMD12/RD12_79") (pintype "bidirectional"))
      (node (ref "IC17") (pin "28") (pinfunction "DOUT_28") (pintype "bidirectional"))
      (node (ref "O27") (pin "P$1") (pinfunction "TP_P$1") (pintype "passive"))
      (node (ref "T19") (pin "P$1") (pinfunction "TP_P$1") (pintype "passive"))
    )
    (net (code "33") (name "/EN-UTRASONIC") (class "Default")
      (node (ref "IC1") (pin "81") (pinfunction "RPD4/PMWR/RD4_81") (pintype "bidirectional"))
      (node (ref "IC27") (pin "2") (pinfunction "2_2") (pintype "passive"))
      (node (ref "J16") (pin "1") (pinfunction "1_1") (pintype "passive"))
      (node (ref "O22") (pin "P$1") (pinfunction "TP_P$1") (pintype "passive"))
      (node (ref "T23") (pin "P$1") (pinfunction "TP_P$1") (pintype "passive"))
    )
    (net (code "34") (name "/GAIN1-AUDIO") (class "Default")
      (node (ref "IC1") (pin "93") (pinfunction "PMD0/RE0_93") (pintype "bidirectional"))
      (node (ref "IC25") (pin "5") (pinfunction "GAIN0_5") (pintype "input"))
      (node (ref "O9") (pin "P$1") (pinfunction "TP_P$1") (pintype "passive"))
      (node (ref "R9") (pin "2") (pinfunction "2_2") (pintype "passive"))
      (node (ref "T46") (pin "P$1") (pinfunction "TP_P$1") (pintype "passive"))
    )
    (net (code "35") (name "/GAIN2-AUDIO") (class "Default")
      (node (ref "IC1") (pin "92") (pinfunction "TRD3/CTED8/RA7_92") (pintype "bidirectional"))
      (node (ref "IC25") (pin "6") (pinfunction "GAIN1_6") (pintype "input"))
      (node (ref "O12") (pin "P$1") (pinfunction "TP_P$1") (pintype "passive"))
      (node (ref "R8") (pin "2") (pinfunction "2_2") (pintype "passive"))
      (node (ref "T35") (pin "P$1") (pinfunction "TP_P$1") (pintype "passive"))
    )
    (net (code "36") (name "/GPIO1") (class "Default")
      (node (ref "IC1") (pin "32") (pinfunction "AN8/RPB8/CTED10/RB8_32") (pintype "bidirectional"))
      (node (ref "O59") (pin "P$1") (pinfunction "TP_P$1") (pintype "passive"))
      (node (ref "R86") (pin "1") (pinfunction "1_1") (pintype "passive"))
      (node (ref "T49") (pin "P$1") (pinfunction "TP_P$1") (pintype "passive"))
    )
    (net (code "37") (name "/GPIO1_") (class "Default")
      (node (ref "J1") (pin "13") (pinfunction "GPIO98_13") (pintype "passive"))
      (node (ref "R112") (pin "2") (pinfunction "2_2") (pintype "passive"))
    )
    (net (code "38") (name "/GPIO2") (class "Default")
      (node (ref "IC1") (pin "33") (pinfunction "AN9/RPB9/CTED4/RB9_33") (pintype "bidirectional"))
      (node (ref "O60") (pin "P$1") (pinfunction "TP_P$1") (pintype "passive"))
      (node (ref "R87") (pin "1") (pinfunction "1_1") (pintype "passive"))
      (node (ref "T50") (pin "P$1") (pinfunction "TP_P$1") (pintype "passive"))
    )
    (net (code "39") (name "/GPIO2_") (class "Default")
      (node (ref "J1") (pin "15") (pinfunction "GPIO103_15") (pintype "passive"))
      (node (ref "R113") (pin "2") (pinfunction "2_2") (pintype "passive"))
    )
    (net (code "40") (name "/I2C-SCL-TOUCH") (class "Default")
      (node (ref "IC29") (pin "2") (pinfunction "SM_CLK_2") (pintype "input"))
      (node (ref "J1") (pin "6") (pinfunction "I2C-SCL_6") (pintype "passive"))
      (node (ref "J6") (pin "2") (pinfunction "2_2") (pintype "passive"))
    )
    (net (code "41") (name "/I2C-SDA-TOUCH") (class "Default")
      (node (ref "IC29") (pin "1") (pinfunction "SM_DAT_1") (pintype "input"))
      (node (ref "J1") (pin "5") (pinfunction "I2C-SDA_5") (pintype "passive"))
      (node (ref "J6") (pin "1") (pinfunction "1_1") (pintype "passive"))
    )
    (net (code "42") (name "/ICB-ON") (class "Default")
      (node (ref "IC1") (pin "91") (pinfunction "TRCLK/RA6_91") (pintype "bidirectional"))
      (node (ref "O13") (pin "P$1") (pinfunction "TP_P$1") (pintype "passive"))
      (node (ref "Q6") (pin "2") (pinfunction "G_2") (pintype "passive"))
      (node (ref "R10") (pin "1") (pinfunction "1_1") (pintype "passive"))
      (node (ref "R16") (pin "2") (pinfunction "2_2") (pintype "passive"))
      (node (ref "T2") (pin "P$1") (pinfunction "TP_P$1") (pintype "passive"))
    )
    (net (code "43") (name "/ILLUMINATE1") (class "Default")
      (node (ref "IC1") (pin "99") (pinfunction "RPE3/PMD3/RE3_99") (pintype "bidirectional"))
      (node (ref "O8") (pin "P$1") (pinfunction "TP_P$1") (pintype "passive"))
      (node (ref "R116") (pin "1") (pinfunction "1_1") (pintype "passive"))
      (node (ref "T29") (pin "P$1") (pinfunction "TP_P$1") (pintype "passive"))
    )
    (net (code "44") (name "/ILLUMINATE2") (class "Default")
      (node (ref "IC1") (pin "3") (pinfunction "AN22/RPE5/PMD5/RE5_3") (pintype "bidirectional"))
      (node (ref "O1") (pin "P$1") (pinfunction "TP_P$1") (pintype "passive"))
      (node (ref "R119") (pin "1") (pinfunction "1_1") (pintype "passive"))
      (node (ref "T30") (pin "P$1") (pinfunction "TP_P$1") (pintype "passive"))
    )
    (net (code "45") (name "/LAN-CTL") (class "Default")
      (node (ref "IC12") (pin "2") (pinfunction "/RE_2") (pintype "input"))
      (node (ref "IC12") (pin "3") (pinfunction "DE_3") (pintype "input"))
      (node (ref "IC21") (pin "4") (pinfunction "Y_4") (pintype "output"))
    )
    (net (code "46") (name "/LAN-CTL-ICB") (class "Default")
      (node (ref "IC21") (pin "1") (pinfunction "A_1") (pintype "input"))
      (node (ref "J1") (pin "16") (pinfunction "GPIO101_16") (pintype "passive"))
      (node (ref "R57") (pin "2") (pinfunction "2_2") (pintype "passive"))
    )
    (net (code "47") (name "/LAN-CTL-PIC") (class "Default")
      (node (ref "IC1") (pin "84") (pinfunction "PMD15/RD7_84") (pintype "bidirectional"))
      (node (ref "IC21") (pin "2") (pinfunction "B_2") (pintype "input"))
      (node (ref "R56") (pin "2") (pinfunction "2_2") (pintype "passive"))
    )
    (net (code "48") (name "/LAN-RX") (class "Default")
      (node (ref "IC1") (pin "88") (pinfunction "RPF1/PMD10/RF1_88") (pintype "bidirectional"))
      (node (ref "IC12") (pin "1") (pinfunction "R_1") (pintype "output"))
      (node (ref "IC19") (pin "2") (pinfunction "B_2") (pintype "input"))
      (node (ref "R72") (pin "2") (pinfunction "2_2") (pintype "passive"))
    )
    (net (code "49") (name "/LAN-RX-ICB") (class "Default")
      (node (ref "IC19") (pin "4") (pinfunction "Y_4") (pintype "output"))
      (node (ref "J1") (pin "31") (pinfunction "RXD-B_31") (pintype "passive"))
    )
    (net (code "50") (name "/LAN-TX") (class "Default")
      (node (ref "IC12") (pin "4") (pinfunction "D_4") (pintype "input"))
      (node (ref "IC2") (pin "4") (pinfunction "Y_4") (pintype "output"))
    )
    (net (code "51") (name "/LAN-TX-ICB") (class "Default")
      (node (ref "J1") (pin "32") (pinfunction "TXD-B_32") (pintype "passive"))
      (node (ref "R122") (pin "1") (pinfunction "1_1") (pintype "passive"))
      (node (ref "R54") (pin "1") (pinfunction "1_1") (pintype "passive"))
    )
    (net (code "52") (name "/LAN-TX-PIC") (class "Default")
      (node (ref "IC1") (pin "87") (pinfunction "RPF0/PMD11/RF0_87") (pintype "bidirectional"))
      (node (ref "IC2") (pin "1") (pinfunction "A_1") (pintype "input"))
      (node (ref "R55") (pin "2") (pinfunction "2_2") (pintype "passive"))
    )
    (net (code "53") (name "/LED-PIC") (class "Default")
      (node (ref "IC1") (pin "1") (pinfunction "RG15_1") (pintype "bidirectional"))
      (node (ref "R29") (pin "1") (pinfunction "1_1") (pintype "passive"))
      (node (ref "TP4") (pin "P$1") (pinfunction "TP_P$1") (pintype "passive"))
    )
    (net (code "54") (name "/OUTN") (class "Default")
      (node (ref "C14") (pin "1") (pinfunction "1_1") (pintype "passive"))
      (node (ref "IC25") (pin "23") (pinfunction "OUTN_23") (pintype "input"))
      (node (ref "IC25") (pin "25") (pinfunction "OUTN_25") (pintype "input"))
      (node (ref "L16") (pin "2") (pinfunction "2_2") (pintype "passive"))
    )
    (net (code "55") (name "/OUTP") (class "Default")
      (node (ref "C13") (pin "2") (pinfunction "2_2") (pintype "passive"))
      (node (ref "IC25") (pin "18") (pinfunction "OUTP_18") (pintype "input"))
      (node (ref "IC25") (pin "20") (pinfunction "OUTP_20") (pintype "input"))
      (node (ref "L15") (pin "2") (pinfunction "2_2") (pintype "passive"))
    )
    (net (code "56") (name "/PGC") (class "Default")
      (node (ref "IC1") (pin "24") (pinfunction "PGEC1/AN1/RPB1/CTED12/RB1_24") (pintype "bidirectional"))
      (node (ref "J17") (pin "5") (pinfunction "5_5") (pintype "passive"))
    )
    (net (code "57") (name "/PGC2-{slash}BTN2") (class "Default")
      (node (ref "IC3") (pin "3") (pinfunction "GP1/PGC_3") (pintype "bidirectional"))
      (node (ref "J10") (pin "5") (pinfunction "5_5") (pintype "passive"))
      (node (ref "R71") (pin "1") (pinfunction "1_1") (pintype "passive"))
    )
    (net (code "58") (name "/PGD") (class "Default")
      (node (ref "IC1") (pin "25") (pinfunction "PGED1/AN0/RPB0/RB0_25") (pintype "bidirectional"))
      (node (ref "J17") (pin "4") (pinfunction "4_4") (pintype "passive"))
    )
    (net (code "59") (name "/PGD2-{slash}BTN1") (class "Default")
      (node (ref "IC3") (pin "1") (pinfunction "GP0/PGD_1") (pintype "bidirectional"))
      (node (ref "J10") (pin "4") (pinfunction "4_4") (pintype "passive"))
      (node (ref "R120") (pin "1") (pinfunction "1_1") (pintype "passive"))
    )
    (net (code "60") (name "/PIC-RXD") (class "Default")
      (node (ref "IC1") (pin "6") (pinfunction "RPC1/RC1_6") (pintype "bidirectional"))
      (node (ref "O2") (pin "P$1") (pinfunction "TP_P$1") (pintype "passive"))
      (node (ref "R124") (pin "1") (pinfunction "1_1") (pintype "passive"))
      (node (ref "T26") (pin "P$1") (pinfunction "TP_P$1") (pintype "passive"))
    )
    (net (code "61") (name "/PIC-TX") (class "Default")
      (node (ref "IC1") (pin "9") (pinfunction "RPC4/CTED7/RC4_9") (pintype "bidirectional"))
      (node (ref "O5") (pin "P$1") (pinfunction "TP_P$1") (pintype "passive"))
      (node (ref "R123") (pin "2") (pinfunction "2_2") (pintype "passive"))
      (node (ref "T28") (pin "P$1") (pinfunction "TP_P$1") (pintype "passive"))
    )
    (net (code "62") (name "/POWER-GOOD") (class "Default")
      (node (ref "IC1") (pin "89") (pinfunction "RPG1/PMD9/RG1_89") (pintype "bidirectional"))
      (node (ref "IC6") (pin "4") (pinfunction "OUT_4") (pintype "output"))
      (node (ref "O15") (pin "P$1") (pinfunction "TP_P$1") (pintype "passive"))
      (node (ref "T45") (pin "P$1") (pinfunction "TP_P$1") (pintype "passive"))
    )
    (net (code "63") (name "/REF-EN") (class "Default")
      (node (ref "IC1") (pin "28") (pinfunction "VREF-/CVREF-/PMA7/RA9_28") (pintype "bidirectional"))
      (node (ref "R93") (pin "1") (pinfunction "1_1") (pintype "passive"))
    )
    (net (code "64") (name "/REF2,5V") (class "Default")
      (node (ref "C57") (pin "1") (pinfunction "1_1") (pintype "passive"))
      (node (ref "IC1") (pin "29") (pinfunction "VREF+/CVREF+/PMA6/RA10_29") (pintype "bidirectional"))
      (node (ref "IC13") (pin "2") (pinfunction "VOUT_2") (pintype "bidirectional"))
    )
    (net (code "65") (name "/RESET-ICB") (class "Default")
      (node (ref "IC1") (pin "18") (pinfunction "RPE8/RE8_18") (pintype "bidirectional"))
      (node (ref "O10") (pin "P$1") (pinfunction "TP_P$1") (pintype "passive"))
      (node (ref "Q9") (pin "2") (pinfunction "G_2") (pintype "passive"))
      (node (ref "R85") (pin "2") (pinfunction "2_2") (pintype "passive"))
      (node (ref "T61") (pin "P$1") (pinfunction "TP_P$1") (pintype "passive"))
    )
    (net (code "66") (name "/SCL1-EEPROM") (class "Default")
      (node (ref "IC1") (pin "66") (pinfunction "SCL1/RPA14/RA14_66") (pintype "bidirectional"))
      (node (ref "IC11") (pin "6") (pinfunction "SCL_6") (pintype "input"))
      (node (ref "IC24") (pin "2") (pinfunction "SCL_2") (pintype "input"))
      (node (ref "IC7") (pin "6") (pinfunction "SCL_6") (pintype "input"))
      (node (ref "R26") (pin "2") (pinfunction "2_2") (pintype "passive"))
    )
    (net (code "67") (name "/SCL2") (class "Default")
      (node (ref "IC1") (pin "58") (pinfunction "SCL2/RA2_58") (pintype "bidirectional"))
      (node (ref "IC28") (pin "2") (pinfunction "2_2") (pintype "passive"))
      (node (ref "J22") (pin "1") (pinfunction "1_1") (pintype "passive"))
      (node (ref "O28") (pin "P$1") (pinfunction "TP_P$1") (pintype "passive"))
      (node (ref "R130") (pin "2") (pinfunction "2_2") (pintype "passive"))
      (node (ref "T5") (pin "P$1") (pinfunction "TP_P$1") (pintype "passive"))
    )
    (net (code "68") (name "/SCLK1") (class "Default")
      (node (ref "IC1") (pin "70") (pinfunction "RPD10/SCK1/PMCS2/RD10_70") (pintype "bidirectional"))
      (node (ref "J5") (pin "5") (pinfunction "5_5") (pintype "passive"))
    )
    (net (code "69") (name "/SCLK2-SPI") (class "Default")
      (node (ref "IC1") (pin "10") (pinfunction "AN16/C1IND/RPG6/SCK2/PMA5/RG6_10") (pintype "bidirectional"))
      (node (ref "IC9") (pin "6") (pinfunction "C_6") (pintype "input"))
    )
    (net (code "70") (name "/SCLK_SM") (class "Default")
      (node (ref "IC1") (pin "76") (pinfunction "AN24/RPD1/RD1_76") (pintype "bidirectional"))
      (node (ref "IC17") (pin "26") (pinfunction "SCLK_26") (pintype "bidirectional"))
      (node (ref "O35") (pin "P$1") (pinfunction "TP_P$1") (pintype "passive"))
      (node (ref "T18") (pin "P$1") (pinfunction "TP_P$1") (pintype "passive"))
    )
    (net (code "71") (name "/SDA1-EEPROM") (class "Default")
      (node (ref "IC1") (pin "67") (pinfunction "SDA1/RPA15/RA15_67") (pintype "bidirectional"))
      (node (ref "IC11") (pin "5") (pinfunction "SDA_5") (pintype "bidirectional"))
      (node (ref "IC24") (pin "1") (pinfunction "SDA_1") (pintype "bidirectional"))
      (node (ref "IC7") (pin "5") (pinfunction "SDA_5") (pintype "bidirectional"))
      (node (ref "R27") (pin "2") (pinfunction "2_2") (pintype "passive"))
    )
    (net (code "72") (name "/SDA2") (class "Default")
      (node (ref "IC1") (pin "59") (pinfunction "SDA2/RA3_59") (pintype "bidirectional"))
      (node (ref "IC28") (pin "3") (pinfunction "3_3") (pintype "passive"))
      (node (ref "J22") (pin "2") (pinfunction "2_2") (pintype "passive"))
      (node (ref "O19") (pin "P$1") (pinfunction "TP_P$1") (pintype "passive"))
      (node (ref "R131") (pin "2") (pinfunction "2_2") (pintype "passive"))
      (node (ref "T1") (pin "P$1") (pinfunction "TP_P$1") (pintype "passive"))
    )
    (net (code "73") (name "/SDI1") (class "Default")
      (node (ref "IC1") (pin "50") (pinfunction "RPF5/PMA8/RF5_50") (pintype "bidirectional"))
      (node (ref "J5") (pin "8") (pinfunction "8_8") (pintype "passive"))
      (node (ref "O21") (pin "P$1") (pinfunction "TP_P$1") (pintype "passive"))
      (node (ref "T9") (pin "P$1") (pinfunction "TP_P$1") (pintype "passive"))
    )
    (net (code "74") (name "/SDI2-MISO") (class "Default")
      (node (ref "IC1") (pin "22") (pinfunction "PGED3/AN3/C2INA/RPB3/RB3_22") (pintype "bidirectional"))
      (node (ref "IC9") (pin "2") (pinfunction "Q_2") (pintype "bidirectional"))
    )
    (net (code "75") (name "/SDO1") (class "Default")
      (node (ref "IC1") (pin "48") (pinfunction "RPD15/RD15_48") (pintype "bidirectional"))
      (node (ref "J5") (pin "6") (pinfunction "6_6") (pintype "passive"))
      (node (ref "O58") (pin "P$1") (pinfunction "TP_P$1") (pintype "passive"))
      (node (ref "T8") (pin "P$1") (pinfunction "TP_P$1") (pintype "passive"))
    )
    (net (code "76") (name "/SDO2-MOSI") (class "Default")
      (node (ref "IC1") (pin "20") (pinfunction "AN5/C1INA/RPB5/RB5_20") (pintype "bidirectional"))
      (node (ref "IC9") (pin "5") (pinfunction "D_5") (pintype "input"))
    )
    (net (code "77") (name "/SIM-CLK") (class "Default")
      (node (ref "IC17") (pin "18") (pinfunction "CLKB_18") (pintype "bidirectional"))
      (node (ref "J2") (pin "C3") (pinfunction "CLK/C3_C3") (pintype "bidirectional"))
    )
    (net (code "78") (name "/SIM-IO") (class "Default")
      (node (ref "IC17") (pin "20") (pinfunction "IOB_20") (pintype "bidirectional"))
      (node (ref "J2") (pin "C7") (pinfunction "C7/DATA_C7") (pintype "bidirectional"))
    )
    (net (code "79") (name "/SIM-RST") (class "Default")
      (node (ref "IC17") (pin "19") (pinfunction "RSTB_19") (pintype "bidirectional"))
      (node (ref "J2") (pin "C2") (pinfunction "RST/C2_C2") (pintype "input"))
    )
    (net (code "80") (name "/SIM-VCC") (class "Default")
      (node (ref "IC17") (pin "17") (pinfunction "VCCB_17") (pintype "bidirectional"))
      (node (ref "J2") (pin "C1") (pinfunction "VCC/C1_C1") (pintype "input"))
    )
    (net (code "81") (name "/SM_ASYNC") (class "Default")
      (node (ref "IC1") (pin "49") (pinfunction "RPF4/PMA9/RF4_49") (pintype "bidirectional"))
      (node (ref "IC17") (pin "31") (pinfunction "ASYNC_31") (pintype "bidirectional"))
      (node (ref "O20") (pin "P$1") (pinfunction "TP_P$1") (pintype "passive"))
      (node (ref "T57") (pin "P$1") (pinfunction "TP_P$1") (pintype "passive"))
    )
    (net (code "82") (name "/SM_C4A") (class "Default")
      (node (ref "IC17") (pin "4") (pinfunction "C4A_4") (pintype "bidirectional"))
      (node (ref "J15") (pin "2") (pinfunction "2_2") (pintype "passive"))
      (node (ref "J21") (pin "2") (pinfunction "2_2") (pintype "passive"))
      (node (ref "J9") (pin "2") (pinfunction "1_2") (pintype "passive"))
    )
    (net (code "83") (name "/SM_C8A") (class "Default")
      (node (ref "IC17") (pin "3") (pinfunction "C8A_3") (pintype "bidirectional"))
      (node (ref "J15") (pin "1") (pinfunction "1_1") (pintype "passive"))
      (node (ref "J21") (pin "1") (pinfunction "1_1") (pintype "passive"))
      (node (ref "J9") (pin "1") (pinfunction "1_1") (pintype "passive"))
    )
    (net (code "84") (name "/SM_CLK_A") (class "Default")
      (node (ref "IC17") (pin "7") (pinfunction "CLKA_7") (pintype "bidirectional"))
      (node (ref "J15") (pin "4") (pinfunction "4_4") (pintype "passive"))
      (node (ref "J21") (pin "4") (pinfunction "4_4") (pintype "passive"))
      (node (ref "J9") (pin "4") (pinfunction "1_4") (pintype "passive"))
    )
    (net (code "85") (name "/SM_DATA") (class "Default")
      (node (ref "IC1") (pin "68") (pinfunction "RPD8/RTCC/RD8_68") (pintype "bidirectional"))
      (node (ref "IC1") (pin "69") (pinfunction "RPD9/RD9_69") (pintype "bidirectional"))
      (node (ref "IC17") (pin "29") (pinfunction "DATA_29") (pintype "bidirectional"))
      (node (ref "O25") (pin "P$1") (pinfunction "TP_P$1") (pintype "passive"))
      (node (ref "O26") (pin "P$1") (pinfunction "TP_P$1") (pintype "passive"))
      (node (ref "T12") (pin "P$1") (pinfunction "TP_P$1") (pintype "passive"))
      (node (ref "T16") (pin "P$1") (pinfunction "TP_P$1") (pintype "passive"))
    )
    (net (code "86") (name "/SM_DET_A") (class "Default")
      (node (ref "IC17") (pin "2") (pinfunction "PRESA_2") (pintype "bidirectional"))
      (node (ref "J15") (pin "10") (pinfunction "10_10") (pintype "passive"))
      (node (ref "J21") (pin "10") (pinfunction "10_10") (pintype "passive"))
      (node (ref "J9") (pin "10") (pinfunction "1_10") (pintype "passive"))
    )
    (net (code "87") (name "/SM_IO_A") (class "Default")
      (node (ref "IC17") (pin "5") (pinfunction "IOA_5") (pintype "bidirectional"))
      (node (ref "J15") (pin "3") (pinfunction "3_3") (pintype "passive"))
      (node (ref "J21") (pin "3") (pinfunction "3_3") (pintype "passive"))
      (node (ref "J9") (pin "3") (pinfunction "1_3") (pintype "passive"))
    )
    (net (code "88") (name "/SM_RST") (class "Default")
      (node (ref "IC1") (pin "42") (pinfunction "AN13/RB13_42") (pintype "bidirectional"))
      (node (ref "IC17") (pin "30") (pinfunction "RIN_30") (pintype "bidirectional"))
      (node (ref "O55") (pin "P$1") (pinfunction "TP_P$1") (pintype "passive"))
      (node (ref "T11") (pin "P$1") (pinfunction "TP_P$1") (pintype "passive"))
    )
    (net (code "89") (name "/SM_RST_A") (class "Default")
      (node (ref "IC17") (pin "6") (pinfunction "RSTA_6") (pintype "bidirectional"))
      (node (ref "J15") (pin "6") (pinfunction "6_6") (pintype "passive"))
      (node (ref "J21") (pin "6") (pinfunction "6_6") (pintype "passive"))
      (node (ref "J9") (pin "6") (pinfunction "1_6") (pintype "passive"))
    )
    (net (code "90") (name "/SM_SYNC") (class "Default")
      (node (ref "IC1") (pin "43") (pinfunction "AN14/RPB14/PMA1/CTED5/RB14_43") (pintype "bidirectional"))
      (node (ref "IC17") (pin "32") (pinfunction "SYNC_32") (pintype "bidirectional"))
      (node (ref "O53") (pin "P$1") (pinfunction "TP_P$1") (pintype "passive"))
      (node (ref "T10") (pin "P$1") (pinfunction "TP_P$1") (pintype "passive"))
    )
    (net (code "91") (name "/SM_VCC_A") (class "Default")
      (node (ref "IC17") (pin "8") (pinfunction "VCCA_8") (pintype "bidirectional"))
      (node (ref "J15") (pin "9") (pinfunction "9_9") (pintype "passive"))
      (node (ref "J21") (pin "9") (pinfunction "9_9") (pintype "passive"))
      (node (ref "J9") (pin "9") (pinfunction "1_9") (pintype "passive"))
    )
    (net (code "92") (name "/SPKRN") (class "Default")
      (node (ref "C16") (pin "1") (pinfunction "1_1") (pintype "passive"))
      (node (ref "J11") (pin "2") (pinfunction "2_2") (pintype "passive"))
      (node (ref "L16") (pin "1") (pinfunction "1_1") (pintype "passive"))
    )
    (net (code "93") (name "/SPKRP") (class "Default")
      (node (ref "C15") (pin "1") (pinfunction "1_1") (pintype "passive"))
      (node (ref "J11") (pin "1") (pinfunction "1_1") (pintype "passive"))
      (node (ref "L15") (pin "1") (pinfunction "1_1") (pintype "passive"))
    )
    (net (code "94") (name "/TXD-ULTRASONIC") (class "Default")
      (node (ref "IC1") (pin "7") (pinfunction "RPC2/RC2_7") (pintype "bidirectional"))
      (node (ref "IC27") (pin "3") (pinfunction "3_3") (pintype "passive"))
      (node (ref "J16") (pin "2") (pinfunction "2_2") (pintype "passive"))
      (node (ref "O23") (pin "P$1") (pinfunction "TP_P$1") (pintype "passive"))
      (node (ref "T3") (pin "P$1") (pinfunction "TP_P$1") (pintype "passive"))
    )
    (net (code "95") (name "/VBAT-LAN") (class "Default")
      (node (ref "D3") (pin "C") (pinfunction "C_C") (pintype "passive"))
      (node (ref "J3") (pin "1") (pinfunction "1_1") (pintype "passive"))
      (node (ref "J3") (pin "3") (pinfunction "3_3") (pintype "passive"))
      (node (ref "J4") (pin "1") (pinfunction "1_1") (pintype "passive"))
      (node (ref "J4") (pin "3") (pinfunction "3_3") (pintype "passive"))
      (node (ref "L11") (pin "2") (pinfunction "2_2") (pintype "passive"))
    )
    (net (code "96") (name "/VBAT-LAN-F") (class "Default")
      (node (ref "C34") (pin "1") (pinfunction "1_1") (pintype "passive"))
      (node (ref "D6") (pin "K") (pinfunction "K_K") (pintype "passive"))
      (node (ref "L11") (pin "1") (pinfunction "1_1") (pintype "passive"))
      (node (ref "Q3") (pin "1") (pinfunction "D_1") (pintype "passive"))
      (node (ref "Q3") (pin "2") (pinfunction "D_2") (pintype "passive"))
      (node (ref "Q3") (pin "5") (pinfunction "D_5") (pintype "passive"))
      (node (ref "Q3") (pin "6") (pinfunction "D_6") (pintype "passive"))
      (node (ref "Q5") (pin "4") (pinfunction "S_4") (pintype "passive"))
      (node (ref "R45") (pin "1") (pinfunction "1_1") (pintype "passive"))
      (node (ref "R94") (pin "1") (pinfunction "1_1") (pintype "passive"))
    )
    (net (code "97") (name "/VBAT-SENSE") (class "Default")
      (node (ref "C64") (pin "1") (pinfunction "1_1") (pintype "passive"))
      (node (ref "IC1") (pin "26") (pinfunction "PGEC2/AN6/RPB6/RB6_26") (pintype "bidirectional"))
      (node (ref "R100") (pin "1") (pinfunction "1_1") (pintype "passive"))
    )
    (net (code "98") (name "/VBAT-TO-LAN") (class "Default")
      (node (ref "IC1") (pin "52") (pinfunction "RPF2/RF2_52") (pintype "bidirectional"))
      (node (ref "Q4") (pin "2") (pinfunction "G_2") (pintype "passive"))
      (node (ref "R41") (pin "1") (pinfunction "1_1") (pintype "passive"))
      (node (ref "R59") (pin "1") (pinfunction "1_1") (pintype "passive"))
    )
    (net (code "99") (name "/VBAT-TO-LAN-ICB") (class "Default")
      (node (ref "J1") (pin "18") (pinfunction "GPIO85_18") (pintype "passive"))
      (node (ref "R59") (pin "2") (pinfunction "2_2") (pintype "passive"))
    )
    (net (code "100") (name "/VBATLAN-SENSE") (class "Default")
      (node (ref "C36") (pin "1") (pinfunction "1_1") (pintype "passive"))
      (node (ref "IC1") (pin "27") (pinfunction "PGED2/AN7/RPB7/CTED3/RB7_27") (pintype "bidirectional"))
      (node (ref "R101") (pin "1") (pinfunction "1_1") (pintype "passive"))
    )
    (net (code "101") (name "/VBUS") (class "Default")
      (node (ref "IC1") (pin "54") (pinfunction "VBUS_54") (pintype "input"))
      (node (ref "R128") (pin "2") (pinfunction "2_2") (pintype "passive"))
    )
    (net (code "102") (name "/VCAP-SENSE") (class "Default")
      (node (ref "C76") (pin "1") (pinfunction "1_1") (pintype "passive"))
      (node (ref "IC1") (pin "77") (pinfunction "AN25/RPD2/RD2_77") (pintype "bidirectional"))
      (node (ref "R118") (pin "1") (pinfunction "1_1") (pintype "passive"))
    )
    (net (code "103") (name "/VCC-AUDIO") (class "Default")
      (node (ref "C1") (pin "1") (pinfunction "1_1") (pintype "passive"))
      (node (ref "C10") (pin "1") (pinfunction "1_1") (pintype "passive"))
      (node (ref "C17") (pin "1") (pinfunction "1_1") (pintype "passive"))
      (node (ref "C18") (pin "1") (pinfunction "1_1") (pintype "passive"))
      (node (ref "C7") (pin "1") (pinfunction "1_1") (pintype "passive"))
      (node (ref "C72") (pin "1") (pinfunction "1_1") (pintype "passive"))
      (node (ref "C8") (pin "1") (pinfunction "1_1") (pintype "passive"))
      (node (ref "C9") (pin "1") (pinfunction "1_1") (pintype "passive"))
      (node (ref "IC25") (pin "15") (pinfunction "PVCC_15") (pintype "input"))
      (node (ref "IC25") (pin "16") (pinfunction "PVCC_16") (pintype "input"))
      (node (ref "IC25") (pin "27") (pinfunction "PVCC_27") (pintype "input"))
      (node (ref "IC25") (pin "28") (pinfunction "PVCC_28") (pintype "input"))
      (node (ref "L1") (pin "1") (pinfunction "1_1") (pintype "passive"))
      (node (ref "R4") (pin "1") (pinfunction "1_1") (pintype "passive"))
    )
    (net (code "104") (name "/VPS-ON") (class "Default")
      (node (ref "IC1") (pin "53") (pinfunction "RPF8/RF8_53") (pintype "bidirectional"))
      (node (ref "Q4") (pin "5") (pinfunction "G_5") (pintype "passive"))
      (node (ref "R44") (pin "1") (pinfunction "1_1") (pintype "passive"))
      (node (ref "R58") (pin "1") (pinfunction "1_1") (pintype "passive"))
    )
    (net (code "105") (name "/VPS-ON-ICB") (class "Default")
      (node (ref "J1") (pin "20") (pinfunction "GPIO45_20") (pintype "passive"))
      (node (ref "R58") (pin "2") (pinfunction "2_2") (pintype "passive"))
    )
    (net (code "106") (name "/VPS-PWR") (class "Default")
      (node (ref "D4") (pin "C") (pinfunction "C_C") (pintype "passive"))
      (node (ref "J3") (pin "6") (pinfunction "6_6") (pintype "passive"))
      (node (ref "J4") (pin "6") (pinfunction "6_6") (pintype "passive"))
      (node (ref "L10") (pin "2") (pinfunction "2_2") (pintype "passive"))
    )
    (net (code "107") (name "/VPS-PWR-F") (class "Default")
      (node (ref "L10") (pin "1") (pinfunction "1_1") (pintype "passive"))
      (node (ref "Q5") (pin "1") (pinfunction "D_1") (pintype "passive"))
      (node (ref "Q5") (pin "2") (pinfunction "D_2") (pintype "passive"))
      (node (ref "Q5") (pin "5") (pinfunction "D_5") (pintype "passive"))
      (node (ref "Q5") (pin "6") (pinfunction "D_6") (pintype "passive"))
      (node (ref "R23") (pin "2") (pinfunction "2_2") (pintype "passive"))
    )
    (net (code "108") (name "/VPS-SENSE") (class "Default")
      (node (ref "C65") (pin "1") (pinfunction "1_1") (pintype "passive"))
      (node (ref "IC1") (pin "12") (pinfunction "AN18/C2IND/RPG8/PMA3/RG8_12") (pintype "bidirectional"))
      (node (ref "IC20") (pin "2") (pinfunction "B_2") (pintype "input"))
      (node (ref "R48") (pin "2") (pinfunction "2_2") (pintype "passive"))
      (node (ref "R49") (pin "1") (pinfunction "1_1") (pintype "passive"))
    )
    (net (code "109") (name "/VPS-SENSE-ICB") (class "Default")
      (node (ref "IC20") (pin "4") (pinfunction "Y_4") (pintype "output"))
      (node (ref "J1") (pin "19") (pinfunction "GPIO79_19") (pintype "passive"))
    )
    (net (code "110") (name "/WAKE-SW") (class "Default")
      (node (ref "IC1") (pin "72") (pinfunction "RPD0/INT0/RD0_72") (pintype "bidirectional"))
      (node (ref "J14") (pin "5") (pinfunction "5_5") (pintype "passive"))
    )
    (net (code "111") (name "/{slash}3.3V1PWRON") (class "Default")
      (node (ref "IC1") (pin "21") (pinfunction "AN4/C1INB/USBOEN/RB4_21") (pintype "bidirectional"))
      (node (ref "R24") (pin "2") (pinfunction "2_2") (pintype "passive"))
    )
    (net (code "112") (name "/{slash}3.3V2PWRON") (class "Default")
      (node (ref "IC1") (pin "96") (pinfunction "TRD1/RG12_96") (pintype "bidirectional"))
      (node (ref "R60") (pin "2") (pinfunction "2_2") (pintype "passive"))
      (node (ref "R75") (pin "2") (pinfunction "2_2") (pintype "passive"))
    )
    (net (code "113") (name "/{slash}BTN1") (class "Default")
      (node (ref "IC1") (pin "5") (pinfunction "AN27/PMD7/RE7_5") (pintype "bidirectional"))
      (node (ref "IC22") (pin "4") (pinfunction "OUT_4") (pintype "output"))
      (node (ref "O6") (pin "P$1") (pinfunction "TP_P$1") (pintype "passive"))
      (node (ref "R120") (pin "2") (pinfunction "2_2") (pintype "passive"))
      (node (ref "T31") (pin "P$1") (pinfunction "TP_P$1") (pintype "passive"))
    )
    (net (code "114") (name "/{slash}BTN2") (class "Default")
      (node (ref "IC1") (pin "4") (pinfunction "AN23/PMD6/RE6_4") (pintype "bidirectional"))
      (node (ref "IC23") (pin "4") (pinfunction "OUT_4") (pintype "output"))
      (node (ref "O7") (pin "P$1") (pinfunction "TP_P$1") (pintype "passive"))
      (node (ref "R71") (pin "2") (pinfunction "2_2") (pintype "passive"))
      (node (ref "T34") (pin "P$1") (pinfunction "TP_P$1") (pintype "passive"))
    )
    (net (code "115") (name "/{slash}CL_CS") (class "Default")
      (node (ref "IC1") (pin "38") (pinfunction "TCK/CTED2/RA1_38") (pintype "bidirectional"))
      (node (ref "J5") (pin "7") (pinfunction "7_7") (pintype "passive"))
      (node (ref "O17") (pin "P$1") (pinfunction "TP_P$1") (pintype "passive"))
      (node (ref "T4") (pin "P$1") (pinfunction "TP_P$1") (pintype "passive"))
    )
    (net (code "116") (name "/{slash}FAULT-AUDIO") (class "Default")
      (node (ref "IC1") (pin "95") (pinfunction "TRD2/RG14_95") (pintype "bidirectional"))
      (node (ref "O3") (pin "P$1") (pinfunction "TP_P$1") (pintype "passive"))
      (node (ref "R7") (pin "1") (pinfunction "1_1") (pintype "passive"))
      (node (ref "T48") (pin "P$1") (pinfunction "TP_P$1") (pintype "passive"))
    )
    (net (code "117") (name "/{slash}FMEM1-CS") (class "Default")
      (node (ref "IC1") (pin "11") (pinfunction "AN17/C1INC/RPG7/PMA4/RG7_11") (pintype "bidirectional"))
      (node (ref "IC9") (pin "1") (pinfunction "/S_1") (pintype "input"))
      (node (ref "R25") (pin "1") (pinfunction "1_1") (pintype "passive"))
    )
    (net (code "118") (name "/{slash}I2C_PWRON") (class "Default")
      (node (ref "IC1") (pin "97") (pinfunction "TRD0/RG13_97") (pintype "bidirectional"))
      (node (ref "O29") (pin "P$1") (pinfunction "TP_P$1") (pintype "passive"))
      (node (ref "R125") (pin "2") (pinfunction "2_2") (pintype "passive"))
      (node (ref "T7") (pin "P$1") (pinfunction "TP_P$1") (pintype "passive"))
    )
    (net (code "119") (name "/{slash}INT-TOUCH") (class "Default")
      (node (ref "J1") (pin "38") (pinfunction "PWM_B_38") (pintype "passive"))
      (node (ref "J6") (pin "4") (pinfunction "4_4") (pintype "passive"))
    )
    (net (code "120") (name "/{slash}LD_SM") (class "Default")
      (node (ref "IC1") (pin "61") (pinfunction "TDO/RA5_61") (pintype "bidirectional"))
      (node (ref "IC17") (pin "25") (pinfunction "/LD_25") (pintype "bidirectional"))
      (node (ref "O39") (pin "P$1") (pinfunction "TP_P$1") (pintype "passive"))
      (node (ref "T17") (pin "P$1") (pinfunction "TP_P$1") (pintype "passive"))
    )
    (net (code "121") (name "/{slash}MCLR") (class "Default")
      (node (ref "IC1") (pin "13") (pinfunction "~{MCLR}_13") (pintype "input"))
      (node (ref "J17") (pin "1") (pinfunction "1_1") (pintype "passive"))
      (node (ref "R61") (pin "2") (pinfunction "2_2") (pintype "passive"))
      (node (ref "R90") (pin "2") (pinfunction "2_2") (pintype "passive"))
    )
    (net (code "122") (name "/{slash}MCLR2") (class "Default")
      (node (ref "IC3") (pin "6") (pinfunction "GP3/MCLR_6") (pintype "bidirectional"))
      (node (ref "J10") (pin "1") (pinfunction "1_1") (pintype "passive"))
    )
    (net (code "123") (name "/{slash}RESET-ICB-OUT") (class "Default")
      (node (ref "IC1") (pin "19") (pinfunction "RPE9/RE9_19") (pintype "bidirectional"))
      (node (ref "J1") (pin "4") (pinfunction "/RST-OUT_4") (pintype "passive"))
      (node (ref "O11") (pin "P$1") (pinfunction "TP_P$1") (pintype "passive"))
      (node (ref "T62") (pin "P$1") (pinfunction "TP_P$1") (pintype "passive"))
    )
    (net (code "124") (name "/{slash}RESET-TOUCH") (class "Default")
      (node (ref "J1") (pin "39") (pinfunction "PWM_C_39") (pintype "passive"))
      (node (ref "J6") (pin "5") (pinfunction "5_5") (pintype "passive"))
    )
    (net (code "125") (name "/{slash}RST-IN") (class "Default")
      (node (ref "IC29") (pin "16") (pinfunction "/LRESET_16") (pintype "input"))
      (node (ref "J1") (pin "1") (pinfunction "/RST-IN_1") (pintype "passive"))
      (node (ref "Q9") (pin "6") (pinfunction "D_6") (pintype "passive"))
      (node (ref "R53") (pin "1") (pinfunction "1_1") (pintype "passive"))
    )
    (net (code "126") (name "/{slash}SD-AUDIO") (class "Default")
      (node (ref "IC1") (pin "94") (pinfunction "PMD1/RE1_94") (pintype "bidirectional"))
      (node (ref "O4") (pin "P$1") (pinfunction "TP_P$1") (pintype "passive"))
      (node (ref "R6") (pin "1") (pinfunction "1_1") (pintype "passive"))
      (node (ref "R84") (pin "2") (pinfunction "2_2") (pintype "passive"))
      (node (ref "T47") (pin "P$1") (pinfunction "TP_P$1") (pintype "passive"))
    )
    (net (code "127") (name "/{slash}SM_FAULT") (class "Default")
      (node (ref "IC1") (pin "71") (pinfunction "RPD11/PMCS1/RD11_71") (pintype "bidirectional"))
      (node (ref "IC17") (pin "24") (pinfunction "-FAULT_24") (pintype "bidirectional"))
      (node (ref "O24") (pin "P$1") (pinfunction "TP_P$1") (pintype "passive"))
      (node (ref "T21") (pin "P$1") (pinfunction "TP_P$1") (pintype "passive"))
    )
    (net (code "128") (name "/{slash}TWI_WAKEUP") (class "Default")
      (node (ref "IC29") (pin "22") (pinfunction "/TWI_WUP_22") (pintype "input"))
      (node (ref "J1") (pin "17") (pinfunction "GPIO97_17") (pintype "passive"))
    )
    (net (code "129") (name "/{slash}USS_PWRON") (class "Default")
      (node (ref "IC1") (pin "82") (pinfunction "RPD5/PMRD/RD5_82") (pintype "bidirectional"))
      (node (ref "O16") (pin "P$1") (pinfunction "TP_P$1") (pintype "passive"))
      (node (ref "R50") (pin "2") (pinfunction "2_2") (pintype "passive"))
      (node (ref "T24") (pin "P$1") (pinfunction "TP_P$1") (pintype "passive"))
    )
    (net (code "130") (name "DGND") (class "Default")
      (node (ref "C1") (pin "2") (pinfunction "2_2") (pintype "passive"))
      (node (ref "C10") (pin "2") (pinfunction "2_2") (pintype "passive"))
      (node (ref "C11") (pin "2") (pinfunction "2_2") (pintype "passive"))
      (node (ref "C12") (pin "2") (pinfunction "2_2") (pintype "passive"))
      (node (ref "C15") (pin "2") (pinfunction "2_2") (pintype "passive"))
      (node (ref "C16") (pin "2") (pinfunction "2_2") (pintype "passive"))
      (node (ref "C17") (pin "2") (pinfunction "2_2") (pintype "passive"))
      (node (ref "C18") (pin "2") (pinfunction "2_2") (pintype "passive"))
      (node (ref "C19") (pin "2") (pinfunction "2_2") (pintype "passive"))
      (node (ref "C2") (pin "2") (pinfunction "2_2") (pintype "passive"))
      (node (ref "C21") (pin "1") (pinfunction "1_1") (pintype "passive"))
      (node (ref "C22") (pin "2") (pinfunction "2_2") (pintype "passive"))
      (node (ref "C23") (pin "2") (pinfunction "2_2") (pintype "passive"))
      (node (ref "C24") (pin "1") (pinfunction "1_1") (pintype "passive"))
      (node (ref "C27") (pin "2") (pinfunction "2_2") (pintype "passive"))
      (node (ref "C28") (pin "2") (pinfunction "2_2") (pintype "passive"))
      (node (ref "C29") (pin "2") (pinfunction "2_2") (pintype "passive"))
      (node (ref "C3") (pin "2") (pinfunction "2_2") (pintype "passive"))
      (node (ref "C30") (pin "2") (pinfunction "2_2") (pintype "passive"))
      (node (ref "C31") (pin "-") (pinfunction "-_-") (pintype "passive"))
      (node (ref "C35") (pin "2") (pinfunction "2_2") (pintype "passive"))
      (node (ref "C36") (pin "2") (pinfunction "2_2") (pintype "passive"))
      (node (ref "C38") (pin "2") (pinfunction "2_2") (pintype "passive"))
      (node (ref "C39") (pin "2") (pinfunction "2_2") (pintype "passive"))
      (node (ref "C40") (pin "2") (pinfunction "2_2") (pintype "passive"))
      (node (ref "C41") (pin "2") (pinfunction "2_2") (pintype "passive"))
      (node (ref "C42") (pin "2") (pinfunction "2_2") (pintype "passive"))
      (node (ref "C44") (pin "1") (pinfunction "1_1") (pintype "passive"))
      (node (ref "C45") (pin "2") (pinfunction "2_2") (pintype "passive"))
      (node (ref "C46") (pin "2") (pinfunction "2_2") (pintype "passive"))
      (node (ref "C47") (pin "2") (pinfunction "2_2") (pintype "passive"))
      (node (ref "C48") (pin "2") (pinfunction "2_2") (pintype "passive"))
      (node (ref "C49") (pin "2") (pinfunction "2_2") (pintype "passive"))
      (node (ref "C5") (pin "2") (pinfunction "2_2") (pintype "passive"))
      (node (ref "C50") (pin "2") (pinfunction "2_2") (pintype "passive"))
      (node (ref "C51") (pin "2") (pinfunction "2_2") (pintype "passive"))
      (node (ref "C52") (pin "2") (pinfunction "2_2") (pintype "passive"))
      (node (ref "C53") (pin "2") (pinfunction "2_2") (pintype "passive"))
      (node (ref "C54") (pin "-") (pinfunction "-_-") (pintype "passive"))
      (node (ref "C55") (pin "2") (pinfunction "2_2") (pintype "passive"))
      (node (ref "C56") (pin "-") (pinfunction "-_-") (pintype "passive"))
      (node (ref "C57") (pin "2") (pinfunction "2_2") (pintype "passive"))
      (node (ref "C58") (pin "2") (pinfunction "2_2") (pintype "passive"))
      (node (ref "C59") (pin "2") (pinfunction "2_2") (pintype "passive"))
      (node (ref "C6") (pin "2") (pinfunction "2_2") (pintype "passive"))
      (node (ref "C60") (pin "2") (pinfunction "2_2") (pintype "passive"))
      (node (ref "C61") (pin "2") (pinfunction "2_2") (pintype "passive"))
      (node (ref "C62") (pin "2") (pinfunction "2_2") (pintype "passive"))
      (node (ref "C63") (pin "2") (pinfunction "2_2") (pintype "passive"))
      (node (ref "C64") (pin "2") (pinfunction "2_2") (pintype "passive"))
      (node (ref "C65") (pin "2") (pinfunction "2_2") (pintype "passive"))
      (node (ref "C66") (pin "2") (pinfunction "2_2") (pintype "passive"))
      (node (ref "C67") (pin "2") (pinfunction "2_2") (pintype "passive"))
      (node (ref "C68") (pin "2") (pinfunction "2_2") (pintype "passive"))
      (node (ref "C7") (pin "2") (pinfunction "2_2") (pintype "passive"))
      (node (ref "C71") (pin "2") (pinfunction "2_2") (pintype "passive"))
      (node (ref "C72") (pin "2") (pinfunction "2_2") (pintype "passive"))
      (node (ref "C75") (pin "2") (pinfunction "2_2") (pintype "passive"))
      (node (ref "C76") (pin "2") (pinfunction "2_2") (pintype "passive"))
      (node (ref "C77") (pin "2") (pinfunction "2_2") (pintype "passive"))
      (node (ref "C78") (pin "1") (pinfunction "1_1") (pintype "passive"))
      (node (ref "C79") (pin "2") (pinfunction "2_2") (pintype "passive"))
      (node (ref "C8") (pin "2") (pinfunction "2_2") (pintype "passive"))
      (node (ref "C81") (pin "-") (pinfunction "-_-") (pintype "passive"))
      (node (ref "C83") (pin "2") (pinfunction "2_2") (pintype "passive"))
      (node (ref "C84") (pin "2") (pinfunction "2_2") (pintype "passive"))
      (node (ref "C85") (pin "2") (pinfunction "2_2") (pintype "passive"))
      (node (ref "C86") (pin "-") (pinfunction "-_-") (pintype "passive"))
      (node (ref "C87") (pin "1") (pinfunction "1_1") (pintype "passive"))
      (node (ref "C88") (pin "2") (pinfunction "2_2") (pintype "passive"))
      (node (ref "C9") (pin "2") (pinfunction "2_2") (pintype "passive"))
      (node (ref "C91") (pin "2") (pinfunction "2_2") (pintype "passive"))
      (node (ref "C92") (pin "2") (pinfunction "2_2") (pintype "passive"))
      (node (ref "C93") (pin "2") (pinfunction "2_2") (pintype "passive"))
      (node (ref "C94") (pin "2") (pinfunction "2_2") (pintype "passive"))
      (node (ref "C95") (pin "2") (pinfunction "2_2") (pintype "passive"))
      (node (ref "C96") (pin "2") (pinfunction "2_2") (pintype "passive"))
      (node (ref "C97") (pin "1") (pinfunction "1_1") (pintype "passive"))
      (node (ref "C98") (pin "2") (pinfunction "2_2") (pintype "passive"))
      (node (ref "D1") (pin "A") (pinfunction "A_A") (pintype "passive"))
      (node (ref "D2") (pin "-") (pinfunction "A_-") (pintype "passive"))
      (node (ref "D5") (pin "K") (pinfunction "K_K") (pintype "passive"))
      (node (ref "D7") (pin "A") (pinfunction "A_A") (pintype "passive"))
      (node (ref "IC1") (pin "15") (pinfunction "VSS2_15") (pintype "input"))
      (node (ref "IC1") (pin "31") (pinfunction "AVSS_31") (pintype "input"))
      (node (ref "IC1") (pin "36") (pinfunction "VSS3_36") (pintype "input"))
      (node (ref "IC1") (pin "45") (pinfunction "VSS4_45") (pintype "input"))
      (node (ref "IC1") (pin "65") (pinfunction "VSS5_65") (pintype "input"))
      (node (ref "IC1") (pin "75") (pinfunction "VSS1_75") (pintype "input"))
      (node (ref "IC10") (pin "1") (pinfunction "GND_1") (pintype "input"))
      (node (ref "IC10") (pin "2") (pinfunction "GND1_2") (pintype "input"))
      (node (ref "IC11") (pin "1") (pinfunction "A0_1") (pintype "input"))
      (node (ref "IC11") (pin "3") (pinfunction "A2_3") (pintype "input"))
      (node (ref "IC11") (pin "4") (pinfunction "GND_4") (pintype "input"))
      (node (ref "IC12") (pin "5") (pinfunction "GND_5") (pintype "input"))
      (node (ref "IC13") (pin "3") (pinfunction "GND_3") (pintype "bidirectional"))
      (node (ref "IC14") (pin "1") (pinfunction "1_1") (pintype "input"))
      (node (ref "IC15") (pin "1") (pinfunction "1_1") (pintype "input"))
      (node (ref "IC16") (pin "4") (pinfunction "V-_4") (pintype "input"))
      (node (ref "IC17") (pin "10") (pinfunction "PGND_10") (pintype "input"))
      (node (ref "IC17") (pin "21") (pinfunction "PRESB_21") (pintype "bidirectional"))
      (node (ref "IC17") (pin "9") (pinfunction "SGND_9") (pintype "input"))
      (node (ref "IC17") (pin "PAD") (pinfunction "PAD_PAD") (pintype "input"))
      (node (ref "IC18") (pin "3") (pinfunction "GND_3") (pintype "input"))
      (node (ref "IC19") (pin "3") (pinfunction "GND_3") (pintype "input"))
      (node (ref "IC2") (pin "3") (pinfunction "GND_3") (pintype "input"))
      (node (ref "IC20") (pin "3") (pinfunction "GND_3") (pintype "input"))
      (node (ref "IC21") (pin "3") (pinfunction "GND_3") (pintype "input"))
      (node (ref "IC22") (pin "3") (pinfunction "GND_3") (pintype "input"))
      (node (ref "IC23") (pin "3") (pinfunction "GND_3") (pintype "input"))
      (node (ref "IC24") (pin "4") (pinfunction "GND_4") (pintype "input"))
      (node (ref "IC24") (pin "5") (pinfunction "A2_5") (pintype "input"))
      (node (ref "IC24") (pin "6") (pinfunction "A1_6") (pintype "input"))
      (node (ref "IC25") (pin "19") (pinfunction "PGND_19") (pintype "input"))
      (node (ref "IC25") (pin "24") (pinfunction "PGND_24") (pintype "input"))
      (node (ref "IC25") (pin "3") (pinfunction "GND_3") (pintype "input"))
      (node (ref "IC25") (pin "4") (pinfunction "GND_4") (pintype "input"))
      (node (ref "IC25") (pin "8") (pinfunction "AGND_8") (pintype "input"))
      (node (ref "IC25") (pin "EP") (pinfunction "EP_EP") (pintype "input"))
      (node (ref "IC26") (pin "1") (pinfunction "1_1") (pintype "input"))
      (node (ref "IC27") (pin "1") (pinfunction "1_1") (pintype "input"))
      (node (ref "IC28") (pin "1") (pinfunction "1_1") (pintype "input"))
      (node (ref "IC29") (pin "11") (pinfunction "GND_11") (pintype "input"))
      (node (ref "IC29") (pin "17") (pinfunction "GPIO_17") (pintype "input"))
      (node (ref "IC29") (pin "18") (pinfunction "GND_18") (pintype "input"))
      (node (ref "IC29") (pin "20") (pinfunction "/PIRQ_20") (pintype "input"))
      (node (ref "IC29") (pin "21") (pinfunction "ATEST_21") (pintype "input"))
      (node (ref "IC29") (pin "23") (pinfunction "ATEST_23") (pintype "input"))
      (node (ref "IC29") (pin "25") (pinfunction "GND_25") (pintype "input"))
      (node (ref "IC29") (pin "26") (pinfunction "ATEST_26") (pintype "input"))
      (node (ref "IC29") (pin "4") (pinfunction "GND_4") (pintype "input"))
      (node (ref "IC29") (pin "8") (pinfunction "TESTL_8") (pintype "input"))
      (node (ref "IC29") (pin "9") (pinfunction "TESTBI/GPIO/XT_9") (pintype "input"))
      (node (ref "IC3") (pin "2") (pinfunction "VSS_2") (pintype "input"))
      (node (ref "IC4") (pin "1") (pinfunction "GND_1") (pintype "input"))
      (node (ref "IC4") (pin "2") (pinfunction "GND1_2") (pintype "input"))
      (node (ref "IC5") (pin "3") (pinfunction "GND_3") (pintype "input"))
      (node (ref "IC6") (pin "2") (pinfunction "GND_2") (pintype "input"))
      (node (ref "IC7") (pin "1") (pinfunction "A0_1") (pintype "input"))
      (node (ref "IC7") (pin "2") (pinfunction "A1_2") (pintype "input"))
      (node (ref "IC7") (pin "3") (pinfunction "A2_3") (pintype "input"))
      (node (ref "IC7") (pin "4") (pinfunction "GND_4") (pintype "input"))
      (node (ref "IC7") (pin "7") (pinfunction "WP_7") (pintype "input"))
      (node (ref "IC8") (pin "10") (pinfunction "SYNC_10") (pintype "bidirectional"))
      (node (ref "IC8") (pin "EP") (pinfunction "GND_EP") (pintype "bidirectional"))
      (node (ref "IC9") (pin "4") (pinfunction "GND_4") (pintype "input"))
      (node (ref "J1") (pin "2") (pinfunction "GND1_2") (pintype "passive"))
      (node (ref "J1") (pin "21") (pinfunction "GND4_21") (pintype "passive"))
      (node (ref "J1") (pin "3") (pinfunction "GND2_3") (pintype "passive"))
      (node (ref "J1") (pin "36") (pinfunction "GND5_36") (pintype "passive"))
      (node (ref "J1") (pin "7") (pinfunction "GND3_7") (pintype "passive"))
      (node (ref "J10") (pin "3") (pinfunction "3_3") (pintype "passive"))
      (node (ref "J12") (pin "4_GND") (pinfunction "GND_4_GND") (pintype "bidirectional"))
      (node (ref "J12") (pin "SH1") (pinfunction "GND_SH1_SH1") (pintype "bidirectional"))
      (node (ref "J12") (pin "SH2") (pinfunction "GND_SH2_SH2") (pintype "bidirectional"))
      (node (ref "J13") (pin "1") (pinfunction "1_1") (pintype "passive"))
      (node (ref "J14") (pin "1") (pinfunction "1_1") (pintype "passive"))
      (node (ref "J15") (pin "7") (pinfunction "7_7") (pintype "passive"))
      (node (ref "J15") (pin "8") (pinfunction "8_8") (pintype "passive"))
      (node (ref "J16") (pin "4") (pinfunction "4_4") (pintype "passive"))
      (node (ref "J17") (pin "3") (pinfunction "3_3") (pintype "passive"))
      (node (ref "J18") (pin "1") (pinfunction "1_1") (pintype "passive"))
      (node (ref "J19") (pin "1") (pinfunction "1_1") (pintype "passive"))
      (node (ref "J2") (pin "C5") (pinfunction "C5/GND_C5") (pintype "input"))
      (node (ref "J20") (pin "1") (pinfunction "1_1") (pintype "passive"))
      (node (ref "J21") (pin "7") (pinfunction "7_7") (pintype "passive"))
      (node (ref "J21") (pin "8") (pinfunction "8_8") (pintype "passive"))
      (node (ref "J22") (pin "4") (pinfunction "4_4") (pintype "passive"))
      (node (ref "J5") (pin "1") (pinfunction "1_1") (pintype "passive"))
      (node (ref "J6") (pin "3") (pinfunction "3_3") (pintype "passive"))
      (node (ref "J8") (pin "4") (pinfunction "4_4") (pintype "passive"))
      (node (ref "J9") (pin "7") (pinfunction "1_7") (pintype "passive"))
      (node (ref "J9") (pin "8") (pinfunction "1_8") (pintype "passive"))
      (node (ref "L12") (pin "1") (pinfunction "1_1") (pintype "passive"))
      (node (ref "PCB1") (pin "1") (pinfunction "1_1") (pintype "bidirectional"))
      (node (ref "PCB1") (pin "2") (pinfunction "2_2") (pintype "bidirectional"))
      (node (ref "PCB1") (pin "3") (pinfunction "3_3") (pintype "bidirectional"))
      (node (ref "PCB1") (pin "4") (pinfunction "4_4") (pintype "bidirectional"))
      (node (ref "PCB3") (pin "1") (pinfunction "P$1_1") (pintype "bidirectional"))
      (node (ref "Q10") (pin "1") (pinfunction "S_1") (pintype "passive"))
      (node (ref "Q10") (pin "4") (pinfunction "S_4") (pintype "passive"))
      (node (ref "Q9") (pin "1") (pinfunction "S_1") (pintype "passive"))
      (node (ref "Q9") (pin "4") (pinfunction "S_4") (pintype "passive"))
      (node (ref "R10") (pin "2") (pinfunction "2_2") (pintype "passive"))
      (node (ref "R12") (pin "1") (pinfunction "1_1") (pintype "passive"))
      (node (ref "R13") (pin "2") (pinfunction "2_2") (pintype "passive"))
      (node (ref "R15") (pin "1") (pinfunction "1_1") (pintype "passive"))
      (node (ref "R17") (pin "2") (pinfunction "2_2") (pintype "passive"))
      (node (ref "R19") (pin "2") (pinfunction "2_2") (pintype "passive"))
      (node (ref "R2") (pin "2") (pinfunction "2_2") (pintype "passive"))
      (node (ref "R21") (pin "2") (pinfunction "2_2") (pintype "passive"))
      (node (ref "R31") (pin "2") (pinfunction "2_2") (pintype "passive"))
      (node (ref "R40") (pin "1") (pinfunction "1_1") (pintype "passive"))
      (node (ref "R41") (pin "2") (pinfunction "2_2") (pintype "passive"))
      (node (ref "R43") (pin "1") (pinfunction "1_1") (pintype "passive"))
      (node (ref "R44") (pin "2") (pinfunction "2_2") (pintype "passive"))
      (node (ref "R46") (pin "1") (pinfunction "1_1") (pintype "passive"))
      (node (ref "R48") (pin "1") (pinfunction "1_1") (pintype "passive"))
      (node (ref "R56") (pin "1") (pinfunction "1_1") (pintype "passive"))
      (node (ref "R57") (pin "1") (pinfunction "1_1") (pintype "passive"))
      (node (ref "R63") (pin "2") (pinfunction "2_2") (pintype "passive"))
      (node (ref "R70") (pin "1") (pinfunction "1_1") (pintype "passive"))
      (node (ref "R74") (pin "2") (pinfunction "2_2") (pintype "passive"))
      (node (ref "R8") (pin "1") (pinfunction "1_1") (pintype "passive"))
      (node (ref "R83") (pin "1") (pinfunction "1_1") (pintype "passive"))
      (node (ref "R84") (pin "1") (pinfunction "1_1") (pintype "passive"))
      (node (ref "R85") (pin "1") (pinfunction "1_1") (pintype "passive"))
      (node (ref "R88") (pin "1") (pinfunction "1_1") (pintype "passive"))
      (node (ref "R89") (pin "1") (pinfunction "1_1") (pintype "passive"))
      (node (ref "R9") (pin "1") (pinfunction "1_1") (pintype "passive"))
      (node (ref "R96") (pin "2") (pinfunction "2_2") (pintype "passive"))
      (node (ref "R99") (pin "2") (pinfunction "2_2") (pintype "passive"))
    )
    (net (code "131") (name "Net-(C11-Pad1)") (class "Default")
      (node (ref "C11") (pin "1") (pinfunction "1_1") (pintype "passive"))
      (node (ref "C19") (pin "1") (pinfunction "1_1") (pintype "passive"))
      (node (ref "IC25") (pin "7") (pinfunction "AVCC_7") (pintype "input"))
      (node (ref "R4") (pin "2") (pinfunction "2_2") (pintype "passive"))
      (node (ref "R5") (pin "1") (pinfunction "1_1") (pintype "passive"))
    )
    (net (code "132") (name "Net-(C24-Pad2)") (class "Default")
      (node (ref "C24") (pin "2") (pinfunction "2_2") (pintype "passive"))
      (node (ref "R77") (pin "2") (pinfunction "2_2") (pintype "passive"))
    )
    (net (code "133") (name "Net-(C39-Pad1)") (class "Default")
      (node (ref "C39") (pin "1") (pinfunction "1_1") (pintype "passive"))
      (node (ref "IC14") (pin "4") (pinfunction "4_4") (pintype "input"))
      (node (ref "R30") (pin "1") (pinfunction "1_1") (pintype "passive"))
    )
    (net (code "134") (name "Net-(C40-Pad1)") (class "Default")
      (node (ref "C40") (pin "1") (pinfunction "1_1") (pintype "passive"))
      (node (ref "R90") (pin "1") (pinfunction "1_1") (pintype "passive"))
      (node (ref "R91") (pin "1") (pinfunction "1_1") (pintype "passive"))
    )
    (net (code "135") (name "Net-(C68-Pad1)") (class "Default")
      (node (ref "C68") (pin "1") (pinfunction "1_1") (pintype "passive"))
      (node (ref "R112") (pin "1") (pinfunction "1_1") (pintype "passive"))
      (node (ref "R86") (pin "2") (pinfunction "2_2") (pintype "passive"))
      (node (ref "R88") (pin "2") (pinfunction "2_2") (pintype "passive"))
    )
    (net (code "136") (name "Net-(C71-Pad1)") (class "Default")
      (node (ref "C71") (pin "1") (pinfunction "1_1") (pintype "passive"))
      (node (ref "R113") (pin "1") (pinfunction "1_1") (pintype "passive"))
      (node (ref "R87") (pin "2") (pinfunction "2_2") (pintype "passive"))
      (node (ref "R89") (pin "2") (pinfunction "2_2") (pintype "passive"))
    )
    (net (code "137") (name "Net-(C89-Pad+)") (class "Default")
      (node (ref "C89") (pin "+") (pinfunction "+_+") (pintype "passive"))
      (node (ref "C90") (pin "1") (pinfunction "1_1") (pintype "passive"))
      (node (ref "JP2") (pin "2") (pinfunction "2_2") (pintype "bidirectional"))
    )
    (net (code "138") (name "Net-(C89-Pad-)") (class "Default")
      (node (ref "C89") (pin "-") (pinfunction "-_-") (pintype "passive"))
      (node (ref "C90") (pin "2") (pinfunction "2_2") (pintype "passive"))
      (node (ref "R78") (pin "1") (pinfunction "1_1") (pintype "passive"))
      (node (ref "R79") (pin "1") (pinfunction "1_1") (pintype "passive"))
      (node (ref "R80") (pin "2") (pinfunction "2_2") (pintype "passive"))
      (node (ref "R81") (pin "2") (pinfunction "2_2") (pintype "passive"))
    )
    (net (code "139") (name "Net-(D2-C)") (class "Default")
      (node (ref "C26") (pin "1") (pinfunction "1_1") (pintype "passive"))
      (node (ref "C30") (pin "1") (pinfunction "1_1") (pintype "passive"))
      (node (ref "C31") (pin "+") (pinfunction "+_+") (pintype "passive"))
      (node (ref "D2") (pin "+") (pinfunction "C_+") (pintype "passive"))
      (node (ref "IC8") (pin "1") (pinfunction "BD_1") (pintype "bidirectional"))
      (node (ref "L9") (pin "2") (pinfunction "2_2") (pintype "passive"))
      (node (ref "R129") (pin "2") (pinfunction "2_2") (pintype "passive"))
      (node (ref "R20") (pin "1") (pinfunction "1_1") (pintype "passive"))
    )
    (net (code "140") (name "Net-(D3-PadA)") (class "Default")
      (node (ref "D3") (pin "A") (pinfunction "A_A") (pintype "passive"))
      (node (ref "D4") (pin "A") (pinfunction "A_A") (pintype "passive"))
      (node (ref "J3") (pin "2") (pinfunction "2_2") (pintype "passive"))
      (node (ref "J3") (pin "7") (pinfunction "7_7") (pintype "passive"))
      (node (ref "J3") (pin "8") (pinfunction "8_8") (pintype "passive"))
      (node (ref "J4") (pin "2") (pinfunction "2_2") (pintype "passive"))
      (node (ref "J4") (pin "7") (pinfunction "7_7") (pintype "passive"))
      (node (ref "J4") (pin "8") (pinfunction "8_8") (pintype "passive"))
      (node (ref "L12") (pin "2") (pinfunction "2_2") (pintype "passive"))
    )
    (net (code "141") (name "Net-(D5-PadA)") (class "Default")
      (node (ref "D5") (pin "A") (pinfunction "A_A") (pintype "passive"))
      (node (ref "R29") (pin "2") (pinfunction "2_2") (pintype "passive"))
    )
    (net (code "142") (name "Net-(F1-Pad1)") (class "Default")
      (node (ref "F1") (pin "1") (pinfunction "1_1") (pintype "passive"))
      (node (ref "J19") (pin "2") (pinfunction "2_2") (pintype "passive"))
    )
    (net (code "143") (name "Net-(IC1-AN11{slash}PMA12{slash}RB11)") (class "Default")
      (node (ref "C74") (pin "1") (pinfunction "1_1") (pintype "passive"))
      (node (ref "IC1") (pin "35") (pinfunction "AN11/PMA12/RB11_35") (pintype "bidirectional"))
      (node (ref "R110") (pin "2") (pinfunction "2_2") (pintype "passive"))
      (node (ref "R111") (pin "1") (pinfunction "1_1") (pintype "passive"))
    )
    (net (code "144") (name "Net-(IC1-AN15{slash}RPB15{slash}PMA0{slash}CTED6{slash}{slash}RB15)") (class "Default")
      (node (ref "C73") (pin "1") (pinfunction "1_1") (pintype "passive"))
      (node (ref "IC1") (pin "44") (pinfunction "AN15/RPB15/PMA0/CTED6//RB15_44") (pintype "bidirectional"))
      (node (ref "R104") (pin "2") (pinfunction "2_2") (pintype "passive"))
      (node (ref "R107") (pin "1") (pinfunction "1_1") (pintype "passive"))
    )
    (net (code "145") (name "Net-(IC1-AVDD)") (class "Default")
      (node (ref "C55") (pin "1") (pinfunction "1_1") (pintype "passive"))
      (node (ref "C56") (pin "+") (pinfunction "+_+") (pintype "passive"))
      (node (ref "C88") (pin "1") (pinfunction "1_1") (pintype "passive"))
      (node (ref "IC1") (pin "30") (pinfunction "AVDD_30") (pintype "input"))
      (node (ref "R92") (pin "2") (pinfunction "2_2") (pintype "passive"))
    )
    (net (code "146") (name "Net-(IC1-CLKI{slash}RC12{slash}OSC1)") (class "Default")
      (node (ref "C60") (pin "1") (pinfunction "1_1") (pintype "passive"))
      (node (ref "IC1") (pin "63") (pinfunction "CLKI/RC12/OSC1_63") (pintype "bidirectional"))
      (node (ref "X1") (pin "3") (pinfunction "2_3") (pintype "passive"))
    )
    (net (code "147") (name "Net-(IC1-CLKO{slash}RC15{slash}OSC2)") (class "Default")
      (node (ref "C61") (pin "1") (pinfunction "1_1") (pintype "passive"))
      (node (ref "IC1") (pin "64") (pinfunction "CLKO/RC15/OSC2_64") (pintype "bidirectional"))
      (node (ref "X1") (pin "1") (pinfunction "1_1") (pintype "passive"))
    )
    (net (code "148") (name "Net-(IC1-CVREFOUT{slash}AN10{slash}RPB10{slash}PMA13{slash}CTED11{slash}RB10)") (class "Default")
      (node (ref "C74") (pin "2") (pinfunction "2_2") (pintype "passive"))
      (node (ref "IC1") (pin "34") (pinfunction "CVREFOUT/AN10/RPB10/PMA13/CTED11/RB10_34") (pintype "bidirectional"))
      (node (ref "R111") (pin "2") (pinfunction "2_2") (pintype "passive"))
    )
    (net (code "149") (name "Net-(IC1-RPD14{slash}RD14)") (class "Default")
      (node (ref "C73") (pin "2") (pinfunction "2_2") (pintype "passive"))
      (node (ref "IC1") (pin "47") (pinfunction "RPD14/RD14_47") (pintype "bidirectional"))
      (node (ref "R107") (pin "2") (pinfunction "2_2") (pintype "passive"))
    )
    (net (code "150") (name "Net-(IC1-VCAP)") (class "Default")
      (node (ref "C53") (pin "1") (pinfunction "1_1") (pintype "passive"))
      (node (ref "C54") (pin "+") (pinfunction "+_+") (pintype "passive"))
      (node (ref "IC1") (pin "85") (pinfunction "VCAP_85") (pintype "input"))
      (node (ref "R118") (pin "2") (pinfunction "2_2") (pintype "passive"))
    )
    (net (code "151") (name "Net-(IC3-GP2{slash}T0CK)") (class "Default")
      (node (ref "IC3") (pin "4") (pinfunction "GP2/T0CK_4") (pintype "bidirectional"))
      (node (ref "R61") (pin "1") (pinfunction "1_1") (pintype "passive"))
    )
    (net (code "152") (name "Net-(IC3-VDD)") (class "Default")
      (node (ref "C6") (pin "1") (pinfunction "1_1") (pintype "passive"))
      (node (ref "IC3") (pin "5") (pinfunction "VDD_5") (pintype "input"))
      (node (ref "J10") (pin "2") (pinfunction "2_2") (pintype "passive"))
      (node (ref "R3") (pin "2") (pinfunction "2_2") (pintype "passive"))
    )
    (net (code "153") (name "Net-(IC4-OUT)") (class "Default")
      (node (ref "IC4") (pin "3") (pinfunction "OUT_3") (pintype "output"))
      (node (ref "R36") (pin "1") (pinfunction "1_1") (pintype "passive"))
    )
    (net (code "154") (name "Net-(IC4-VIN-)") (class "Default")
      (node (ref "C32") (pin "1") (pinfunction "1_1") (pintype "passive"))
      (node (ref "IC4") (pin "4") (pinfunction "VIN-_4") (pintype "input"))
      (node (ref "Q7") (pin "4") (pinfunction "S_4") (pintype "passive"))
      (node (ref "R11") (pin "1") (pinfunction "1_1") (pintype "passive"))
      (node (ref "R16") (pin "1") (pinfunction "1_1") (pintype "passive"))
      (node (ref "R35") (pin "1") (pinfunction "1_1") (pintype "passive"))
      (node (ref "R37") (pin "1") (pinfunction "1_1") (pintype "passive"))
    )
    (net (code "155") (name "Net-(IC5-IN)") (class "Default")
      (node (ref "C80") (pin "2") (pinfunction "2_2") (pintype "passive"))
      (node (ref "IC5") (pin "2") (pinfunction "IN_2") (pintype "input"))
      (node (ref "R121") (pin "1") (pinfunction "1_1") (pintype "passive"))
    )
    (net (code "156") (name "Net-(IC6-HTH)") (class "Default")
      (node (ref "IC6") (pin "1") (pinfunction "HTH_1") (pintype "input"))
      (node (ref "R46") (pin "2") (pinfunction "2_2") (pintype "passive"))
      (node (ref "R47") (pin "1") (pinfunction "1_1") (pintype "passive"))
    )
    (net (code "157") (name "Net-(IC6-LTH)") (class "Default")
      (node (ref "IC6") (pin "3") (pinfunction "LTH_3") (pintype "input"))
      (node (ref "R33") (pin "1") (pinfunction "1_1") (pintype "passive"))
      (node (ref "R47") (pin "2") (pinfunction "2_2") (pintype "passive"))
    )
    (net (code "158") (name "Net-(IC6-VDD)") (class "Default")
      (node (ref "C35") (pin "1") (pinfunction "1_1") (pintype "passive"))
      (node (ref "IC6") (pin "5") (pinfunction "VDD_5") (pintype "input"))
      (node (ref "R28") (pin "1") (pinfunction "1_1") (pintype "passive"))
    )
    (net (code "159") (name "Net-(IC8-BOOST)") (class "Default")
      (node (ref "C25") (pin "2") (pinfunction "2_2") (pintype "passive"))
      (node (ref "IC8") (pin "2") (pinfunction "BOOST_2") (pintype "bidirectional"))
    )
    (net (code "160") (name "Net-(IC8-EN)") (class "Default")
      (node (ref "IC8") (pin "5") (pinfunction "EN_5") (pintype "bidirectional"))
      (node (ref "JP1") (pin "2") (pinfunction "2_2") (pintype "bidirectional"))
      (node (ref "R22") (pin "2") (pinfunction "2_2") (pintype "passive"))
    )
    (net (code "161") (name "Net-(IC8-FB)") (class "Default")
      (node (ref "C26") (pin "2") (pinfunction "2_2") (pintype "passive"))
      (node (ref "IC8") (pin "6") (pinfunction "FB_6") (pintype "bidirectional"))
      (node (ref "R19") (pin "1") (pinfunction "1_1") (pintype "passive"))
      (node (ref "R20") (pin "2") (pinfunction "2_2") (pintype "passive"))
    )
    (net (code "162") (name "Net-(IC8-RT)") (class "Default")
      (node (ref "IC8") (pin "8") (pinfunction "RT_8") (pintype "bidirectional"))
      (node (ref "R17") (pin "1") (pinfunction "1_1") (pintype "passive"))
    )
    (net (code "163") (name "Net-(IC8-SS)") (class "Default")
      (node (ref "IC8") (pin "7") (pinfunction "SS_7") (pintype "bidirectional"))
      (node (ref "R77") (pin "1") (pinfunction "1_1") (pintype "passive"))
    )
    (net (code "164") (name "Net-(IC8-SW)") (class "Default")
      (node (ref "C25") (pin "1") (pinfunction "1_1") (pintype "passive"))
      (node (ref "D7") (pin "K") (pinfunction "K_K") (pintype "passive"))
      (node (ref "IC8") (pin "3") (pinfunction "SW_3") (pintype "bidirectional"))
      (node (ref "L9") (pin "1") (pinfunction "1_1") (pintype "passive"))
    )
    (net (code "165") (name "Net-(IC8-VIN)") (class "Default")
      (node (ref "C22") (pin "1") (pinfunction "1_1") (pintype "passive"))
      (node (ref "C23") (pin "1") (pinfunction "1_1") (pintype "passive"))
      (node (ref "C84") (pin "1") (pinfunction "1_1") (pintype "passive"))
      (node (ref "IC8") (pin "4") (pinfunction "VIN_4") (pintype "bidirectional"))
      (node (ref "JP1") (pin "3") (pinfunction "3_3") (pintype "bidirectional"))
      (node (ref "L2") (pin "2") (pinfunction "2_2") (pintype "passive"))
      (node (ref "R22") (pin "1") (pinfunction "1_1") (pintype "passive"))
    )
    (net (code "166") (name "Net-(IC10-OUT)") (class "Default")
      (node (ref "IC10") (pin "3") (pinfunction "OUT_3") (pintype "output"))
      (node (ref "R102") (pin "1") (pinfunction "1_1") (pintype "passive"))
    )
    (net (code "167") (name "Net-(IC10-VIN+)") (class "Default")
      (node (ref "C29") (pin "1") (pinfunction "1_1") (pintype "passive"))
      (node (ref "C83") (pin "1") (pinfunction "1_1") (pintype "passive"))
      (node (ref "D1") (pin "C") (pinfunction "C_C") (pintype "passive"))
      (node (ref "F1") (pin "2") (pinfunction "2_2") (pintype "passive"))
      (node (ref "IC10") (pin "5") (pinfunction "VIN+_5") (pintype "input"))
      (node (ref "IC4") (pin "5") (pinfunction "VIN+_5") (pintype "input"))
      (node (ref "R35") (pin "2") (pinfunction "2_2") (pintype "passive"))
      (node (ref "R37") (pin "2") (pinfunction "2_2") (pintype "passive"))
      (node (ref "R39") (pin "2") (pinfunction "2_2") (pintype "passive"))
    )
    (net (code "168") (name "Net-(IC11-WP)") (class "Default")
      (node (ref "IC11") (pin "7") (pinfunction "WP_7") (pintype "input"))
      (node (ref "R18") (pin "2") (pinfunction "2_2") (pintype "passive"))
      (node (ref "TP1") (pin "P$1") (pinfunction "TP_P$1") (pintype "passive"))
    )
    (net (code "169") (name "Net-(IC13-VIN)") (class "Default")
      (node (ref "C58") (pin "1") (pinfunction "1_1") (pintype "passive"))
      (node (ref "C59") (pin "1") (pinfunction "1_1") (pintype "passive"))
      (node (ref "IC13") (pin "1") (pinfunction "VIN_1") (pintype "bidirectional"))
      (node (ref "R93") (pin "2") (pinfunction "2_2") (pintype "passive"))
    )
    (net (code "170") (name "Net-(IC16A-+IN)") (class "Default")
      (node (ref "C62") (pin "1") (pinfunction "1_1") (pintype "passive"))
      (node (ref "IC16") (pin "3") (pinfunction "+IN_3") (pintype "input"))
      (node (ref "R95") (pin "2") (pinfunction "2_2") (pintype "passive"))
      (node (ref "R96") (pin "1") (pinfunction "1_1") (pintype "passive"))
    )
    (net (code "171") (name "Net-(IC16A--IN)") (class "Default")
      (node (ref "IC16") (pin "1") (pinfunction "OUT_1") (pintype "output"))
      (node (ref "IC16") (pin "2") (pinfunction "-IN_2") (pintype "input"))
      (node (ref "R101") (pin "2") (pinfunction "2_2") (pintype "passive"))
    )
    (net (code "172") (name "Net-(IC16B-+IN)") (class "Default")
      (node (ref "C63") (pin "1") (pinfunction "1_1") (pintype "passive"))
      (node (ref "IC16") (pin "5") (pinfunction "+IN_5") (pintype "input"))
      (node (ref "R98") (pin "2") (pinfunction "2_2") (pintype "passive"))
      (node (ref "R99") (pin "1") (pinfunction "1_1") (pintype "passive"))
    )
    (net (code "173") (name "Net-(IC16B--IN)") (class "Default")
      (node (ref "IC16") (pin "6") (pinfunction "-IN_6") (pintype "input"))
      (node (ref "IC16") (pin "7") (pinfunction "OUT_7") (pintype "output"))
      (node (ref "R100") (pin "2") (pinfunction "2_2") (pintype "passive"))
    )
    (net (code "174") (name "Net-(IC16C-V+)") (class "Default")
      (node (ref "C67") (pin "1") (pinfunction "1_1") (pintype "passive"))
      (node (ref "IC16") (pin "8") (pinfunction "V+_8") (pintype "input"))
      (node (ref "R103") (pin "1") (pinfunction "1_1") (pintype "passive"))
    )
    (net (code "175") (name "Net-(IC17--UNDERV)") (class "Default")
      (node (ref "IC17") (pin "23") (pinfunction "-UNDERV_23") (pintype "bidirectional"))
      (node (ref "R1") (pin "1") (pinfunction "1_1") (pintype "passive"))
    )
    (net (code "176") (name "Net-(IC17-C+)") (class "Default")
      (node (ref "C4") (pin "2") (pinfunction "2_2") (pintype "passive"))
      (node (ref "IC17") (pin "14") (pinfunction "C+_14") (pintype "input"))
    )
    (net (code "177") (name "Net-(IC17-C-)") (class "Default")
      (node (ref "C4") (pin "1") (pinfunction "1_1") (pintype "passive"))
      (node (ref "IC17") (pin "11") (pinfunction "C-_11") (pintype "input"))
    )
    (net (code "178") (name "Net-(IC17-CPO)") (class "Default")
      (node (ref "C5") (pin "1") (pinfunction "1_1") (pintype "passive"))
      (node (ref "IC17") (pin "15") (pinfunction "CPO_15") (pintype "bidirectional"))
    )
    (net (code "179") (name "Net-(IC17-DVCC)") (class "Default")
      (node (ref "C2") (pin "1") (pinfunction "1_1") (pintype "passive"))
      (node (ref "C3") (pin "1") (pinfunction "1_1") (pintype "passive"))
      (node (ref "C77") (pin "1") (pinfunction "1_1") (pintype "passive"))
      (node (ref "IC17") (pin "1") (pinfunction "DVCC_1") (pintype "bidirectional"))
      (node (ref "IC17") (pin "12") (pinfunction "SVBAT_12") (pintype "input"))
      (node (ref "IC17") (pin "13") (pinfunction "PVBAT_13") (pintype "input"))
      (node (ref "R1") (pin "2") (pinfunction "2_2") (pintype "passive"))
      (node (ref "R114") (pin "2") (pinfunction "2_2") (pintype "passive"))
    )
    (net (code "180") (name "Net-(IC17-NC{slash}-NO)") (class "Default")
      (node (ref "IC17") (pin "22") (pinfunction "NC/-NO_22") (pintype "bidirectional"))
      (node (ref "R2") (pin "1") (pinfunction "1_1") (pintype "passive"))
    )
    (net (code "181") (name "Net-(IC18-A)") (class "Default")
      (node (ref "IC18") (pin "1") (pinfunction "A_1") (pintype "input"))
      (node (ref "IC5") (pin "4") (pinfunction "OUT_4") (pintype "output"))
    )
    (net (code "182") (name "Net-(IC18-B)") (class "Default")
      (node (ref "IC18") (pin "2") (pinfunction "B_2") (pintype "input"))
      (node (ref "R122") (pin "2") (pinfunction "2_2") (pintype "passive"))
    )
    (net (code "183") (name "Net-(IC18-Y)") (class "Default")
      (node (ref "IC18") (pin "4") (pinfunction "Y_4") (pintype "output"))
      (node (ref "IC2") (pin "2") (pinfunction "B_2") (pintype "input"))
    )
    (net (code "184") (name "Net-(IC19-VCC)") (class "Default")
      (node (ref "C98") (pin "1") (pinfunction "1_1") (pintype "passive"))
      (node (ref "IC19") (pin "5") (pinfunction "VCC_5") (pintype "input"))
      (node (ref "IC20") (pin "5") (pinfunction "VCC_5") (pintype "input"))
      (node (ref "R132") (pin "2") (pinfunction "2_2") (pintype "passive"))
    )
    (net (code "185") (name "Net-(IC22-IN)") (class "Default")
      (node (ref "C45") (pin "1") (pinfunction "1_1") (pintype "passive"))
      (node (ref "IC22") (pin "2") (pinfunction "IN_2") (pintype "input"))
      (node (ref "R64") (pin "1") (pinfunction "1_1") (pintype "passive"))
    )
    (net (code "186") (name "Net-(IC22-VCC)") (class "Default")
      (node (ref "C79") (pin "1") (pinfunction "1_1") (pintype "passive"))
      (node (ref "IC22") (pin "5") (pinfunction "VCC_5") (pintype "input"))
      (node (ref "IC23") (pin "5") (pinfunction "VCC_5") (pintype "input"))
      (node (ref "R117") (pin "1") (pinfunction "1_1") (pintype "passive"))
    )
    (net (code "187") (name "Net-(IC23-IN)") (class "Default")
      (node (ref "C46") (pin "1") (pinfunction "1_1") (pintype "passive"))
      (node (ref "IC23") (pin "2") (pinfunction "IN_2") (pintype "input"))
      (node (ref "R76") (pin "1") (pinfunction "1_1") (pintype "passive"))
    )
    (net (code "188") (name "Net-(IC25-AVCC-Pad14)") (class "Default")
      (node (ref "IC25") (pin "14") (pinfunction "AVCC_14") (pintype "input"))
      (node (ref "R5") (pin "2") (pinfunction "2_2") (pintype "passive"))
    )
    (net (code "189") (name "Net-(IC25-GVDD)") (class "Default")
      (node (ref "C12") (pin "1") (pinfunction "1_1") (pintype "passive"))
      (node (ref "IC25") (pin "10") (pinfunction "PLIMIT_10") (pintype "input"))
      (node (ref "IC25") (pin "9") (pinfunction "GVDD_9") (pintype "output"))
    )
    (net (code "190") (name "Net-(IC25-~{FAULT})") (class "Default")
      (node (ref "IC25") (pin "1") (pinfunction "~{SD}_1") (pintype "input"))
      (node (ref "IC25") (pin "2") (pinfunction "~{FAULT}_2") (pintype "output"))
      (node (ref "R6") (pin "2") (pinfunction "2_2") (pintype "passive"))
      (node (ref "R7") (pin "2") (pinfunction "2_2") (pintype "passive"))
    )
    (net (code "191") (name "Net-(J1-RXD-C)") (class "Default")
      (node (ref "J1") (pin "34") (pinfunction "RXD-C_34") (pintype "passive"))
      (node (ref "R123") (pin "1") (pinfunction "1_1") (pintype "passive"))
    )
    (net (code "192") (name "Net-(J1-TXD-C)") (class "Default")
      (node (ref "J1") (pin "35") (pinfunction "TXD-C_35") (pintype "passive"))
      (node (ref "R124") (pin "2") (pinfunction "2_2") (pintype "passive"))
    )
    (net (code "193") (name "Net-(J7-Pad2)") (class "Default")
      (node (ref "J7") (pin "2") (pinfunction "2_2") (pintype "passive"))
      (node (ref "R66") (pin "2") (pinfunction "2_2") (pintype "passive"))
      (node (ref "R67") (pin "2") (pinfunction "2_2") (pintype "passive"))
    )
    (net (code "194") (name "Net-(J7-Pad3)") (class "Default")
      (node (ref "J7") (pin "3") (pinfunction "3_3") (pintype "passive"))
      (node (ref "R62") (pin "1") (pinfunction "1_1") (pintype "passive"))
    )
    (net (code "195") (name "Net-(J8-Pad2)") (class "Default")
      (node (ref "J8") (pin "2") (pinfunction "2_2") (pintype "passive"))
      (node (ref "R78") (pin "2") (pinfunction "2_2") (pintype "passive"))
      (node (ref "R79") (pin "2") (pinfunction "2_2") (pintype "passive"))
    )
    (net (code "196") (name "Net-(J8-Pad3)") (class "Default")
      (node (ref "J8") (pin "3") (pinfunction "3_3") (pintype "passive"))
      (node (ref "R73") (pin "1") (pinfunction "1_1") (pintype "passive"))
    )
    (net (code "197") (name "Net-(J12-+5V)") (class "Default")
      (node (ref "C85") (pin "1") (pinfunction "1_1") (pintype "passive"))
      (node (ref "D6") (pin "A") (pinfunction "A_A") (pintype "passive"))
      (node (ref "IC15") (pin "4") (pinfunction "4_4") (pintype "input"))
      (node (ref "J12") (pin "1_+5V") (pinfunction "+5V_1_+5V") (pintype "bidirectional"))
      (node (ref "R128") (pin "1") (pinfunction "1_1") (pintype "passive"))
    )
    (net (code "198") (name "Net-(J20-Pad2)") (class "Default")
      (node (ref "J20") (pin "2") (pinfunction "2_2") (pintype "passive"))
      (node (ref "Q7") (pin "1") (pinfunction "D_1") (pintype "passive"))
      (node (ref "Q7") (pin "2") (pinfunction "D_2") (pintype "passive"))
      (node (ref "Q7") (pin "5") (pinfunction "D_5") (pintype "passive"))
      (node (ref "Q7") (pin "6") (pinfunction "D_6") (pintype "passive"))
    )
    (net (code "199") (name "Net-(JP1-Pad1)") (class "Default")
      (node (ref "JP1") (pin "1") (pinfunction "1_1") (pintype "bidirectional"))
      (node (ref "R21") (pin "1") (pinfunction "1_1") (pintype "passive"))
    )
    (net (code "200") (name "Net-(L1-Pad2)") (class "Default")
      (node (ref "L1") (pin "2") (pinfunction "2_2") (pintype "passive"))
      (node (ref "Q8") (pin "1") (pinfunction "D_1") (pintype "passive"))
      (node (ref "Q8") (pin "2") (pinfunction "D_2") (pintype "passive"))
      (node (ref "Q8") (pin "5") (pinfunction "D_5") (pintype "passive"))
      (node (ref "Q8") (pin "6") (pinfunction "D_6") (pintype "passive"))
    )
    (net (code "201") (name "Net-(L7-Pad1)") (class "Default")
      (node (ref "L7") (pin "1") (pinfunction "1_1") (pintype "passive"))
      (node (ref "R108") (pin "1") (pinfunction "1_1") (pintype "passive"))
    )
    (net (code "202") (name "Net-(L8-Pad1)") (class "Default")
      (node (ref "L8") (pin "1") (pinfunction "1_1") (pintype "passive"))
      (node (ref "R109") (pin "1") (pinfunction "1_1") (pintype "passive"))
    )
    (net (code "203") (name "Net-(L13-Pad2)") (class "Default")
      (node (ref "L13") (pin "2") (pinfunction "2_2") (pintype "passive"))
      (node (ref "R92") (pin "1") (pinfunction "1_1") (pintype "passive"))
    )
    (net (code "204") (name "Net-(Q1A-G)") (class "Default")
      (node (ref "C43") (pin "2") (pinfunction "2_2") (pintype "passive"))
      (node (ref "Q1") (pin "2") (pinfunction "G_2") (pintype "passive"))
      (node (ref "R50") (pin "1") (pinfunction "1_1") (pintype "passive"))
      (node (ref "R51") (pin "2") (pinfunction "2_2") (pintype "passive"))
    )
    (net (code "205") (name "Net-(Q1A-S)") (class "Default")
      (node (ref "Q1") (pin "1") (pinfunction "S_1") (pintype "passive"))
      (node (ref "R52") (pin "1") (pinfunction "1_1") (pintype "passive"))
    )
    (net (code "206") (name "Net-(Q1B-G)") (class "Default")
      (node (ref "C82") (pin "2") (pinfunction "2_2") (pintype "passive"))
      (node (ref "Q1") (pin "5") (pinfunction "G_5") (pintype "passive"))
      (node (ref "R125") (pin "1") (pinfunction "1_1") (pintype "passive"))
      (node (ref "R126") (pin "2") (pinfunction "2_2") (pintype "passive"))
    )
    (net (code "207") (name "Net-(Q1B-S)") (class "Default")
      (node (ref "Q1") (pin "4") (pinfunction "S_4") (pintype "passive"))
      (node (ref "R127") (pin "1") (pinfunction "1_1") (pintype "passive"))
    )
    (net (code "208") (name "Net-(Q2A-G)") (class "Default")
      (node (ref "C70") (pin "2") (pinfunction "2_2") (pintype "passive"))
      (node (ref "Q2") (pin "2") (pinfunction "G_2") (pintype "passive"))
      (node (ref "R75") (pin "1") (pinfunction "1_1") (pintype "passive"))
      (node (ref "R82") (pin "2") (pinfunction "2_2") (pintype "passive"))
    )
    (net (code "209") (name "Net-(Q2A-S)") (class "Default")
      (node (ref "Q2") (pin "1") (pinfunction "S_1") (pintype "passive"))
      (node (ref "R106") (pin "1") (pinfunction "1_1") (pintype "passive"))
    )
    (net (code "210") (name "Net-(Q2B-G)") (class "Default")
      (node (ref "C69") (pin "2") (pinfunction "2_2") (pintype "passive"))
      (node (ref "Q2") (pin "5") (pinfunction "G_5") (pintype "passive"))
      (node (ref "R24") (pin "1") (pinfunction "1_1") (pintype "passive"))
      (node (ref "R65") (pin "2") (pinfunction "2_2") (pintype "passive"))
    )
    (net (code "211") (name "Net-(Q2B-S)") (class "Default")
      (node (ref "Q2") (pin "4") (pinfunction "S_4") (pintype "passive"))
      (node (ref "R105") (pin "1") (pinfunction "1_1") (pintype "passive"))
    )
    (net (code "212") (name "Net-(Q3-G)") (class "Default")
      (node (ref "C33") (pin "2") (pinfunction "2_2") (pintype "passive"))
      (node (ref "Q3") (pin "3") (pinfunction "G_3") (pintype "passive"))
      (node (ref "Q4") (pin "6") (pinfunction "D_6") (pintype "passive"))
      (node (ref "R42") (pin "2") (pinfunction "2_2") (pintype "passive"))
    )
    (net (code "213") (name "Net-(Q4A-S)") (class "Default")
      (node (ref "Q4") (pin "1") (pinfunction "S_1") (pintype "passive"))
      (node (ref "R40") (pin "2") (pinfunction "2_2") (pintype "passive"))
    )
    (net (code "214") (name "Net-(Q4B-D)") (class "Default")
      (node (ref "C34") (pin "2") (pinfunction "2_2") (pintype "passive"))
      (node (ref "Q4") (pin "3") (pinfunction "D_3") (pintype "passive"))
      (node (ref "Q5") (pin "3") (pinfunction "G_3") (pintype "passive"))
      (node (ref "R45") (pin "2") (pinfunction "2_2") (pintype "passive"))
    )
    (net (code "215") (name "Net-(Q4B-S)") (class "Default")
      (node (ref "Q4") (pin "4") (pinfunction "S_4") (pintype "passive"))
      (node (ref "R43") (pin "2") (pinfunction "2_2") (pintype "passive"))
    )
    (net (code "216") (name "Net-(Q6A-D)") (class "Default")
      (node (ref "C32") (pin "2") (pinfunction "2_2") (pintype "passive"))
      (node (ref "Q6") (pin "6") (pinfunction "D_6") (pintype "passive"))
      (node (ref "Q7") (pin "3") (pinfunction "G_3") (pintype "passive"))
      (node (ref "R11") (pin "2") (pinfunction "2_2") (pintype "passive"))
    )
    (net (code "217") (name "Net-(Q6A-S)") (class "Default")
      (node (ref "Q6") (pin "1") (pinfunction "S_1") (pintype "passive"))
      (node (ref "R12") (pin "2") (pinfunction "2_2") (pintype "passive"))
    )
    (net (code "218") (name "Net-(Q6B-D)") (class "Default")
      (node (ref "C37") (pin "2") (pinfunction "2_2") (pintype "passive"))
      (node (ref "Q6") (pin "3") (pinfunction "D_3") (pintype "passive"))
      (node (ref "Q8") (pin "3") (pinfunction "G_3") (pintype "passive"))
      (node (ref "R14") (pin "2") (pinfunction "2_2") (pintype "passive"))
    )
    (net (code "219") (name "Net-(Q6B-S)") (class "Default")
      (node (ref "Q6") (pin "4") (pinfunction "S_4") (pintype "passive"))
      (node (ref "R15") (pin "2") (pinfunction "2_2") (pintype "passive"))
    )
    (net (code "220") (name "Net-(Q9B-D)") (class "Default")
      (node (ref "Q9") (pin "3") (pinfunction "D_3") (pintype "passive"))
      (node (ref "R60") (pin "1") (pinfunction "1_1") (pintype "passive"))
    )
    (net (code "221") (name "Net-(Q10A-D)") (class "Default")
      (node (ref "Q10") (pin "6") (pinfunction "D_6") (pintype "passive"))
      (node (ref "R68") (pin "1") (pinfunction "1_1") (pintype "passive"))
      (node (ref "R69") (pin "1") (pinfunction "1_1") (pintype "passive"))
    )
    (net (code "222") (name "Net-(Q10A-G)") (class "Default")
      (node (ref "Q10") (pin "2") (pinfunction "G_2") (pintype "passive"))
      (node (ref "R116") (pin "2") (pinfunction "2_2") (pintype "passive"))
      (node (ref "R70") (pin "2") (pinfunction "2_2") (pintype "passive"))
    )
    (net (code "223") (name "Net-(Q10B-D)") (class "Default")
      (node (ref "Q10") (pin "3") (pinfunction "D_3") (pintype "passive"))
      (node (ref "R80") (pin "1") (pinfunction "1_1") (pintype "passive"))
      (node (ref "R81") (pin "1") (pinfunction "1_1") (pintype "passive"))
    )
    (net (code "224") (name "Net-(Q10B-G)") (class "Default")
      (node (ref "Q10") (pin "5") (pinfunction "G_5") (pintype "passive"))
      (node (ref "R119") (pin "2") (pinfunction "2_2") (pintype "passive"))
      (node (ref "R83") (pin "2") (pinfunction "2_2") (pintype "passive"))
    )
    (net (code "225") (name "Net-(R23-Pad1)") (class "Default")
      (node (ref "R23") (pin "1") (pinfunction "1_1") (pintype "passive"))
      (node (ref "R49") (pin "2") (pinfunction "2_2") (pintype "passive"))
    )
    (net (code "226") (name "Net-(R62-Pad2)") (class "Default")
      (node (ref "R62") (pin "2") (pinfunction "2_2") (pintype "passive"))
      (node (ref "R63") (pin "1") (pinfunction "1_1") (pintype "passive"))
      (node (ref "R64") (pin "2") (pinfunction "2_2") (pintype "passive"))
    )
    (net (code "227") (name "Net-(R66-Pad1)") (class "Default")
      (node (ref "R66") (pin "1") (pinfunction "1_1") (pintype "passive"))
      (node (ref "R67") (pin "1") (pinfunction "1_1") (pintype "passive"))
      (node (ref "R68") (pin "2") (pinfunction "2_2") (pintype "passive"))
      (node (ref "R69") (pin "2") (pinfunction "2_2") (pintype "passive"))
    )
    (net (code "228") (name "Net-(R73-Pad2)") (class "Default")
      (node (ref "R73") (pin "2") (pinfunction "2_2") (pintype "passive"))
      (node (ref "R74") (pin "1") (pinfunction "1_1") (pintype "passive"))
      (node (ref "R76") (pin "2") (pinfunction "2_2") (pintype "passive"))
    )
    (net (code "229") (name "Net-(R94-Pad2)") (class "Default")
      (node (ref "R94") (pin "2") (pinfunction "2_2") (pintype "passive"))
      (node (ref "R95") (pin "1") (pinfunction "1_1") (pintype "passive"))
    )
    (net (code "230") (name "Net-(R97-Pad2)") (class "Default")
      (node (ref "R97") (pin "2") (pinfunction "2_2") (pintype "passive"))
      (node (ref "R98") (pin "1") (pinfunction "1_1") (pintype "passive"))
    )
    (net (code "231") (name "VBAT") (class "Default")
      (node (ref "C33") (pin "1") (pinfunction "1_1") (pintype "passive"))
      (node (ref "C37") (pin "1") (pinfunction "1_1") (pintype "passive"))
      (node (ref "IC10") (pin "4") (pinfunction "VIN-_4") (pintype "input"))
      (node (ref "J7") (pin "1") (pinfunction "1_1") (pintype "passive"))
      (node (ref "J8") (pin "1") (pinfunction "1_1") (pintype "passive"))
      (node (ref "JP2") (pin "1") (pinfunction "1_1") (pintype "bidirectional"))
      (node (ref "L2") (pin "1") (pinfunction "1_1") (pintype "passive"))
      (node (ref "Q3") (pin "4") (pinfunction "S_4") (pintype "passive"))
      (node (ref "Q8") (pin "4") (pinfunction "S_4") (pintype "passive"))
      (node (ref "R14") (pin "1") (pinfunction "1_1") (pintype "passive"))
      (node (ref "R33") (pin "2") (pinfunction "2_2") (pintype "passive"))
      (node (ref "R39") (pin "1") (pinfunction "1_1") (pintype "passive"))
      (node (ref "R42") (pin "1") (pinfunction "1_1") (pintype "passive"))
      (node (ref "R97") (pin "1") (pinfunction "1_1") (pintype "passive"))
    )
    (net (code "232") (name "unconnected-(IC1-AN12{slash}PMA11{slash}RB12-Pad41)") (class "Default")
      (node (ref "IC1") (pin "41") (pinfunction "AN12/PMA11/RB12_41") (pintype "bidirectional"))
    )
    (net (code "233") (name "unconnected-(IC1-AN20{slash}PMD2{slash}RE2-Pad98)") (class "Default")
      (node (ref "IC1") (pin "98") (pinfunction "AN20/PMD2/RE2_98") (pintype "bidirectional"))
    )
    (net (code "234") (name "unconnected-(IC1-AN21{slash}PMD4{slash}RE4-Pad100)") (class "Default")
      (node (ref "IC1") (pin "100") (pinfunction "AN21/PMD4/RE4_100") (pintype "bidirectional"))
    )
    (net (code "235") (name "unconnected-(IC1-PMD13{slash}RD13-Pad80)") (class "Default")
      (node (ref "IC1") (pin "80") (pinfunction "PMD13/RD13_80") (pintype "bidirectional"))
    )
    (net (code "236") (name "unconnected-(IC1-RPC3{slash}RC3-Pad8)") (class "Default")
      (node (ref "IC1") (pin "8") (pinfunction "RPC3/RC3_8") (pintype "bidirectional"))
    )
    (net (code "237") (name "unconnected-(IC1-RPF3{slash}USBID{slash}RF3-Pad51)") (class "Default")
      (node (ref "IC1") (pin "51") (pinfunction "RPF3/USBID/RF3_51") (pintype "bidirectional"))
    )
    (net (code "238") (name "unconnected-(IC1-RPF12{slash}RF12-Pad40)") (class "Default")
      (node (ref "IC1") (pin "40") (pinfunction "RPF12/RF12_40") (pintype "bidirectional"))
    )
    (net (code "239") (name "unconnected-(IC1-TMS{slash}CTED1{slash}RA0-Pad17)") (class "Default")
      (node (ref "IC1") (pin "17") (pinfunction "TMS/CTED1/RA0_17") (pintype "bidirectional"))
    )
    (net (code "240") (name "unconnected-(IC8-PG-Pad9)") (class "Default")
      (node (ref "IC8") (pin "9") (pinfunction "PG_9") (pintype "bidirectional"))
    )
    (net (code "241") (name "unconnected-(IC17-NC-Pad16)") (class "Default")
      (node (ref "IC17") (pin "16") (pinfunction "NC_16") (pintype "bidirectional"))
    )
    (net (code "242") (name "unconnected-(IC24-OS-Pad3)") (class "Default")
      (node (ref "IC24") (pin "3") (pinfunction "OS_3") (pintype "output"))
    )
    (net (code "243") (name "unconnected-(IC25-NC-Pad13)") (class "Default")
      (node (ref "IC25") (pin "13") (pinfunction "NC_13") (pintype "no_connect"))
    )
    (net (code "244") (name "unconnected-(IC29-GPIO-EXPR-00-Pad6)") (class "Default")
      (node (ref "IC29") (pin "6") (pinfunction "GPIO-EXPR-00_6") (pintype "bidirectional"))
    )
    (net (code "245") (name "unconnected-(IC29-NC-Pad5)") (class "Default")
      (node (ref "IC29") (pin "5") (pinfunction "NC_5") (pintype "passive"))
    )
    (net (code "246") (name "unconnected-(IC29-NC-Pad12)") (class "Default")
      (node (ref "IC29") (pin "12") (pinfunction "NC_12") (pintype "passive"))
    )
    (net (code "247") (name "unconnected-(IC29-NC-Pad13)") (class "Default")
      (node (ref "IC29") (pin "13") (pinfunction "NC_13") (pintype "passive"))
    )
    (net (code "248") (name "unconnected-(IC29-NC-Pad14)") (class "Default")
      (node (ref "IC29") (pin "14") (pinfunction "NC_14") (pintype "passive"))
    )
    (net (code "249") (name "unconnected-(IC29-NC-Pad15)") (class "Default")
      (node (ref "IC29") (pin "15") (pinfunction "NC_15") (pintype "passive"))
    )
    (net (code "250") (name "unconnected-(IC29-NC-Pad27)") (class "Default")
      (node (ref "IC29") (pin "27") (pinfunction "NC_27") (pintype "passive"))
    )
    (net (code "251") (name "unconnected-(IC29-NC-Pad28)") (class "Default")
      (node (ref "IC29") (pin "28") (pinfunction "NC_28") (pintype "passive"))
    )
    (net (code "252") (name "unconnected-(IC29-PP{slash}GPIO{slash}TWI_WUP-Pad7)") (class "Default")
      (node (ref "IC29") (pin "7") (pinfunction "PP/GPIO/TWI_WUP_7") (pintype "bidirectional"))
    )
    (net (code "253") (name "unconnected-(J1-+5V-Pad12)") (class "Default")
      (node (ref "J1") (pin "12") (pinfunction "+5V_12") (pintype "passive"))
    )
    (net (code "254") (name "unconnected-(J1-AGND-Pad26)") (class "Default")
      (node (ref "J1") (pin "26") (pinfunction "AGND_26") (pintype "passive"))
    )
    (net (code "255") (name "unconnected-(J1-AN-IN0-Pad25)") (class "Default")
      (node (ref "J1") (pin "25") (pinfunction "AN-IN0_25") (pintype "passive"))
    )
    (net (code "256") (name "unconnected-(J1-AN-IN1-Pad24)") (class "Default")
      (node (ref "J1") (pin "24") (pinfunction "AN-IN1_24") (pintype "passive"))
    )
    (net (code "257") (name "unconnected-(J1-AN-IN2-Pad23)") (class "Default")
      (node (ref "J1") (pin "23") (pinfunction "AN-IN2_23") (pintype "passive"))
    )
    (net (code "258") (name "unconnected-(J1-AN-IN3-Pad22)") (class "Default")
      (node (ref "J1") (pin "22") (pinfunction "AN-IN3_22") (pintype "passive"))
    )
    (net (code "259") (name "unconnected-(J1-CTS-B-Pad29)") (class "Default")
      (node (ref "J1") (pin "29") (pinfunction "CTS-B_29") (pintype "passive"))
    )
    (net (code "260") (name "unconnected-(J1-PWM_A-Pad37)") (class "Default")
      (node (ref "J1") (pin "37") (pinfunction "PWM_A_37") (pintype "passive"))
    )
    (net (code "261") (name "unconnected-(J1-PWM_D-Pad40)") (class "Default")
      (node (ref "J1") (pin "40") (pinfunction "PWM_D_40") (pintype "passive"))
    )
    (net (code "262") (name "unconnected-(J1-RTS-B-Pad30)") (class "Default")
      (node (ref "J1") (pin "30") (pinfunction "RTS-B_30") (pintype "passive"))
    )
    (net (code "263") (name "unconnected-(J1-SSP-FRM-Pad9)") (class "Default")
      (node (ref "J1") (pin "9") (pinfunction "SSP-FRM_9") (pintype "passive"))
    )
    (net (code "264") (name "unconnected-(J1-SSP-RXD-Pad10)") (class "Default")
      (node (ref "J1") (pin "10") (pinfunction "SSP-RXD_10") (pintype "passive"))
    )
    (net (code "265") (name "unconnected-(J1-SSP-SCLK-Pad8)") (class "Default")
      (node (ref "J1") (pin "8") (pinfunction "SSP-SCLK_8") (pintype "passive"))
    )
    (net (code "266") (name "unconnected-(J1-SSP-TXD-Pad11)") (class "Default")
      (node (ref "J1") (pin "11") (pinfunction "SSP-TXD_11") (pintype "passive"))
    )
    (net (code "267") (name "unconnected-(J2-PadC4)") (class "Default")
      (node (ref "J2") (pin "C4") (pinfunction "C4_C4") (pintype "no_connect"))
    )
    (net (code "268") (name "unconnected-(J2-PadC6)") (class "Default")
      (node (ref "J2") (pin "C6") (pinfunction "C6_C6") (pintype "no_connect"))
    )
    (net (code "269") (name "unconnected-(J2-PadC8)") (class "Default")
      (node (ref "J2") (pin "C8") (pinfunction "C8_C8") (pintype "no_connect"))
    )
    (net (code "270") (name "unconnected-(J5-Pad2)") (class "Default")
      (node (ref "J5") (pin "2") (pinfunction "2_2") (pintype "passive"))
    )
    (net (code "271") (name "unconnected-(J5-Pad3)") (class "Default")
      (node (ref "J5") (pin "3") (pinfunction "3_3") (pintype "passive"))
    )
    (net (code "272") (name "unconnected-(J5-Pad10)") (class "Default")
      (node (ref "J5") (pin "10") (pinfunction "10_10") (pintype "passive"))
    )
    (net (code "273") (name "unconnected-(J6-Pad7)") (class "Default")
      (node (ref "J6") (pin "7") (pinfunction "7_7") (pintype "passive"))
    )
    (net (code "274") (name "unconnected-(J6-Pad8)") (class "Default")
      (node (ref "J6") (pin "8") (pinfunction "8_8") (pintype "passive"))
    )
    (net (code "275") (name "unconnected-(J6-Pad9)") (class "Default")
      (node (ref "J6") (pin "9") (pinfunction "9_9") (pintype "passive"))
    )
    (net (code "276") (name "unconnected-(J6-Pad10)") (class "Default")
      (node (ref "J6") (pin "10") (pinfunction "10_10") (pintype "passive"))
    )
    (net (code "277") (name "unconnected-(J9F-1-Pad5)") (class "Default")
      (node (ref "J9") (pin "5") (pinfunction "1_5") (pintype "passive"))
    )
    (net (code "278") (name "unconnected-(J14-Pad8)") (class "Default")
      (node (ref "J14") (pin "8") (pinfunction "8_8") (pintype "passive"))
    )
    (net (code "279") (name "unconnected-(J15-Pad5)") (class "Default")
      (node (ref "J15") (pin "5") (pinfunction "5_5") (pintype "passive"))
    )
    (net (code "280") (name "unconnected-(J21-Pad5)") (class "Default")
      (node (ref "J21") (pin "5") (pinfunction "5_5") (pintype "passive"))
    )
    (net (code "281") (name "unconnected-(JP2-Pad3)") (class "Default")
      (node (ref "JP2") (pin "3") (pinfunction "3_3") (pintype "bidirectional"))
    )
    (net (code "282") (name "unconnected-(PCB2-Pad1)") (class "Default")
      (node (ref "PCB2") (pin "1") (pinfunction "1_1") (pintype "bidirectional"))
    )
    (net (code "283") (name "unconnected-(PCB2-Pad2)") (class "Default")
      (node (ref "PCB2") (pin "2") (pinfunction "2_2") (pintype "bidirectional"))
    )
    (net (code "284") (name "unconnected-(PCB2-Pad3)") (class "Default")
      (node (ref "PCB2") (pin "3") (pinfunction "3_3") (pintype "bidirectional"))
    )
    (net (code "285") (name "unconnected-(PCB2-Pad4)") (class "Default")
      (node (ref "PCB2") (pin "4") (pinfunction "4_4") (pintype "bidirectional"))
    )
  )
)
